# ARE_moduls.net
KiCad netlist of a schematic drawn in EAGLE
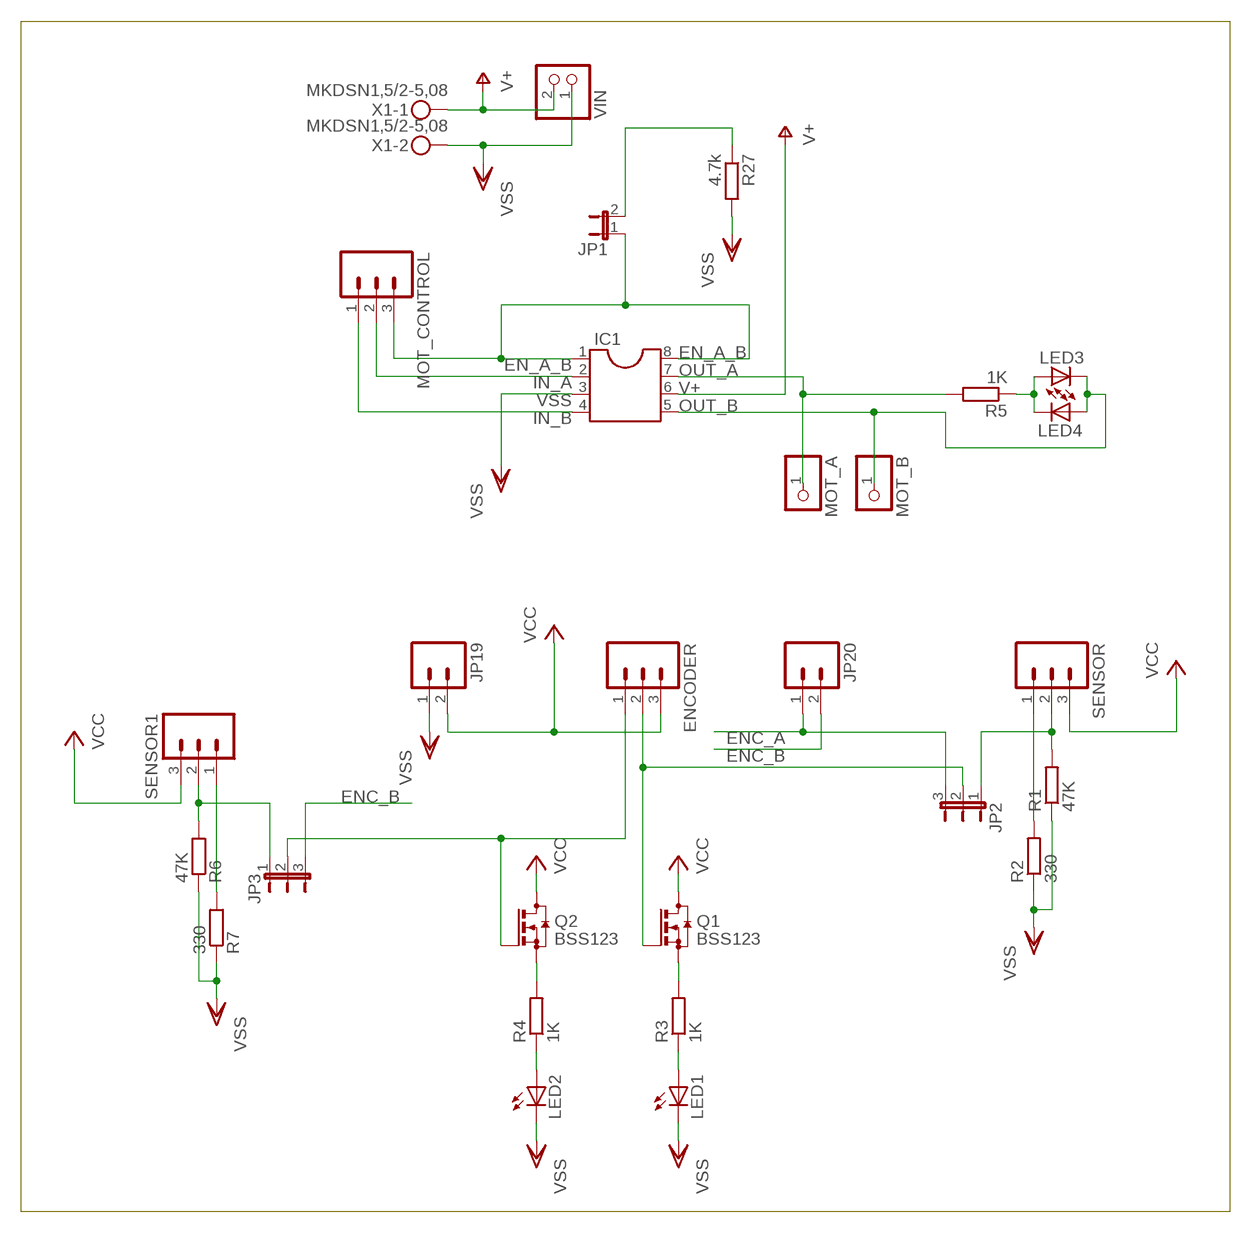
[diagram p0: schematic, sheet 1]
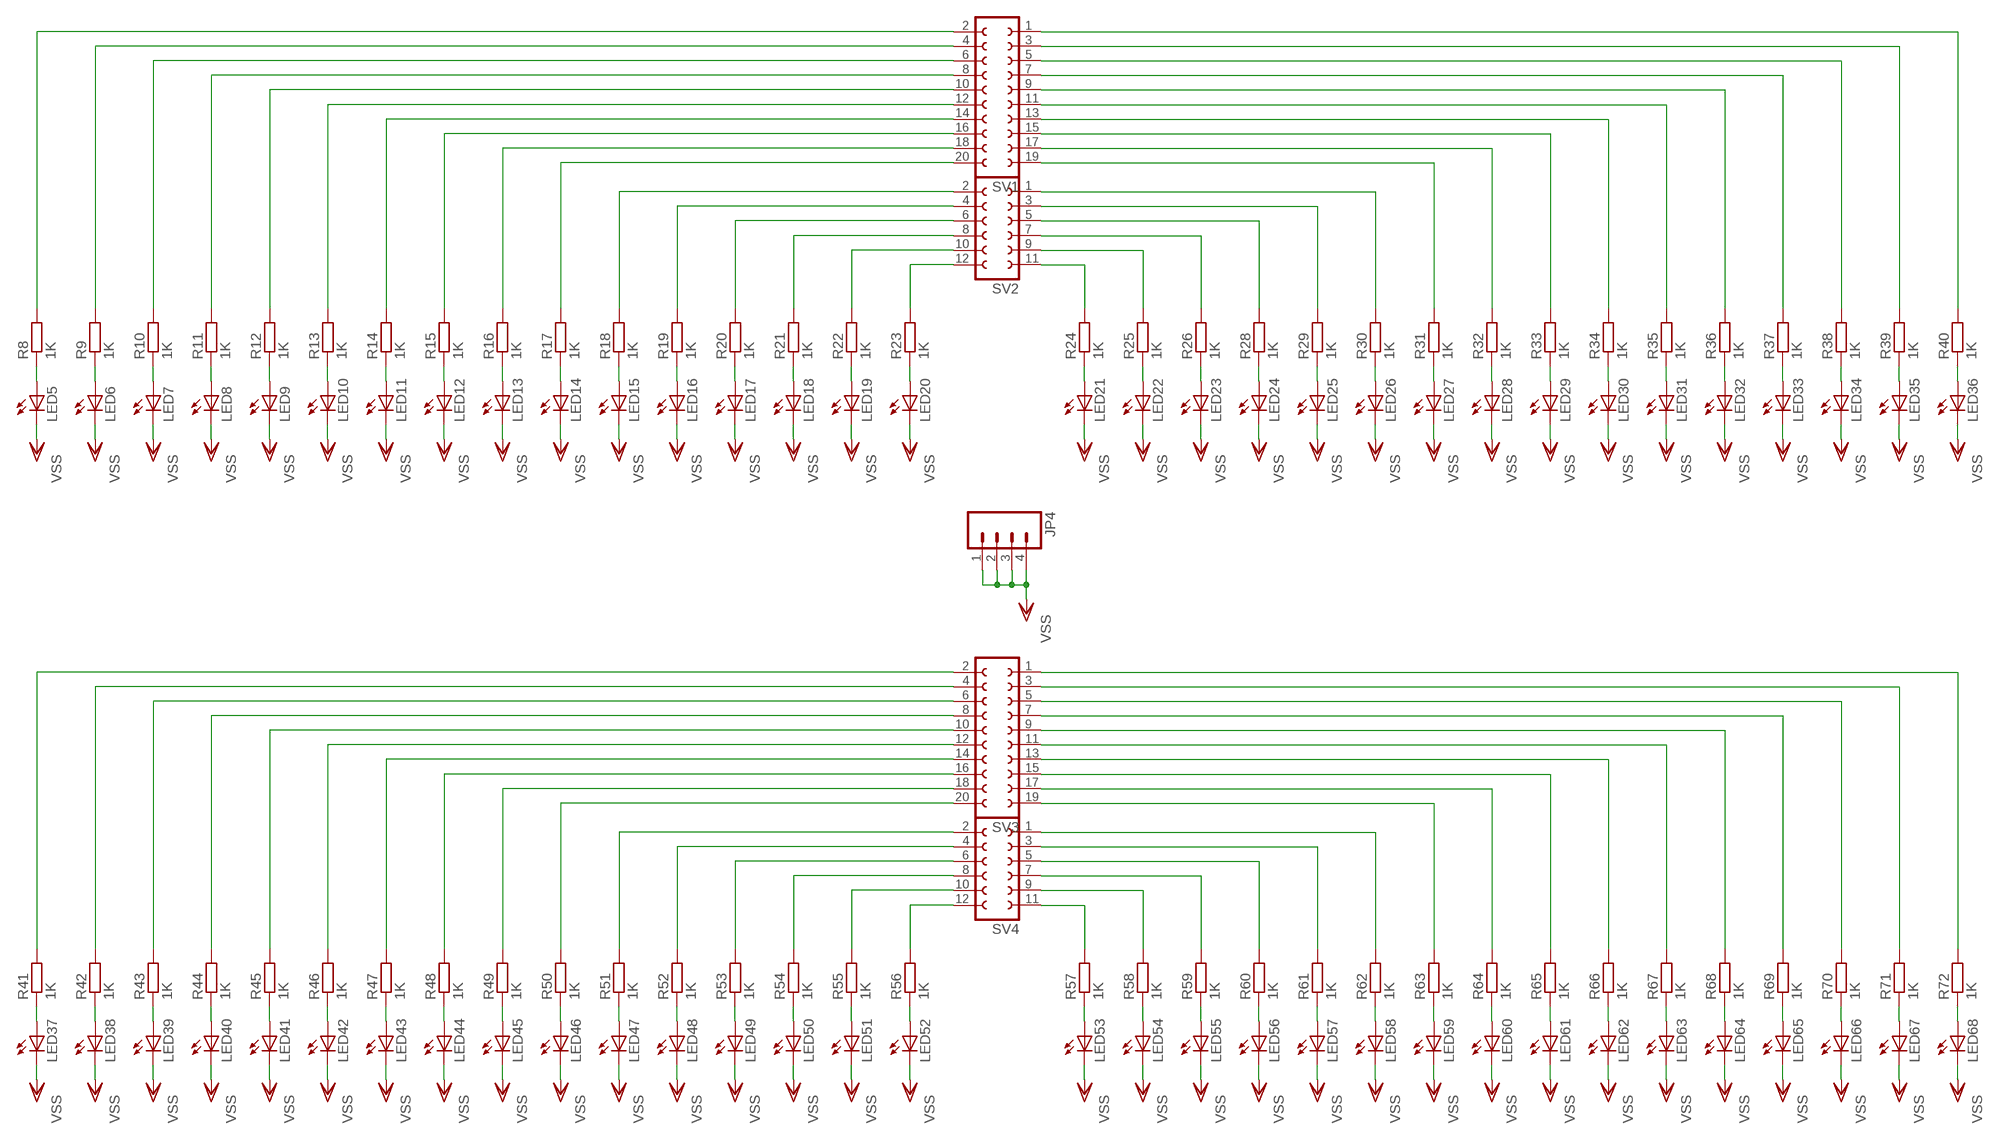
[diagram p1: schematic, sheet 2]
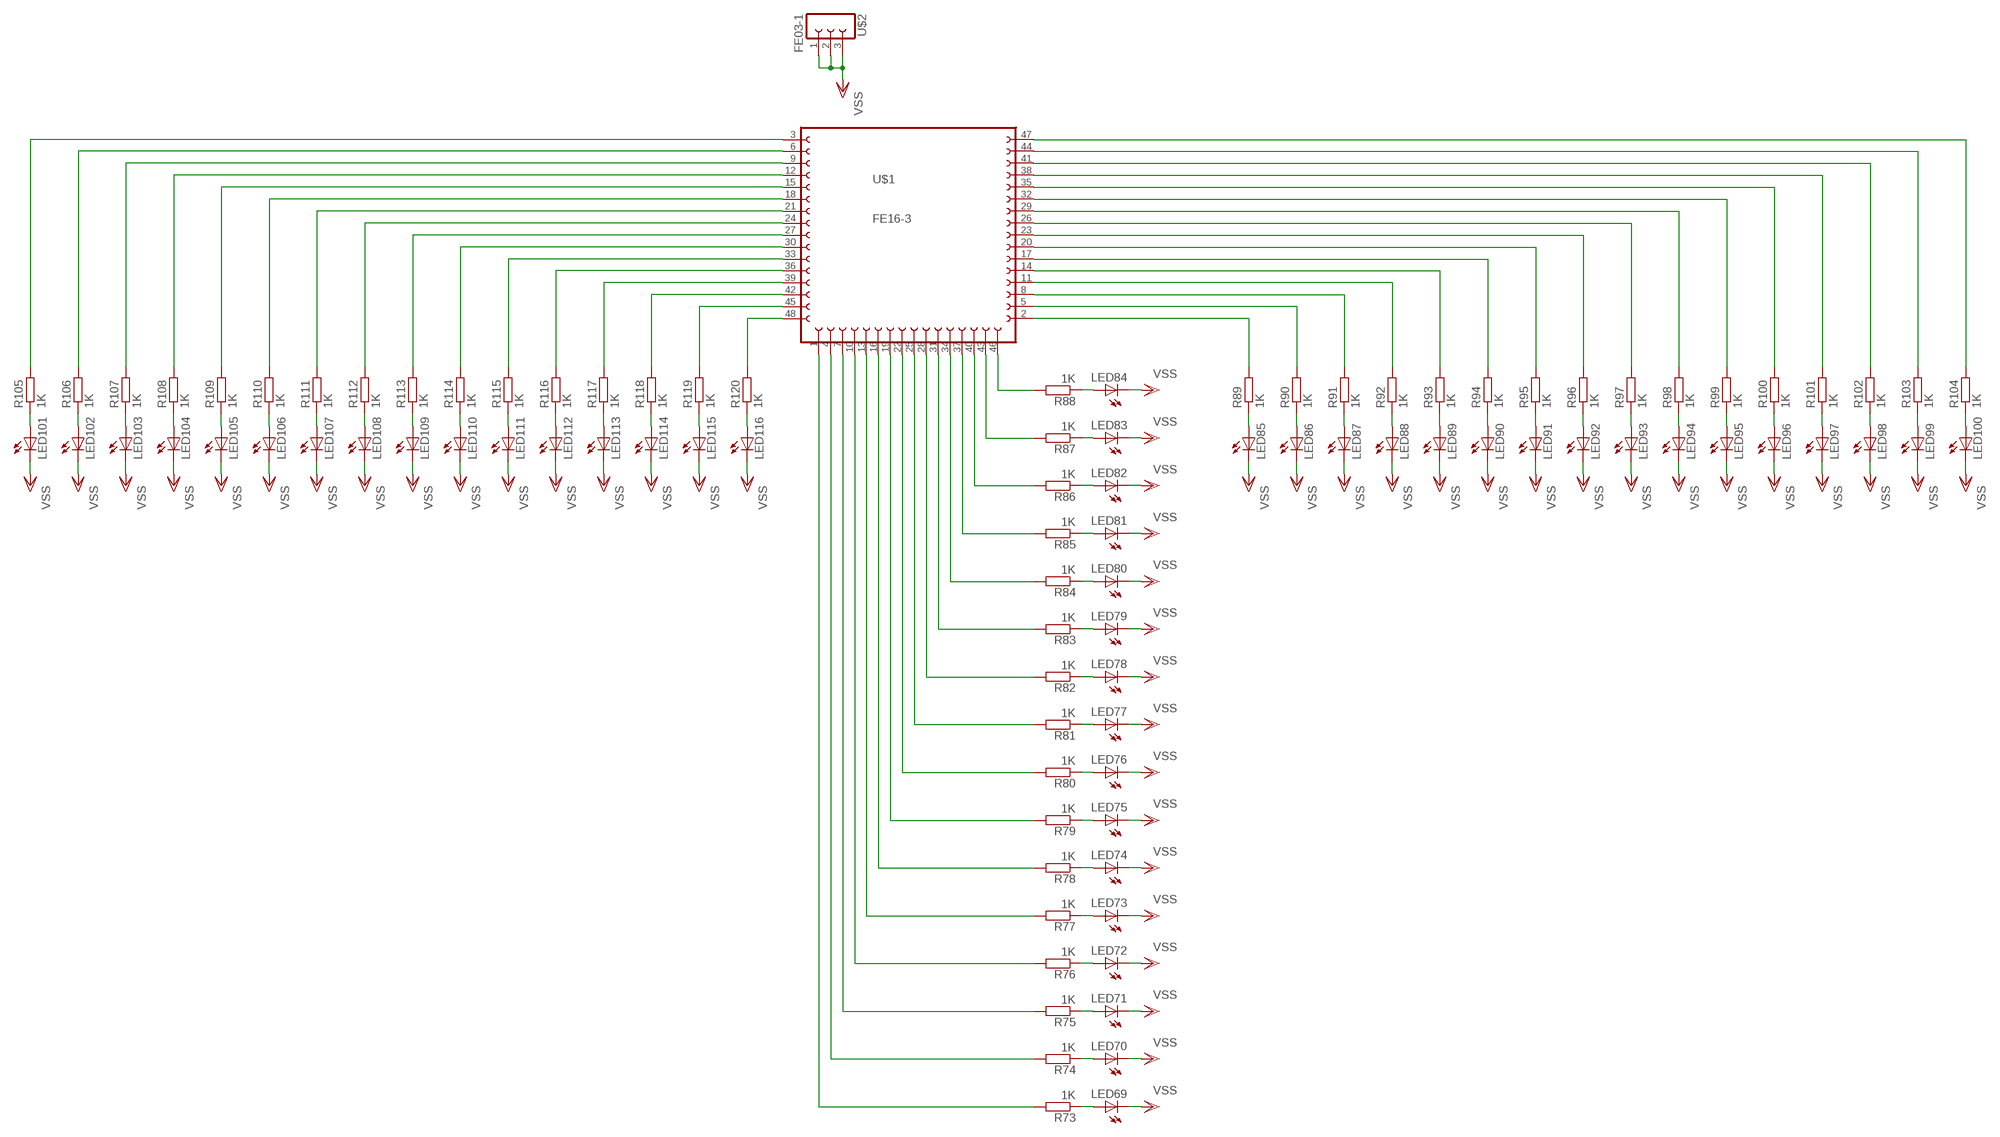
[diagram p2: schematic, sheet 3]
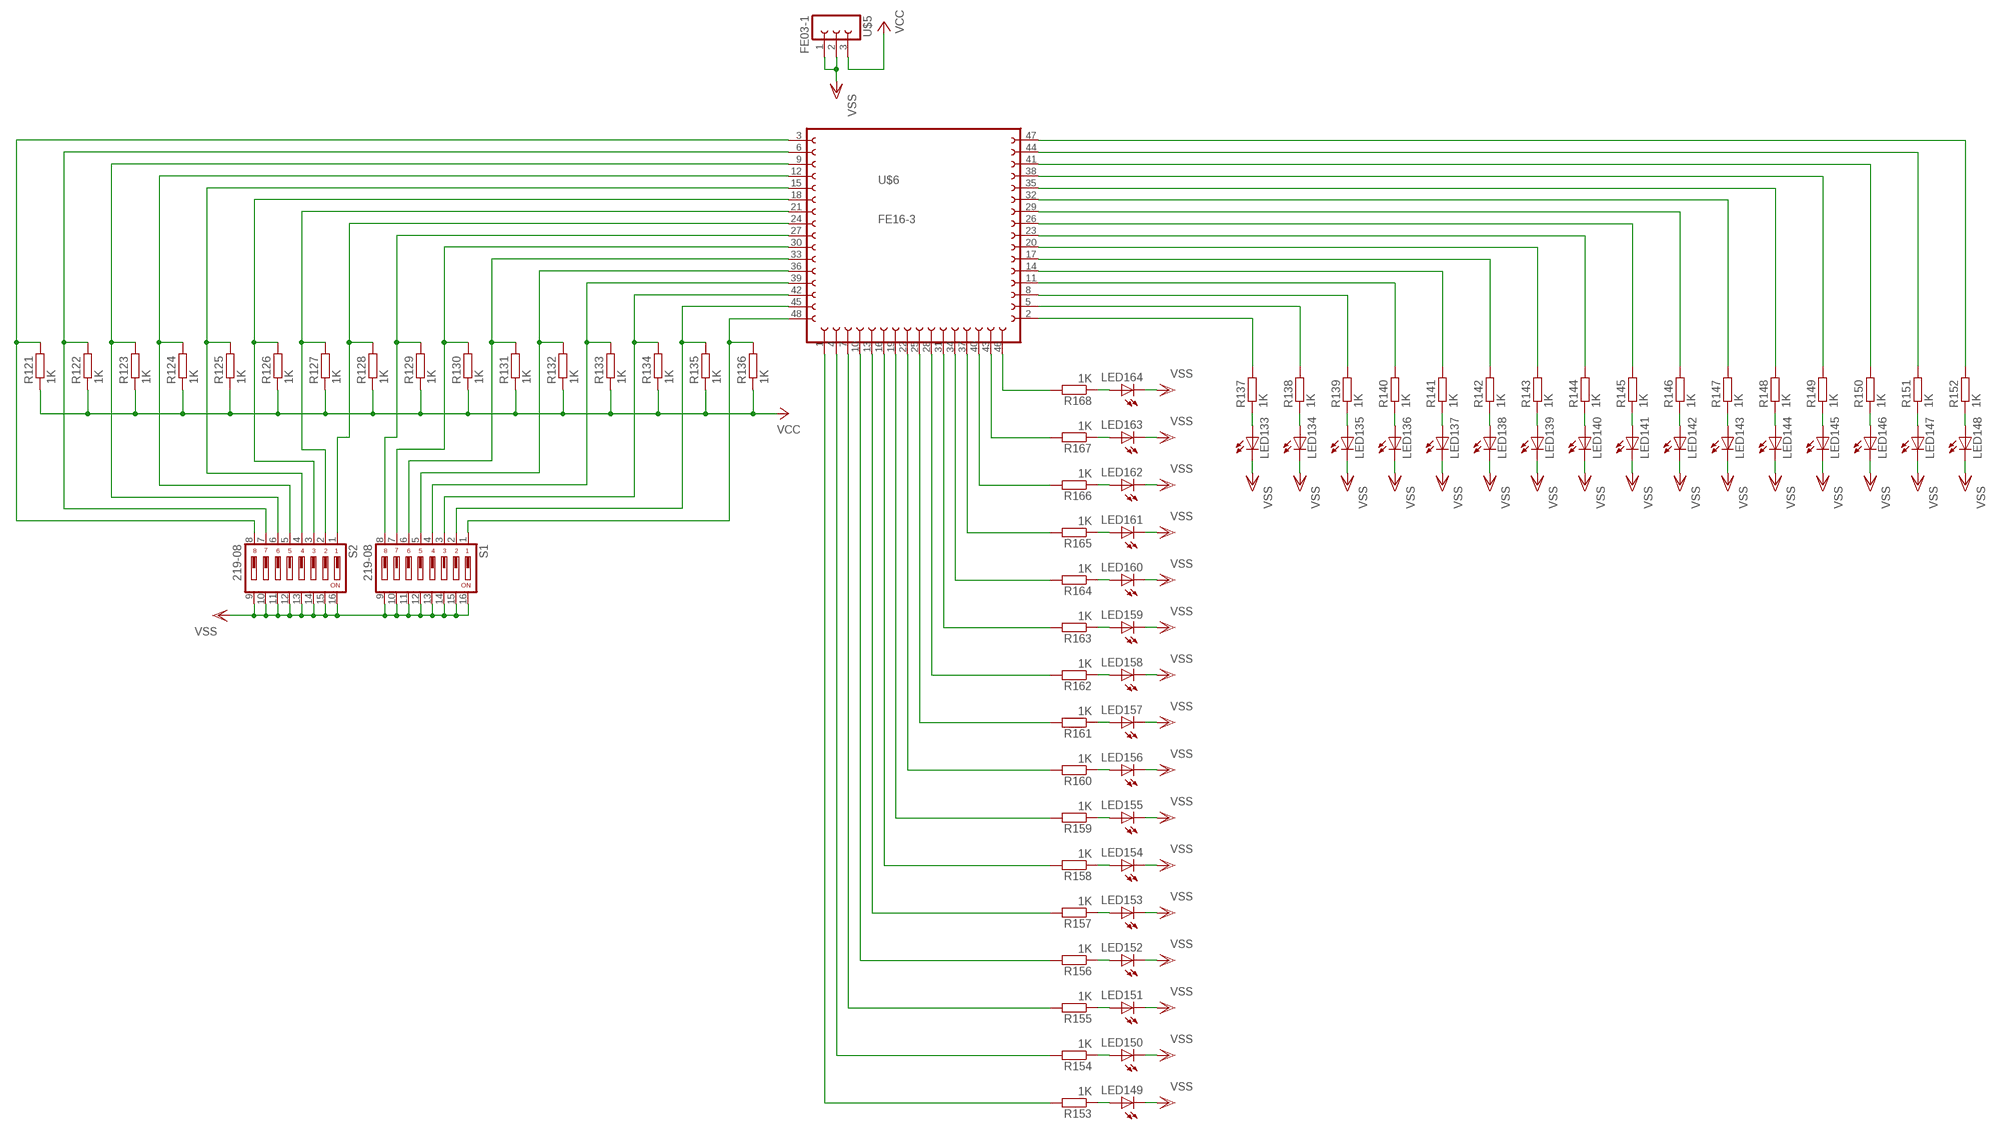
[diagram p3: schematic, sheet 4]
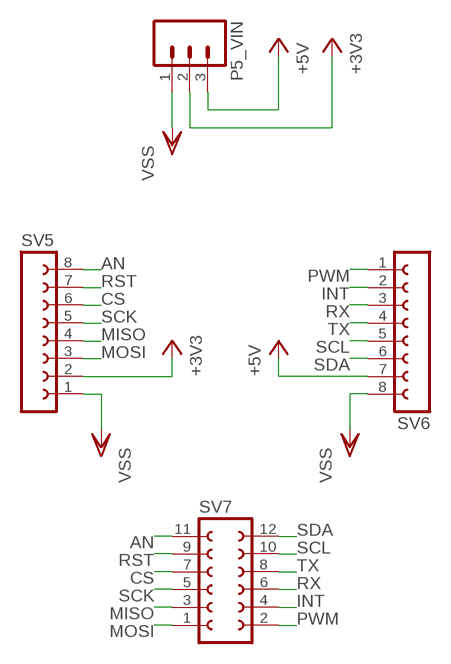
[diagram p4: schematic, sheet 5]
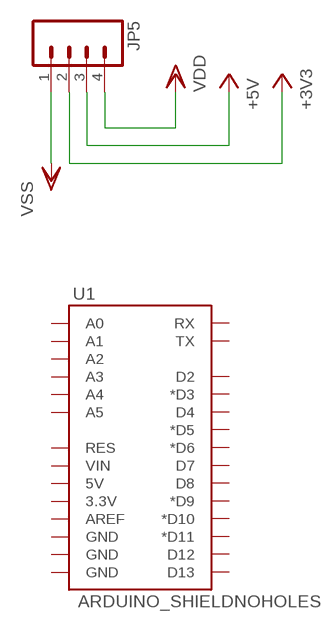
[diagram p5: schematic, sheet 6]

(export (version "E")
  (design (tool "Eeschema 10.0.6"))
  (components
    (comp (ref "LED133")
      (value "LEDCHIPLED_0805")
      (footprint "eagle-import:CHIPLED_0805")
      (libsource (lib "eagle-import") (part "LEDCHIPLED_0805"))
    )
    (comp (ref "LED134")
      (value "LEDCHIPLED_0805")
      (footprint "eagle-import:CHIPLED_0805")
      (libsource (lib "eagle-import") (part "LEDCHIPLED_0805"))
    )
    (comp (ref "LED135")
      (value "LEDCHIPLED_0805")
      (footprint "eagle-import:CHIPLED_0805")
      (libsource (lib "eagle-import") (part "LEDCHIPLED_0805"))
    )
    (comp (ref "LED136")
      (value "LEDCHIPLED_0805")
      (footprint "eagle-import:CHIPLED_0805")
      (libsource (lib "eagle-import") (part "LEDCHIPLED_0805"))
    )
    (comp (ref "LED137")
      (value "LEDCHIPLED_0805")
      (footprint "eagle-import:CHIPLED_0805")
      (libsource (lib "eagle-import") (part "LEDCHIPLED_0805"))
    )
    (comp (ref "LED138")
      (value "LEDCHIPLED_0805")
      (footprint "eagle-import:CHIPLED_0805")
      (libsource (lib "eagle-import") (part "LEDCHIPLED_0805"))
    )
    (comp (ref "LED139")
      (value "LEDCHIPLED_0805")
      (footprint "eagle-import:CHIPLED_0805")
      (libsource (lib "eagle-import") (part "LEDCHIPLED_0805"))
    )
    (comp (ref "LED140")
      (value "LEDCHIPLED_0805")
      (footprint "eagle-import:CHIPLED_0805")
      (libsource (lib "eagle-import") (part "LEDCHIPLED_0805"))
    )
    (comp (ref "LED141")
      (value "LEDCHIPLED_0805")
      (footprint "eagle-import:CHIPLED_0805")
      (libsource (lib "eagle-import") (part "LEDCHIPLED_0805"))
    )
    (comp (ref "LED142")
      (value "LEDCHIPLED_0805")
      (footprint "eagle-import:CHIPLED_0805")
      (libsource (lib "eagle-import") (part "LEDCHIPLED_0805"))
    )
    (comp (ref "LED143")
      (value "LEDCHIPLED_0805")
      (footprint "eagle-import:CHIPLED_0805")
      (libsource (lib "eagle-import") (part "LEDCHIPLED_0805"))
    )
    (comp (ref "LED144")
      (value "LEDCHIPLED_0805")
      (footprint "eagle-import:CHIPLED_0805")
      (libsource (lib "eagle-import") (part "LEDCHIPLED_0805"))
    )
    (comp (ref "LED145")
      (value "LEDCHIPLED_0805")
      (footprint "eagle-import:CHIPLED_0805")
      (libsource (lib "eagle-import") (part "LEDCHIPLED_0805"))
    )
    (comp (ref "LED146")
      (value "LEDCHIPLED_0805")
      (footprint "eagle-import:CHIPLED_0805")
      (libsource (lib "eagle-import") (part "LEDCHIPLED_0805"))
    )
    (comp (ref "LED147")
      (value "LEDCHIPLED_0805")
      (footprint "eagle-import:CHIPLED_0805")
      (libsource (lib "eagle-import") (part "LEDCHIPLED_0805"))
    )
    (comp (ref "LED148")
      (value "LEDCHIPLED_0805")
      (footprint "eagle-import:CHIPLED_0805")
      (libsource (lib "eagle-import") (part "LEDCHIPLED_0805"))
    )
    (comp (ref "LED149")
      (value "LEDCHIPLED_0805")
      (footprint "eagle-import:CHIPLED_0805")
      (libsource (lib "eagle-import") (part "LEDCHIPLED_0805"))
    )
    (comp (ref "LED150")
      (value "LEDCHIPLED_0805")
      (footprint "eagle-import:CHIPLED_0805")
      (libsource (lib "eagle-import") (part "LEDCHIPLED_0805"))
    )
    (comp (ref "LED151")
      (value "LEDCHIPLED_0805")
      (footprint "eagle-import:CHIPLED_0805")
      (libsource (lib "eagle-import") (part "LEDCHIPLED_0805"))
    )
    (comp (ref "LED152")
      (value "LEDCHIPLED_0805")
      (footprint "eagle-import:CHIPLED_0805")
      (libsource (lib "eagle-import") (part "LEDCHIPLED_0805"))
    )
    (comp (ref "LED153")
      (value "LEDCHIPLED_0805")
      (footprint "eagle-import:CHIPLED_0805")
      (libsource (lib "eagle-import") (part "LEDCHIPLED_0805"))
    )
    (comp (ref "LED154")
      (value "LEDCHIPLED_0805")
      (footprint "eagle-import:CHIPLED_0805")
      (libsource (lib "eagle-import") (part "LEDCHIPLED_0805"))
    )
    (comp (ref "LED155")
      (value "LEDCHIPLED_0805")
      (footprint "eagle-import:CHIPLED_0805")
      (libsource (lib "eagle-import") (part "LEDCHIPLED_0805"))
    )
    (comp (ref "LED156")
      (value "LEDCHIPLED_0805")
      (footprint "eagle-import:CHIPLED_0805")
      (libsource (lib "eagle-import") (part "LEDCHIPLED_0805"))
    )
    (comp (ref "LED157")
      (value "LEDCHIPLED_0805")
      (footprint "eagle-import:CHIPLED_0805")
      (libsource (lib "eagle-import") (part "LEDCHIPLED_0805"))
    )
    (comp (ref "LED158")
      (value "LEDCHIPLED_0805")
      (footprint "eagle-import:CHIPLED_0805")
      (libsource (lib "eagle-import") (part "LEDCHIPLED_0805"))
    )
    (comp (ref "LED159")
      (value "LEDCHIPLED_0805")
      (footprint "eagle-import:CHIPLED_0805")
      (libsource (lib "eagle-import") (part "LEDCHIPLED_0805"))
    )
    (comp (ref "LED160")
      (value "LEDCHIPLED_0805")
      (footprint "eagle-import:CHIPLED_0805")
      (libsource (lib "eagle-import") (part "LEDCHIPLED_0805"))
    )
    (comp (ref "LED161")
      (value "LEDCHIPLED_0805")
      (footprint "eagle-import:CHIPLED_0805")
      (libsource (lib "eagle-import") (part "LEDCHIPLED_0805"))
    )
    (comp (ref "LED162")
      (value "LEDCHIPLED_0805")
      (footprint "eagle-import:CHIPLED_0805")
      (libsource (lib "eagle-import") (part "LEDCHIPLED_0805"))
    )
    (comp (ref "LED163")
      (value "LEDCHIPLED_0805")
      (footprint "eagle-import:CHIPLED_0805")
      (libsource (lib "eagle-import") (part "LEDCHIPLED_0805"))
    )
    (comp (ref "LED164")
      (value "LEDCHIPLED_0805")
      (footprint "eagle-import:CHIPLED_0805")
      (libsource (lib "eagle-import") (part "LEDCHIPLED_0805"))
    )
    (comp (ref "R121")
      (value "1K")
      (footprint "eagle-import:M0805")
      (libsource (lib "eagle-import") (part "R-EU_M0805"))
    )
    (comp (ref "R122")
      (value "1K")
      (footprint "eagle-import:M0805")
      (libsource (lib "eagle-import") (part "R-EU_M0805"))
    )
    (comp (ref "R123")
      (value "1K")
      (footprint "eagle-import:M0805")
      (libsource (lib "eagle-import") (part "R-EU_M0805"))
    )
    (comp (ref "R124")
      (value "1K")
      (footprint "eagle-import:M0805")
      (libsource (lib "eagle-import") (part "R-EU_M0805"))
    )
    (comp (ref "R125")
      (value "1K")
      (footprint "eagle-import:M0805")
      (libsource (lib "eagle-import") (part "R-EU_M0805"))
    )
    (comp (ref "R126")
      (value "1K")
      (footprint "eagle-import:M0805")
      (libsource (lib "eagle-import") (part "R-EU_M0805"))
    )
    (comp (ref "R127")
      (value "1K")
      (footprint "eagle-import:M0805")
      (libsource (lib "eagle-import") (part "R-EU_M0805"))
    )
    (comp (ref "R128")
      (value "1K")
      (footprint "eagle-import:M0805")
      (libsource (lib "eagle-import") (part "R-EU_M0805"))
    )
    (comp (ref "R129")
      (value "1K")
      (footprint "eagle-import:M0805")
      (libsource (lib "eagle-import") (part "R-EU_M0805"))
    )
    (comp (ref "R130")
      (value "1K")
      (footprint "eagle-import:M0805")
      (libsource (lib "eagle-import") (part "R-EU_M0805"))
    )
    (comp (ref "R131")
      (value "1K")
      (footprint "eagle-import:M0805")
      (libsource (lib "eagle-import") (part "R-EU_M0805"))
    )
    (comp (ref "R132")
      (value "1K")
      (footprint "eagle-import:M0805")
      (libsource (lib "eagle-import") (part "R-EU_M0805"))
    )
    (comp (ref "R133")
      (value "1K")
      (footprint "eagle-import:M0805")
      (libsource (lib "eagle-import") (part "R-EU_M0805"))
    )
    (comp (ref "R134")
      (value "1K")
      (footprint "eagle-import:M0805")
      (libsource (lib "eagle-import") (part "R-EU_M0805"))
    )
    (comp (ref "R135")
      (value "1K")
      (footprint "eagle-import:M0805")
      (libsource (lib "eagle-import") (part "R-EU_M0805"))
    )
    (comp (ref "R136")
      (value "1K")
      (footprint "eagle-import:M0805")
      (libsource (lib "eagle-import") (part "R-EU_M0805"))
    )
    (comp (ref "R137")
      (value "1K")
      (footprint "eagle-import:M0805")
      (libsource (lib "eagle-import") (part "R-EU_M0805"))
    )
    (comp (ref "R138")
      (value "1K")
      (footprint "eagle-import:M0805")
      (libsource (lib "eagle-import") (part "R-EU_M0805"))
    )
    (comp (ref "R139")
      (value "1K")
      (footprint "eagle-import:M0805")
      (libsource (lib "eagle-import") (part "R-EU_M0805"))
    )
    (comp (ref "R140")
      (value "1K")
      (footprint "eagle-import:M0805")
      (libsource (lib "eagle-import") (part "R-EU_M0805"))
    )
    (comp (ref "R141")
      (value "1K")
      (footprint "eagle-import:M0805")
      (libsource (lib "eagle-import") (part "R-EU_M0805"))
    )
    (comp (ref "R142")
      (value "1K")
      (footprint "eagle-import:M0805")
      (libsource (lib "eagle-import") (part "R-EU_M0805"))
    )
    (comp (ref "R143")
      (value "1K")
      (footprint "eagle-import:M0805")
      (libsource (lib "eagle-import") (part "R-EU_M0805"))
    )
    (comp (ref "R144")
      (value "1K")
      (footprint "eagle-import:M0805")
      (libsource (lib "eagle-import") (part "R-EU_M0805"))
    )
    (comp (ref "R145")
      (value "1K")
      (footprint "eagle-import:M0805")
      (libsource (lib "eagle-import") (part "R-EU_M0805"))
    )
    (comp (ref "R146")
      (value "1K")
      (footprint "eagle-import:M0805")
      (libsource (lib "eagle-import") (part "R-EU_M0805"))
    )
    (comp (ref "R147")
      (value "1K")
      (footprint "eagle-import:M0805")
      (libsource (lib "eagle-import") (part "R-EU_M0805"))
    )
    (comp (ref "R148")
      (value "1K")
      (footprint "eagle-import:M0805")
      (libsource (lib "eagle-import") (part "R-EU_M0805"))
    )
    (comp (ref "R149")
      (value "1K")
      (footprint "eagle-import:M0805")
      (libsource (lib "eagle-import") (part "R-EU_M0805"))
    )
    (comp (ref "R150")
      (value "1K")
      (footprint "eagle-import:M0805")
      (libsource (lib "eagle-import") (part "R-EU_M0805"))
    )
    (comp (ref "R151")
      (value "1K")
      (footprint "eagle-import:M0805")
      (libsource (lib "eagle-import") (part "R-EU_M0805"))
    )
    (comp (ref "R152")
      (value "1K")
      (footprint "eagle-import:M0805")
      (libsource (lib "eagle-import") (part "R-EU_M0805"))
    )
    (comp (ref "R153")
      (value "1K")
      (footprint "eagle-import:M0805")
      (libsource (lib "eagle-import") (part "R-EU_M0805"))
    )
    (comp (ref "R154")
      (value "1K")
      (footprint "eagle-import:M0805")
      (libsource (lib "eagle-import") (part "R-EU_M0805"))
    )
    (comp (ref "R155")
      (value "1K")
      (footprint "eagle-import:M0805")
      (libsource (lib "eagle-import") (part "R-EU_M0805"))
    )
    (comp (ref "R156")
      (value "1K")
      (footprint "eagle-import:M0805")
      (libsource (lib "eagle-import") (part "R-EU_M0805"))
    )
    (comp (ref "R157")
      (value "1K")
      (footprint "eagle-import:M0805")
      (libsource (lib "eagle-import") (part "R-EU_M0805"))
    )
    (comp (ref "R158")
      (value "1K")
      (footprint "eagle-import:M0805")
      (libsource (lib "eagle-import") (part "R-EU_M0805"))
    )
    (comp (ref "R159")
      (value "1K")
      (footprint "eagle-import:M0805")
      (libsource (lib "eagle-import") (part "R-EU_M0805"))
    )
    (comp (ref "R160")
      (value "1K")
      (footprint "eagle-import:M0805")
      (libsource (lib "eagle-import") (part "R-EU_M0805"))
    )
    (comp (ref "R161")
      (value "1K")
      (footprint "eagle-import:M0805")
      (libsource (lib "eagle-import") (part "R-EU_M0805"))
    )
    (comp (ref "R162")
      (value "1K")
      (footprint "eagle-import:M0805")
      (libsource (lib "eagle-import") (part "R-EU_M0805"))
    )
    (comp (ref "R163")
      (value "1K")
      (footprint "eagle-import:M0805")
      (libsource (lib "eagle-import") (part "R-EU_M0805"))
    )
    (comp (ref "R164")
      (value "1K")
      (footprint "eagle-import:M0805")
      (libsource (lib "eagle-import") (part "R-EU_M0805"))
    )
    (comp (ref "R165")
      (value "1K")
      (footprint "eagle-import:M0805")
      (libsource (lib "eagle-import") (part "R-EU_M0805"))
    )
    (comp (ref "R166")
      (value "1K")
      (footprint "eagle-import:M0805")
      (libsource (lib "eagle-import") (part "R-EU_M0805"))
    )
    (comp (ref "R167")
      (value "1K")
      (footprint "eagle-import:M0805")
      (libsource (lib "eagle-import") (part "R-EU_M0805"))
    )
    (comp (ref "R168")
      (value "1K")
      (footprint "eagle-import:M0805")
      (libsource (lib "eagle-import") (part "R-EU_M0805"))
    )
    (comp (ref "S1")
      (value "219-08")
      (footprint "eagle-import:CTS-219-08")
      (fields (field (name "OC_FARNELL") "unknown") (field (name "OC_NEWARK") "unknown"))
      (libsource (lib "eagle-import") (part "219-08"))
    )
    (comp (ref "S2")
      (value "219-08")
      (footprint "eagle-import:CTS-219-08")
      (fields (field (name "OC_FARNELL") "unknown") (field (name "OC_NEWARK") "unknown"))
      (libsource (lib "eagle-import") (part "219-08"))
    )
    (comp (ref "U$5")
      (value "FE03-1")
      (footprint "eagle-import:FE03-1")
      (libsource (lib "eagle-import") (part "FE03-1"))
    )
    (comp (ref "U$6")
      (value "FE16-3")
      (footprint "eagle-import:FE16-3")
      (libsource (lib "eagle-import") (part "FE16-3"))
    )
    (comp (ref "P5_VIN")
      (value "M03PTH")
      (footprint "eagle-import:1X03")
      (libsource (lib "eagle-import") (part "M03PTH"))
    )
    (comp (ref "SV5")
      (value "FE08-1")
      (footprint "eagle-import:FE08")
      (libsource (lib "eagle-import") (part "FE08-1"))
    )
    (comp (ref "SV6")
      (value "FE08-1")
      (footprint "eagle-import:FE08")
      (libsource (lib "eagle-import") (part "FE08-1"))
    )
    (comp (ref "SV7")
      (value "FE06-2")
      (footprint "eagle-import:FE06-2")
      (libsource (lib "eagle-import") (part "FE06-2"))
    )
    (comp (ref "ENCODER")
      (value "M03PTH")
      (footprint "eagle-import:1X03")
      (libsource (lib "eagle-import") (part "M03PTH"))
    )
    (comp (ref "IC1")
      (value "DIL8S")
      (footprint "eagle-import:SOCKET-08")
      (libsource (lib "eagle-import") (part "DIL8S"))
    )
    (comp (ref "JP1")
      (value "JP1E")
      (footprint "eagle-import:JP1")
      (libsource (lib "eagle-import") (part "JP1E"))
    )
    (comp (ref "JP2")
      (value "JP2E")
      (footprint "eagle-import:JP2")
      (libsource (lib "eagle-import") (part "JP2E"))
    )
    (comp (ref "JP3")
      (value "JP2E")
      (footprint "eagle-import:JP2")
      (libsource (lib "eagle-import") (part "JP2E"))
    )
    (comp (ref "JP19")
      (value "M02PTH")
      (footprint "eagle-import:1X02")
      (libsource (lib "eagle-import") (part "M02PTH"))
    )
    (comp (ref "JP20")
      (value "M02PTH")
      (footprint "eagle-import:1X02")
      (libsource (lib "eagle-import") (part "M02PTH"))
    )
    (comp (ref "LED1")
      (value "LEDCHIPLED_0805")
      (footprint "eagle-import:CHIPLED_0805")
      (libsource (lib "eagle-import") (part "LEDCHIPLED_0805"))
    )
    (comp (ref "LED2")
      (value "LEDCHIPLED_0805")
      (footprint "eagle-import:CHIPLED_0805")
      (libsource (lib "eagle-import") (part "LEDCHIPLED_0805"))
    )
    (comp (ref "LED3")
      (value "LEDCHIPLED_0805")
      (footprint "eagle-import:CHIPLED_0805")
      (libsource (lib "eagle-import") (part "LEDCHIPLED_0805"))
    )
    (comp (ref "LED4")
      (value "LEDCHIPLED_0805")
      (footprint "eagle-import:CHIPLED_0805")
      (libsource (lib "eagle-import") (part "LEDCHIPLED_0805"))
    )
    (comp (ref "MOT_A")
      (value "PINHD-1X1")
      (footprint "eagle-import:1X01")
      (libsource (lib "eagle-import") (part "PINHD-1X1"))
    )
    (comp (ref "MOT_B")
      (value "PINHD-1X1")
      (footprint "eagle-import:1X01")
      (libsource (lib "eagle-import") (part "PINHD-1X1"))
    )
    (comp (ref "MOT_CONTROL")
      (value "M03PTH")
      (footprint "eagle-import:1X03")
      (libsource (lib "eagle-import") (part "M03PTH"))
    )
    (comp (ref "Q1")
      (value "BSS123")
      (footprint "eagle-import:SOT23")
      (libsource (lib "eagle-import") (part "BSS123"))
    )
    (comp (ref "Q2")
      (value "BSS123")
      (footprint "eagle-import:SOT23")
      (libsource (lib "eagle-import") (part "BSS123"))
    )
    (comp (ref "R1")
      (value "47K")
      (footprint "eagle-import:M0805")
      (libsource (lib "eagle-import") (part "R-EU_M0805"))
    )
    (comp (ref "R2")
      (value "330")
      (footprint "eagle-import:M0805")
      (libsource (lib "eagle-import") (part "R-EU_M0805"))
    )
    (comp (ref "R3")
      (value "1K")
      (footprint "eagle-import:M0805")
      (libsource (lib "eagle-import") (part "R-EU_M0805"))
    )
    (comp (ref "R4")
      (value "1K")
      (footprint "eagle-import:M0805")
      (libsource (lib "eagle-import") (part "R-EU_M0805"))
    )
    (comp (ref "R5")
      (value "1K")
      (footprint "eagle-import:M0805")
      (libsource (lib "eagle-import") (part "R-EU_M0805"))
    )
    (comp (ref "R6")
      (value "47K")
      (footprint "eagle-import:M0805")
      (libsource (lib "eagle-import") (part "R-EU_M0805"))
    )
    (comp (ref "R7")
      (value "330")
      (footprint "eagle-import:M0805")
      (libsource (lib "eagle-import") (part "R-EU_M0805"))
    )
    (comp (ref "R27")
      (value "4.7k")
      (footprint "eagle-import:R0805")
      (libsource (lib "eagle-import") (part "R-EU_R0805"))
    )
    (comp (ref "SENSOR")
      (value "M03PTH")
      (footprint "eagle-import:1X03")
      (libsource (lib "eagle-import") (part "M03PTH"))
    )
    (comp (ref "SENSOR1")
      (value "M03PTH")
      (footprint "eagle-import:1X03")
      (libsource (lib "eagle-import") (part "M03PTH"))
    )
    (comp (ref "VIN")
      (value "PINHD-1X2")
      (footprint "eagle-import:1X02")
      (libsource (lib "eagle-import") (part "PINHD-1X2"))
    )
    (comp (ref "X1")
      (value "MKDSN1,5/2-5,08")
      (footprint "eagle-import:MKDSN1,5_2-5,08")
      (libsource (lib "eagle-import") (part "MKDSN1,5/2-5,08"))
    )
    (comp (ref "LED69")
      (value "LEDCHIPLED_0805")
      (footprint "eagle-import:CHIPLED_0805")
      (libsource (lib "eagle-import") (part "LEDCHIPLED_0805"))
    )
    (comp (ref "LED70")
      (value "LEDCHIPLED_0805")
      (footprint "eagle-import:CHIPLED_0805")
      (libsource (lib "eagle-import") (part "LEDCHIPLED_0805"))
    )
    (comp (ref "LED71")
      (value "LEDCHIPLED_0805")
      (footprint "eagle-import:CHIPLED_0805")
      (libsource (lib "eagle-import") (part "LEDCHIPLED_0805"))
    )
    (comp (ref "LED72")
      (value "LEDCHIPLED_0805")
      (footprint "eagle-import:CHIPLED_0805")
      (libsource (lib "eagle-import") (part "LEDCHIPLED_0805"))
    )
    (comp (ref "LED73")
      (value "LEDCHIPLED_0805")
      (footprint "eagle-import:CHIPLED_0805")
      (libsource (lib "eagle-import") (part "LEDCHIPLED_0805"))
    )
    (comp (ref "LED74")
      (value "LEDCHIPLED_0805")
      (footprint "eagle-import:CHIPLED_0805")
      (libsource (lib "eagle-import") (part "LEDCHIPLED_0805"))
    )
    (comp (ref "LED75")
      (value "LEDCHIPLED_0805")
      (footprint "eagle-import:CHIPLED_0805")
      (libsource (lib "eagle-import") (part "LEDCHIPLED_0805"))
    )
    (comp (ref "LED76")
      (value "LEDCHIPLED_0805")
      (footprint "eagle-import:CHIPLED_0805")
      (libsource (lib "eagle-import") (part "LEDCHIPLED_0805"))
    )
    (comp (ref "LED77")
      (value "LEDCHIPLED_0805")
      (footprint "eagle-import:CHIPLED_0805")
      (libsource (lib "eagle-import") (part "LEDCHIPLED_0805"))
    )
    (comp (ref "LED78")
      (value "LEDCHIPLED_0805")
      (footprint "eagle-import:CHIPLED_0805")
      (libsource (lib "eagle-import") (part "LEDCHIPLED_0805"))
    )
    (comp (ref "LED79")
      (value "LEDCHIPLED_0805")
      (footprint "eagle-import:CHIPLED_0805")
      (libsource (lib "eagle-import") (part "LEDCHIPLED_0805"))
    )
    (comp (ref "LED80")
      (value "LEDCHIPLED_0805")
      (footprint "eagle-import:CHIPLED_0805")
      (libsource (lib "eagle-import") (part "LEDCHIPLED_0805"))
    )
    (comp (ref "LED81")
      (value "LEDCHIPLED_0805")
      (footprint "eagle-import:CHIPLED_0805")
      (libsource (lib "eagle-import") (part "LEDCHIPLED_0805"))
    )
    (comp (ref "LED82")
      (value "LEDCHIPLED_0805")
      (footprint "eagle-import:CHIPLED_0805")
      (libsource (lib "eagle-import") (part "LEDCHIPLED_0805"))
    )
    (comp (ref "LED83")
      (value "LEDCHIPLED_0805")
      (footprint "eagle-import:CHIPLED_0805")
      (libsource (lib "eagle-import") (part "LEDCHIPLED_0805"))
    )
    (comp (ref "LED84")
      (value "LEDCHIPLED_0805")
      (footprint "eagle-import:CHIPLED_0805")
      (libsource (lib "eagle-import") (part "LEDCHIPLED_0805"))
    )
    (comp (ref "LED85")
      (value "LEDCHIPLED_0805")
      (footprint "eagle-import:CHIPLED_0805")
      (libsource (lib "eagle-import") (part "LEDCHIPLED_0805"))
    )
    (comp (ref "LED86")
      (value "LEDCHIPLED_0805")
      (footprint "eagle-import:CHIPLED_0805")
      (libsource (lib "eagle-import") (part "LEDCHIPLED_0805"))
    )
    (comp (ref "LED87")
      (value "LEDCHIPLED_0805")
      (footprint "eagle-import:CHIPLED_0805")
      (libsource (lib "eagle-import") (part "LEDCHIPLED_0805"))
    )
    (comp (ref "LED88")
      (value "LEDCHIPLED_0805")
      (footprint "eagle-import:CHIPLED_0805")
      (libsource (lib "eagle-import") (part "LEDCHIPLED_0805"))
    )
    (comp (ref "LED89")
      (value "LEDCHIPLED_0805")
      (footprint "eagle-import:CHIPLED_0805")
      (libsource (lib "eagle-import") (part "LEDCHIPLED_0805"))
    )
    (comp (ref "LED90")
      (value "LEDCHIPLED_0805")
      (footprint "eagle-import:CHIPLED_0805")
      (libsource (lib "eagle-import") (part "LEDCHIPLED_0805"))
    )
    (comp (ref "LED91")
      (value "LEDCHIPLED_0805")
      (footprint "eagle-import:CHIPLED_0805")
      (libsource (lib "eagle-import") (part "LEDCHIPLED_0805"))
    )
    (comp (ref "LED92")
      (value "LEDCHIPLED_0805")
      (footprint "eagle-import:CHIPLED_0805")
      (libsource (lib "eagle-import") (part "LEDCHIPLED_0805"))
    )
    (comp (ref "LED93")
      (value "LEDCHIPLED_0805")
      (footprint "eagle-import:CHIPLED_0805")
      (libsource (lib "eagle-import") (part "LEDCHIPLED_0805"))
    )
    (comp (ref "LED94")
      (value "LEDCHIPLED_0805")
      (footprint "eagle-import:CHIPLED_0805")
      (libsource (lib "eagle-import") (part "LEDCHIPLED_0805"))
    )
    (comp (ref "LED95")
      (value "LEDCHIPLED_0805")
      (footprint "eagle-import:CHIPLED_0805")
      (libsource (lib "eagle-import") (part "LEDCHIPLED_0805"))
    )
    (comp (ref "LED96")
      (value "LEDCHIPLED_0805")
      (footprint "eagle-import:CHIPLED_0805")
      (libsource (lib "eagle-import") (part "LEDCHIPLED_0805"))
    )
    (comp (ref "LED97")
      (value "LEDCHIPLED_0805")
      (footprint "eagle-import:CHIPLED_0805")
      (libsource (lib "eagle-import") (part "LEDCHIPLED_0805"))
    )
    (comp (ref "LED98")
      (value "LEDCHIPLED_0805")
      (footprint "eagle-import:CHIPLED_0805")
      (libsource (lib "eagle-import") (part "LEDCHIPLED_0805"))
    )
    (comp (ref "LED99")
      (value "LEDCHIPLED_0805")
      (footprint "eagle-import:CHIPLED_0805")
      (libsource (lib "eagle-import") (part "LEDCHIPLED_0805"))
    )
    (comp (ref "LED100")
      (value "LEDCHIPLED_0805")
      (footprint "eagle-import:CHIPLED_0805")
      (libsource (lib "eagle-import") (part "LEDCHIPLED_0805"))
    )
    (comp (ref "LED101")
      (value "LEDCHIPLED_0805")
      (footprint "eagle-import:CHIPLED_0805")
      (libsource (lib "eagle-import") (part "LEDCHIPLED_0805"))
    )
    (comp (ref "LED102")
      (value "LEDCHIPLED_0805")
      (footprint "eagle-import:CHIPLED_0805")
      (libsource (lib "eagle-import") (part "LEDCHIPLED_0805"))
    )
    (comp (ref "LED103")
      (value "LEDCHIPLED_0805")
      (footprint "eagle-import:CHIPLED_0805")
      (libsource (lib "eagle-import") (part "LEDCHIPLED_0805"))
    )
    (comp (ref "LED104")
      (value "LEDCHIPLED_0805")
      (footprint "eagle-import:CHIPLED_0805")
      (libsource (lib "eagle-import") (part "LEDCHIPLED_0805"))
    )
    (comp (ref "LED105")
      (value "LEDCHIPLED_0805")
      (footprint "eagle-import:CHIPLED_0805")
      (libsource (lib "eagle-import") (part "LEDCHIPLED_0805"))
    )
    (comp (ref "LED106")
      (value "LEDCHIPLED_0805")
      (footprint "eagle-import:CHIPLED_0805")
      (libsource (lib "eagle-import") (part "LEDCHIPLED_0805"))
    )
    (comp (ref "LED107")
      (value "LEDCHIPLED_0805")
      (footprint "eagle-import:CHIPLED_0805")
      (libsource (lib "eagle-import") (part "LEDCHIPLED_0805"))
    )
    (comp (ref "LED108")
      (value "LEDCHIPLED_0805")
      (footprint "eagle-import:CHIPLED_0805")
      (libsource (lib "eagle-import") (part "LEDCHIPLED_0805"))
    )
    (comp (ref "LED109")
      (value "LEDCHIPLED_0805")
      (footprint "eagle-import:CHIPLED_0805")
      (libsource (lib "eagle-import") (part "LEDCHIPLED_0805"))
    )
    (comp (ref "LED110")
      (value "LEDCHIPLED_0805")
      (footprint "eagle-import:CHIPLED_0805")
      (libsource (lib "eagle-import") (part "LEDCHIPLED_0805"))
    )
    (comp (ref "LED111")
      (value "LEDCHIPLED_0805")
      (footprint "eagle-import:CHIPLED_0805")
      (libsource (lib "eagle-import") (part "LEDCHIPLED_0805"))
    )
    (comp (ref "LED112")
      (value "LEDCHIPLED_0805")
      (footprint "eagle-import:CHIPLED_0805")
      (libsource (lib "eagle-import") (part "LEDCHIPLED_0805"))
    )
    (comp (ref "LED113")
      (value "LEDCHIPLED_0805")
      (footprint "eagle-import:CHIPLED_0805")
      (libsource (lib "eagle-import") (part "LEDCHIPLED_0805"))
    )
    (comp (ref "LED114")
      (value "LEDCHIPLED_0805")
      (footprint "eagle-import:CHIPLED_0805")
      (libsource (lib "eagle-import") (part "LEDCHIPLED_0805"))
    )
    (comp (ref "LED115")
      (value "LEDCHIPLED_0805")
      (footprint "eagle-import:CHIPLED_0805")
      (libsource (lib "eagle-import") (part "LEDCHIPLED_0805"))
    )
    (comp (ref "LED116")
      (value "LEDCHIPLED_0805")
      (footprint "eagle-import:CHIPLED_0805")
      (libsource (lib "eagle-import") (part "LEDCHIPLED_0805"))
    )
    (comp (ref "R73")
      (value "1K")
      (footprint "eagle-import:M0805")
      (libsource (lib "eagle-import") (part "R-EU_M0805"))
    )
    (comp (ref "R74")
      (value "1K")
      (footprint "eagle-import:M0805")
      (libsource (lib "eagle-import") (part "R-EU_M0805"))
    )
    (comp (ref "R75")
      (value "1K")
      (footprint "eagle-import:M0805")
      (libsource (lib "eagle-import") (part "R-EU_M0805"))
    )
    (comp (ref "R76")
      (value "1K")
      (footprint "eagle-import:M0805")
      (libsource (lib "eagle-import") (part "R-EU_M0805"))
    )
    (comp (ref "R77")
      (value "1K")
      (footprint "eagle-import:M0805")
      (libsource (lib "eagle-import") (part "R-EU_M0805"))
    )
    (comp (ref "R78")
      (value "1K")
      (footprint "eagle-import:M0805")
      (libsource (lib "eagle-import") (part "R-EU_M0805"))
    )
    (comp (ref "R79")
      (value "1K")
      (footprint "eagle-import:M0805")
      (libsource (lib "eagle-import") (part "R-EU_M0805"))
    )
    (comp (ref "R80")
      (value "1K")
      (footprint "eagle-import:M0805")
      (libsource (lib "eagle-import") (part "R-EU_M0805"))
    )
    (comp (ref "R81")
      (value "1K")
      (footprint "eagle-import:M0805")
      (libsource (lib "eagle-import") (part "R-EU_M0805"))
    )
    (comp (ref "R82")
      (value "1K")
      (footprint "eagle-import:M0805")
      (libsource (lib "eagle-import") (part "R-EU_M0805"))
    )
    (comp (ref "R83")
      (value "1K")
      (footprint "eagle-import:M0805")
      (libsource (lib "eagle-import") (part "R-EU_M0805"))
    )
    (comp (ref "R84")
      (value "1K")
      (footprint "eagle-import:M0805")
      (libsource (lib "eagle-import") (part "R-EU_M0805"))
    )
    (comp (ref "R85")
      (value "1K")
      (footprint "eagle-import:M0805")
      (libsource (lib "eagle-import") (part "R-EU_M0805"))
    )
    (comp (ref "R86")
      (value "1K")
      (footprint "eagle-import:M0805")
      (libsource (lib "eagle-import") (part "R-EU_M0805"))
    )
    (comp (ref "R87")
      (value "1K")
      (footprint "eagle-import:M0805")
      (libsource (lib "eagle-import") (part "R-EU_M0805"))
    )
    (comp (ref "R88")
      (value "1K")
      (footprint "eagle-import:M0805")
      (libsource (lib "eagle-import") (part "R-EU_M0805"))
    )
    (comp (ref "R89")
      (value "1K")
      (footprint "eagle-import:M0805")
      (libsource (lib "eagle-import") (part "R-EU_M0805"))
    )
    (comp (ref "R90")
      (value "1K")
      (footprint "eagle-import:M0805")
      (libsource (lib "eagle-import") (part "R-EU_M0805"))
    )
    (comp (ref "R91")
      (value "1K")
      (footprint "eagle-import:M0805")
      (libsource (lib "eagle-import") (part "R-EU_M0805"))
    )
    (comp (ref "R92")
      (value "1K")
      (footprint "eagle-import:M0805")
      (libsource (lib "eagle-import") (part "R-EU_M0805"))
    )
    (comp (ref "R93")
      (value "1K")
      (footprint "eagle-import:M0805")
      (libsource (lib "eagle-import") (part "R-EU_M0805"))
    )
    (comp (ref "R94")
      (value "1K")
      (footprint "eagle-import:M0805")
      (libsource (lib "eagle-import") (part "R-EU_M0805"))
    )
    (comp (ref "R95")
      (value "1K")
      (footprint "eagle-import:M0805")
      (libsource (lib "eagle-import") (part "R-EU_M0805"))
    )
    (comp (ref "R96")
      (value "1K")
      (footprint "eagle-import:M0805")
      (libsource (lib "eagle-import") (part "R-EU_M0805"))
    )
    (comp (ref "R97")
      (value "1K")
      (footprint "eagle-import:M0805")
      (libsource (lib "eagle-import") (part "R-EU_M0805"))
    )
    (comp (ref "R98")
      (value "1K")
      (footprint "eagle-import:M0805")
      (libsource (lib "eagle-import") (part "R-EU_M0805"))
    )
    (comp (ref "R99")
      (value "1K")
      (footprint "eagle-import:M0805")
      (libsource (lib "eagle-import") (part "R-EU_M0805"))
    )
    (comp (ref "R100")
      (value "1K")
      (footprint "eagle-import:M0805")
      (libsource (lib "eagle-import") (part "R-EU_M0805"))
    )
    (comp (ref "R101")
      (value "1K")
      (footprint "eagle-import:M0805")
      (libsource (lib "eagle-import") (part "R-EU_M0805"))
    )
    (comp (ref "R102")
      (value "1K")
      (footprint "eagle-import:M0805")
      (libsource (lib "eagle-import") (part "R-EU_M0805"))
    )
    (comp (ref "R103")
      (value "1K")
      (footprint "eagle-import:M0805")
      (libsource (lib "eagle-import") (part "R-EU_M0805"))
    )
    (comp (ref "R104")
      (value "1K")
      (footprint "eagle-import:M0805")
      (libsource (lib "eagle-import") (part "R-EU_M0805"))
    )
    (comp (ref "R105")
      (value "1K")
      (footprint "eagle-import:M0805")
      (libsource (lib "eagle-import") (part "R-EU_M0805"))
    )
    (comp (ref "R106")
      (value "1K")
      (footprint "eagle-import:M0805")
      (libsource (lib "eagle-import") (part "R-EU_M0805"))
    )
    (comp (ref "R107")
      (value "1K")
      (footprint "eagle-import:M0805")
      (libsource (lib "eagle-import") (part "R-EU_M0805"))
    )
    (comp (ref "R108")
      (value "1K")
      (footprint "eagle-import:M0805")
      (libsource (lib "eagle-import") (part "R-EU_M0805"))
    )
    (comp (ref "R109")
      (value "1K")
      (footprint "eagle-import:M0805")
      (libsource (lib "eagle-import") (part "R-EU_M0805"))
    )
    (comp (ref "R110")
      (value "1K")
      (footprint "eagle-import:M0805")
      (libsource (lib "eagle-import") (part "R-EU_M0805"))
    )
    (comp (ref "R111")
      (value "1K")
      (footprint "eagle-import:M0805")
      (libsource (lib "eagle-import") (part "R-EU_M0805"))
    )
    (comp (ref "R112")
      (value "1K")
      (footprint "eagle-import:M0805")
      (libsource (lib "eagle-import") (part "R-EU_M0805"))
    )
    (comp (ref "R113")
      (value "1K")
      (footprint "eagle-import:M0805")
      (libsource (lib "eagle-import") (part "R-EU_M0805"))
    )
    (comp (ref "R114")
      (value "1K")
      (footprint "eagle-import:M0805")
      (libsource (lib "eagle-import") (part "R-EU_M0805"))
    )
    (comp (ref "R115")
      (value "1K")
      (footprint "eagle-import:M0805")
      (libsource (lib "eagle-import") (part "R-EU_M0805"))
    )
    (comp (ref "R116")
      (value "1K")
      (footprint "eagle-import:M0805")
      (libsource (lib "eagle-import") (part "R-EU_M0805"))
    )
    (comp (ref "R117")
      (value "1K")
      (footprint "eagle-import:M0805")
      (libsource (lib "eagle-import") (part "R-EU_M0805"))
    )
    (comp (ref "R118")
      (value "1K")
      (footprint "eagle-import:M0805")
      (libsource (lib "eagle-import") (part "R-EU_M0805"))
    )
    (comp (ref "R119")
      (value "1K")
      (footprint "eagle-import:M0805")
      (libsource (lib "eagle-import") (part "R-EU_M0805"))
    )
    (comp (ref "R120")
      (value "1K")
      (footprint "eagle-import:M0805")
      (libsource (lib "eagle-import") (part "R-EU_M0805"))
    )
    (comp (ref "U$1")
      (value "FE16-3")
      (footprint "eagle-import:FE16-3")
      (libsource (lib "eagle-import") (part "FE16-3"))
    )
    (comp (ref "U$2")
      (value "FE03-1")
      (footprint "eagle-import:FE03-1")
      (libsource (lib "eagle-import") (part "FE03-1"))
    )
    (comp (ref "JP4")
      (value "M04PTH")
      (footprint "eagle-import:1X04")
      (libsource (lib "eagle-import") (part "M04PTH"))
    )
    (comp (ref "LED5")
      (value "LEDCHIPLED_0805")
      (footprint "eagle-import:CHIPLED_0805")
      (libsource (lib "eagle-import") (part "LEDCHIPLED_0805"))
    )
    (comp (ref "LED6")
      (value "LEDCHIPLED_0805")
      (footprint "eagle-import:CHIPLED_0805")
      (libsource (lib "eagle-import") (part "LEDCHIPLED_0805"))
    )
    (comp (ref "LED7")
      (value "LEDCHIPLED_0805")
      (footprint "eagle-import:CHIPLED_0805")
      (libsource (lib "eagle-import") (part "LEDCHIPLED_0805"))
    )
    (comp (ref "LED8")
      (value "LEDCHIPLED_0805")
      (footprint "eagle-import:CHIPLED_0805")
      (libsource (lib "eagle-import") (part "LEDCHIPLED_0805"))
    )
    (comp (ref "LED9")
      (value "LEDCHIPLED_0805")
      (footprint "eagle-import:CHIPLED_0805")
      (libsource (lib "eagle-import") (part "LEDCHIPLED_0805"))
    )
    (comp (ref "LED10")
      (value "LEDCHIPLED_0805")
      (footprint "eagle-import:CHIPLED_0805")
      (libsource (lib "eagle-import") (part "LEDCHIPLED_0805"))
    )
    (comp (ref "LED11")
      (value "LEDCHIPLED_0805")
      (footprint "eagle-import:CHIPLED_0805")
      (libsource (lib "eagle-import") (part "LEDCHIPLED_0805"))
    )
    (comp (ref "LED12")
      (value "LEDCHIPLED_0805")
      (footprint "eagle-import:CHIPLED_0805")
      (libsource (lib "eagle-import") (part "LEDCHIPLED_0805"))
    )
    (comp (ref "LED13")
      (value "LEDCHIPLED_0805")
      (footprint "eagle-import:CHIPLED_0805")
      (libsource (lib "eagle-import") (part "LEDCHIPLED_0805"))
    )
    (comp (ref "LED14")
      (value "LEDCHIPLED_0805")
      (footprint "eagle-import:CHIPLED_0805")
      (libsource (lib "eagle-import") (part "LEDCHIPLED_0805"))
    )
    (comp (ref "LED15")
      (value "LEDCHIPLED_0805")
      (footprint "eagle-import:CHIPLED_0805")
      (libsource (lib "eagle-import") (part "LEDCHIPLED_0805"))
    )
    (comp (ref "LED16")
      (value "LEDCHIPLED_0805")
      (footprint "eagle-import:CHIPLED_0805")
      (libsource (lib "eagle-import") (part "LEDCHIPLED_0805"))
    )
    (comp (ref "LED17")
      (value "LEDCHIPLED_0805")
      (footprint "eagle-import:CHIPLED_0805")
      (libsource (lib "eagle-import") (part "LEDCHIPLED_0805"))
    )
    (comp (ref "LED18")
      (value "LEDCHIPLED_0805")
      (footprint "eagle-import:CHIPLED_0805")
      (libsource (lib "eagle-import") (part "LEDCHIPLED_0805"))
    )
    (comp (ref "LED19")
      (value "LEDCHIPLED_0805")
      (footprint "eagle-import:CHIPLED_0805")
      (libsource (lib "eagle-import") (part "LEDCHIPLED_0805"))
    )
    (comp (ref "LED20")
      (value "LEDCHIPLED_0805")
      (footprint "eagle-import:CHIPLED_0805")
      (libsource (lib "eagle-import") (part "LEDCHIPLED_0805"))
    )
    (comp (ref "LED21")
      (value "LEDCHIPLED_0805")
      (footprint "eagle-import:CHIPLED_0805")
      (libsource (lib "eagle-import") (part "LEDCHIPLED_0805"))
    )
    (comp (ref "LED22")
      (value "LEDCHIPLED_0805")
      (footprint "eagle-import:CHIPLED_0805")
      (libsource (lib "eagle-import") (part "LEDCHIPLED_0805"))
    )
    (comp (ref "LED23")
      (value "LEDCHIPLED_0805")
      (footprint "eagle-import:CHIPLED_0805")
      (libsource (lib "eagle-import") (part "LEDCHIPLED_0805"))
    )
    (comp (ref "LED24")
      (value "LEDCHIPLED_0805")
      (footprint "eagle-import:CHIPLED_0805")
      (libsource (lib "eagle-import") (part "LEDCHIPLED_0805"))
    )
    (comp (ref "LED25")
      (value "LEDCHIPLED_0805")
      (footprint "eagle-import:CHIPLED_0805")
      (libsource (lib "eagle-import") (part "LEDCHIPLED_0805"))
    )
    (comp (ref "LED26")
      (value "LEDCHIPLED_0805")
      (footprint "eagle-import:CHIPLED_0805")
      (libsource (lib "eagle-import") (part "LEDCHIPLED_0805"))
    )
    (comp (ref "LED27")
      (value "LEDCHIPLED_0805")
      (footprint "eagle-import:CHIPLED_0805")
      (libsource (lib "eagle-import") (part "LEDCHIPLED_0805"))
    )
    (comp (ref "LED28")
      (value "LEDCHIPLED_0805")
      (footprint "eagle-import:CHIPLED_0805")
      (libsource (lib "eagle-import") (part "LEDCHIPLED_0805"))
    )
    (comp (ref "LED29")
      (value "LEDCHIPLED_0805")
      (footprint "eagle-import:CHIPLED_0805")
      (libsource (lib "eagle-import") (part "LEDCHIPLED_0805"))
    )
    (comp (ref "LED30")
      (value "LEDCHIPLED_0805")
      (footprint "eagle-import:CHIPLED_0805")
      (libsource (lib "eagle-import") (part "LEDCHIPLED_0805"))
    )
    (comp (ref "LED31")
      (value "LEDCHIPLED_0805")
      (footprint "eagle-import:CHIPLED_0805")
      (libsource (lib "eagle-import") (part "LEDCHIPLED_0805"))
    )
    (comp (ref "LED32")
      (value "LEDCHIPLED_0805")
      (footprint "eagle-import:CHIPLED_0805")
      (libsource (lib "eagle-import") (part "LEDCHIPLED_0805"))
    )
    (comp (ref "LED33")
      (value "LEDCHIPLED_0805")
      (footprint "eagle-import:CHIPLED_0805")
      (libsource (lib "eagle-import") (part "LEDCHIPLED_0805"))
    )
    (comp (ref "LED34")
      (value "LEDCHIPLED_0805")
      (footprint "eagle-import:CHIPLED_0805")
      (libsource (lib "eagle-import") (part "LEDCHIPLED_0805"))
    )
    (comp (ref "LED35")
      (value "LEDCHIPLED_0805")
      (footprint "eagle-import:CHIPLED_0805")
      (libsource (lib "eagle-import") (part "LEDCHIPLED_0805"))
    )
    (comp (ref "LED36")
      (value "LEDCHIPLED_0805")
      (footprint "eagle-import:CHIPLED_0805")
      (libsource (lib "eagle-import") (part "LEDCHIPLED_0805"))
    )
    (comp (ref "LED37")
      (value "LEDCHIPLED_0805")
      (footprint "eagle-import:CHIPLED_0805")
      (libsource (lib "eagle-import") (part "LEDCHIPLED_0805"))
    )
    (comp (ref "LED38")
      (value "LEDCHIPLED_0805")
      (footprint "eagle-import:CHIPLED_0805")
      (libsource (lib "eagle-import") (part "LEDCHIPLED_0805"))
    )
    (comp (ref "LED39")
      (value "LEDCHIPLED_0805")
      (footprint "eagle-import:CHIPLED_0805")
      (libsource (lib "eagle-import") (part "LEDCHIPLED_0805"))
    )
    (comp (ref "LED40")
      (value "LEDCHIPLED_0805")
      (footprint "eagle-import:CHIPLED_0805")
      (libsource (lib "eagle-import") (part "LEDCHIPLED_0805"))
    )
    (comp (ref "LED41")
      (value "LEDCHIPLED_0805")
      (footprint "eagle-import:CHIPLED_0805")
      (libsource (lib "eagle-import") (part "LEDCHIPLED_0805"))
    )
    (comp (ref "LED42")
      (value "LEDCHIPLED_0805")
      (footprint "eagle-import:CHIPLED_0805")
      (libsource (lib "eagle-import") (part "LEDCHIPLED_0805"))
    )
    (comp (ref "LED43")
      (value "LEDCHIPLED_0805")
      (footprint "eagle-import:CHIPLED_0805")
      (libsource (lib "eagle-import") (part "LEDCHIPLED_0805"))
    )
    (comp (ref "LED44")
      (value "LEDCHIPLED_0805")
      (footprint "eagle-import:CHIPLED_0805")
      (libsource (lib "eagle-import") (part "LEDCHIPLED_0805"))
    )
    (comp (ref "LED45")
      (value "LEDCHIPLED_0805")
      (footprint "eagle-import:CHIPLED_0805")
      (libsource (lib "eagle-import") (part "LEDCHIPLED_0805"))
    )
    (comp (ref "LED46")
      (value "LEDCHIPLED_0805")
      (footprint "eagle-import:CHIPLED_0805")
      (libsource (lib "eagle-import") (part "LEDCHIPLED_0805"))
    )
    (comp (ref "LED47")
      (value "LEDCHIPLED_0805")
      (footprint "eagle-import:CHIPLED_0805")
      (libsource (lib "eagle-import") (part "LEDCHIPLED_0805"))
    )
    (comp (ref "LED48")
      (value "LEDCHIPLED_0805")
      (footprint "eagle-import:CHIPLED_0805")
      (libsource (lib "eagle-import") (part "LEDCHIPLED_0805"))
    )
    (comp (ref "LED49")
      (value "LEDCHIPLED_0805")
      (footprint "eagle-import:CHIPLED_0805")
      (libsource (lib "eagle-import") (part "LEDCHIPLED_0805"))
    )
    (comp (ref "LED50")
      (value "LEDCHIPLED_0805")
      (footprint "eagle-import:CHIPLED_0805")
      (libsource (lib "eagle-import") (part "LEDCHIPLED_0805"))
    )
    (comp (ref "LED51")
      (value "LEDCHIPLED_0805")
      (footprint "eagle-import:CHIPLED_0805")
      (libsource (lib "eagle-import") (part "LEDCHIPLED_0805"))
    )
    (comp (ref "LED52")
      (value "LEDCHIPLED_0805")
      (footprint "eagle-import:CHIPLED_0805")
      (libsource (lib "eagle-import") (part "LEDCHIPLED_0805"))
    )
    (comp (ref "LED53")
      (value "LEDCHIPLED_0805")
      (footprint "eagle-import:CHIPLED_0805")
      (libsource (lib "eagle-import") (part "LEDCHIPLED_0805"))
    )
    (comp (ref "LED54")
      (value "LEDCHIPLED_0805")
      (footprint "eagle-import:CHIPLED_0805")
      (libsource (lib "eagle-import") (part "LEDCHIPLED_0805"))
    )
    (comp (ref "LED55")
      (value "LEDCHIPLED_0805")
      (footprint "eagle-import:CHIPLED_0805")
      (libsource (lib "eagle-import") (part "LEDCHIPLED_0805"))
    )
    (comp (ref "LED56")
      (value "LEDCHIPLED_0805")
      (footprint "eagle-import:CHIPLED_0805")
      (libsource (lib "eagle-import") (part "LEDCHIPLED_0805"))
    )
    (comp (ref "LED57")
      (value "LEDCHIPLED_0805")
      (footprint "eagle-import:CHIPLED_0805")
      (libsource (lib "eagle-import") (part "LEDCHIPLED_0805"))
    )
    (comp (ref "LED58")
      (value "LEDCHIPLED_0805")
      (footprint "eagle-import:CHIPLED_0805")
      (libsource (lib "eagle-import") (part "LEDCHIPLED_0805"))
    )
    (comp (ref "LED59")
      (value "LEDCHIPLED_0805")
      (footprint "eagle-import:CHIPLED_0805")
      (libsource (lib "eagle-import") (part "LEDCHIPLED_0805"))
    )
    (comp (ref "LED60")
      (value "LEDCHIPLED_0805")
      (footprint "eagle-import:CHIPLED_0805")
      (libsource (lib "eagle-import") (part "LEDCHIPLED_0805"))
    )
    (comp (ref "LED61")
      (value "LEDCHIPLED_0805")
      (footprint "eagle-import:CHIPLED_0805")
      (libsource (lib "eagle-import") (part "LEDCHIPLED_0805"))
    )
    (comp (ref "LED62")
      (value "LEDCHIPLED_0805")
      (footprint "eagle-import:CHIPLED_0805")
      (libsource (lib "eagle-import") (part "LEDCHIPLED_0805"))
    )
    (comp (ref "LED63")
      (value "LEDCHIPLED_0805")
      (footprint "eagle-import:CHIPLED_0805")
      (libsource (lib "eagle-import") (part "LEDCHIPLED_0805"))
    )
    (comp (ref "LED64")
      (value "LEDCHIPLED_0805")
      (footprint "eagle-import:CHIPLED_0805")
      (libsource (lib "eagle-import") (part "LEDCHIPLED_0805"))
    )
    (comp (ref "LED65")
      (value "LEDCHIPLED_0805")
      (footprint "eagle-import:CHIPLED_0805")
      (libsource (lib "eagle-import") (part "LEDCHIPLED_0805"))
    )
    (comp (ref "LED66")
      (value "LEDCHIPLED_0805")
      (footprint "eagle-import:CHIPLED_0805")
      (libsource (lib "eagle-import") (part "LEDCHIPLED_0805"))
    )
    (comp (ref "LED67")
      (value "LEDCHIPLED_0805")
      (footprint "eagle-import:CHIPLED_0805")
      (libsource (lib "eagle-import") (part "LEDCHIPLED_0805"))
    )
    (comp (ref "LED68")
      (value "LEDCHIPLED_0805")
      (footprint "eagle-import:CHIPLED_0805")
      (libsource (lib "eagle-import") (part "LEDCHIPLED_0805"))
    )
    (comp (ref "R8")
      (value "1K")
      (footprint "eagle-import:M0805")
      (libsource (lib "eagle-import") (part "R-EU_M0805"))
    )
    (comp (ref "R9")
      (value "1K")
      (footprint "eagle-import:M0805")
      (libsource (lib "eagle-import") (part "R-EU_M0805"))
    )
    (comp (ref "R10")
      (value "1K")
      (footprint "eagle-import:M0805")
      (libsource (lib "eagle-import") (part "R-EU_M0805"))
    )
    (comp (ref "R11")
      (value "1K")
      (footprint "eagle-import:M0805")
      (libsource (lib "eagle-import") (part "R-EU_M0805"))
    )
    (comp (ref "R12")
      (value "1K")
      (footprint "eagle-import:M0805")
      (libsource (lib "eagle-import") (part "R-EU_M0805"))
    )
    (comp (ref "R13")
      (value "1K")
      (footprint "eagle-import:M0805")
      (libsource (lib "eagle-import") (part "R-EU_M0805"))
    )
    (comp (ref "R14")
      (value "1K")
      (footprint "eagle-import:M0805")
      (libsource (lib "eagle-import") (part "R-EU_M0805"))
    )
    (comp (ref "R15")
      (value "1K")
      (footprint "eagle-import:M0805")
      (libsource (lib "eagle-import") (part "R-EU_M0805"))
    )
    (comp (ref "R16")
      (value "1K")
      (footprint "eagle-import:M0805")
      (libsource (lib "eagle-import") (part "R-EU_M0805"))
    )
    (comp (ref "R17")
      (value "1K")
      (footprint "eagle-import:M0805")
      (libsource (lib "eagle-import") (part "R-EU_M0805"))
    )
    (comp (ref "R18")
      (value "1K")
      (footprint "eagle-import:M0805")
      (libsource (lib "eagle-import") (part "R-EU_M0805"))
    )
    (comp (ref "R19")
      (value "1K")
      (footprint "eagle-import:M0805")
      (libsource (lib "eagle-import") (part "R-EU_M0805"))
    )
    (comp (ref "R20")
      (value "1K")
      (footprint "eagle-import:M0805")
      (libsource (lib "eagle-import") (part "R-EU_M0805"))
    )
    (comp (ref "R21")
      (value "1K")
      (footprint "eagle-import:M0805")
      (libsource (lib "eagle-import") (part "R-EU_M0805"))
    )
    (comp (ref "R22")
      (value "1K")
      (footprint "eagle-import:M0805")
      (libsource (lib "eagle-import") (part "R-EU_M0805"))
    )
    (comp (ref "R23")
      (value "1K")
      (footprint "eagle-import:M0805")
      (libsource (lib "eagle-import") (part "R-EU_M0805"))
    )
    (comp (ref "R24")
      (value "1K")
      (footprint "eagle-import:M0805")
      (libsource (lib "eagle-import") (part "R-EU_M0805"))
    )
    (comp (ref "R25")
      (value "1K")
      (footprint "eagle-import:M0805")
      (libsource (lib "eagle-import") (part "R-EU_M0805"))
    )
    (comp (ref "R26")
      (value "1K")
      (footprint "eagle-import:M0805")
      (libsource (lib "eagle-import") (part "R-EU_M0805"))
    )
    (comp (ref "R28")
      (value "1K")
      (footprint "eagle-import:M0805")
      (libsource (lib "eagle-import") (part "R-EU_M0805"))
    )
    (comp (ref "R29")
      (value "1K")
      (footprint "eagle-import:M0805")
      (libsource (lib "eagle-import") (part "R-EU_M0805"))
    )
    (comp (ref "R30")
      (value "1K")
      (footprint "eagle-import:M0805")
      (libsource (lib "eagle-import") (part "R-EU_M0805"))
    )
    (comp (ref "R31")
      (value "1K")
      (footprint "eagle-import:M0805")
      (libsource (lib "eagle-import") (part "R-EU_M0805"))
    )
    (comp (ref "R32")
      (value "1K")
      (footprint "eagle-import:M0805")
      (libsource (lib "eagle-import") (part "R-EU_M0805"))
    )
    (comp (ref "R33")
      (value "1K")
      (footprint "eagle-import:M0805")
      (libsource (lib "eagle-import") (part "R-EU_M0805"))
    )
    (comp (ref "R34")
      (value "1K")
      (footprint "eagle-import:M0805")
      (libsource (lib "eagle-import") (part "R-EU_M0805"))
    )
    (comp (ref "R35")
      (value "1K")
      (footprint "eagle-import:M0805")
      (libsource (lib "eagle-import") (part "R-EU_M0805"))
    )
    (comp (ref "R36")
      (value "1K")
      (footprint "eagle-import:M0805")
      (libsource (lib "eagle-import") (part "R-EU_M0805"))
    )
    (comp (ref "R37")
      (value "1K")
      (footprint "eagle-import:M0805")
      (libsource (lib "eagle-import") (part "R-EU_M0805"))
    )
    (comp (ref "R38")
      (value "1K")
      (footprint "eagle-import:M0805")
      (libsource (lib "eagle-import") (part "R-EU_M0805"))
    )
    (comp (ref "R39")
      (value "1K")
      (footprint "eagle-import:M0805")
      (libsource (lib "eagle-import") (part "R-EU_M0805"))
    )
    (comp (ref "R40")
      (value "1K")
      (footprint "eagle-import:M0805")
      (libsource (lib "eagle-import") (part "R-EU_M0805"))
    )
    (comp (ref "R41")
      (value "1K")
      (footprint "eagle-import:M0805")
      (libsource (lib "eagle-import") (part "R-EU_M0805"))
    )
    (comp (ref "R42")
      (value "1K")
      (footprint "eagle-import:M0805")
      (libsource (lib "eagle-import") (part "R-EU_M0805"))
    )
    (comp (ref "R43")
      (value "1K")
      (footprint "eagle-import:M0805")
      (libsource (lib "eagle-import") (part "R-EU_M0805"))
    )
    (comp (ref "R44")
      (value "1K")
      (footprint "eagle-import:M0805")
      (libsource (lib "eagle-import") (part "R-EU_M0805"))
    )
    (comp (ref "R45")
      (value "1K")
      (footprint "eagle-import:M0805")
      (libsource (lib "eagle-import") (part "R-EU_M0805"))
    )
    (comp (ref "R46")
      (value "1K")
      (footprint "eagle-import:M0805")
      (libsource (lib "eagle-import") (part "R-EU_M0805"))
    )
    (comp (ref "R47")
      (value "1K")
      (footprint "eagle-import:M0805")
      (libsource (lib "eagle-import") (part "R-EU_M0805"))
    )
    (comp (ref "R48")
      (value "1K")
      (footprint "eagle-import:M0805")
      (libsource (lib "eagle-import") (part "R-EU_M0805"))
    )
    (comp (ref "R49")
      (value "1K")
      (footprint "eagle-import:M0805")
      (libsource (lib "eagle-import") (part "R-EU_M0805"))
    )
    (comp (ref "R50")
      (value "1K")
      (footprint "eagle-import:M0805")
      (libsource (lib "eagle-import") (part "R-EU_M0805"))
    )
    (comp (ref "R51")
      (value "1K")
      (footprint "eagle-import:M0805")
      (libsource (lib "eagle-import") (part "R-EU_M0805"))
    )
    (comp (ref "R52")
      (value "1K")
      (footprint "eagle-import:M0805")
      (libsource (lib "eagle-import") (part "R-EU_M0805"))
    )
    (comp (ref "R53")
      (value "1K")
      (footprint "eagle-import:M0805")
      (libsource (lib "eagle-import") (part "R-EU_M0805"))
    )
    (comp (ref "R54")
      (value "1K")
      (footprint "eagle-import:M0805")
      (libsource (lib "eagle-import") (part "R-EU_M0805"))
    )
    (comp (ref "R55")
      (value "1K")
      (footprint "eagle-import:M0805")
      (libsource (lib "eagle-import") (part "R-EU_M0805"))
    )
    (comp (ref "R56")
      (value "1K")
      (footprint "eagle-import:M0805")
      (libsource (lib "eagle-import") (part "R-EU_M0805"))
    )
    (comp (ref "R57")
      (value "1K")
      (footprint "eagle-import:M0805")
      (libsource (lib "eagle-import") (part "R-EU_M0805"))
    )
    (comp (ref "R58")
      (value "1K")
      (footprint "eagle-import:M0805")
      (libsource (lib "eagle-import") (part "R-EU_M0805"))
    )
    (comp (ref "R59")
      (value "1K")
      (footprint "eagle-import:M0805")
      (libsource (lib "eagle-import") (part "R-EU_M0805"))
    )
    (comp (ref "R60")
      (value "1K")
      (footprint "eagle-import:M0805")
      (libsource (lib "eagle-import") (part "R-EU_M0805"))
    )
    (comp (ref "R61")
      (value "1K")
      (footprint "eagle-import:M0805")
      (libsource (lib "eagle-import") (part "R-EU_M0805"))
    )
    (comp (ref "R62")
      (value "1K")
      (footprint "eagle-import:M0805")
      (libsource (lib "eagle-import") (part "R-EU_M0805"))
    )
    (comp (ref "R63")
      (value "1K")
      (footprint "eagle-import:M0805")
      (libsource (lib "eagle-import") (part "R-EU_M0805"))
    )
    (comp (ref "R64")
      (value "1K")
      (footprint "eagle-import:M0805")
      (libsource (lib "eagle-import") (part "R-EU_M0805"))
    )
    (comp (ref "R65")
      (value "1K")
      (footprint "eagle-import:M0805")
      (libsource (lib "eagle-import") (part "R-EU_M0805"))
    )
    (comp (ref "R66")
      (value "1K")
      (footprint "eagle-import:M0805")
      (libsource (lib "eagle-import") (part "R-EU_M0805"))
    )
    (comp (ref "R67")
      (value "1K")
      (footprint "eagle-import:M0805")
      (libsource (lib "eagle-import") (part "R-EU_M0805"))
    )
    (comp (ref "R68")
      (value "1K")
      (footprint "eagle-import:M0805")
      (libsource (lib "eagle-import") (part "R-EU_M0805"))
    )
    (comp (ref "R69")
      (value "1K")
      (footprint "eagle-import:M0805")
      (libsource (lib "eagle-import") (part "R-EU_M0805"))
    )
    (comp (ref "R70")
      (value "1K")
      (footprint "eagle-import:M0805")
      (libsource (lib "eagle-import") (part "R-EU_M0805"))
    )
    (comp (ref "R71")
      (value "1K")
      (footprint "eagle-import:M0805")
      (libsource (lib "eagle-import") (part "R-EU_M0805"))
    )
    (comp (ref "R72")
      (value "1K")
      (footprint "eagle-import:M0805")
      (libsource (lib "eagle-import") (part "R-EU_M0805"))
    )
    (comp (ref "SV1")
      (value "FE10-2")
      (footprint "eagle-import:FE10-2")
      (libsource (lib "eagle-import") (part "FE10-2"))
    )
    (comp (ref "SV2")
      (value "FE06-2")
      (footprint "eagle-import:FE06-2")
      (libsource (lib "eagle-import") (part "FE06-2"))
    )
    (comp (ref "SV3")
      (value "FE10-2")
      (footprint "eagle-import:FE10-2")
      (libsource (lib "eagle-import") (part "FE10-2"))
    )
    (comp (ref "SV4")
      (value "FE06-2")
      (footprint "eagle-import:FE06-2")
      (libsource (lib "eagle-import") (part "FE06-2"))
    )
    (comp (ref "JP5")
      (value "M04PTH")
      (footprint "eagle-import:1X04")
      (libsource (lib "eagle-import") (part "M04PTH"))
    )
    (comp (ref "U1")
      (value "ARDUINO_SHIELDNOHOLES")
      (footprint "eagle-import:DUEMILANOVE_SHIELD_NOHOLES")
      (libsource (lib "eagle-import") (part "ARDUINO_SHIELDNOHOLES"))
    )
  )
  (nets
    (net (code "1") (name "+3V3") (class "Default")
      (node (ref "JP5") (pin "2") (pinfunction "2_2") (pintype "passive"))
      (node (ref "P5_VIN") (pin "2") (pinfunction "2_2") (pintype "passive"))
      (node (ref "SV5") (pin "2") (pinfunction "2_2") (pintype "passive"))
    )
    (net (code "2") (name "+5V") (class "Default")
      (node (ref "JP5") (pin "3") (pinfunction "3_3") (pintype "passive"))
      (node (ref "P5_VIN") (pin "3") (pinfunction "3_3") (pintype "passive"))
      (node (ref "SV6") (pin "7") (pinfunction "7_7") (pintype "passive"))
    )
    (net (code "3") (name "AN") (class "Default")
      (node (ref "SV5") (pin "8") (pinfunction "8_8") (pintype "passive"))
      (node (ref "SV7") (pin "11") (pinfunction "11_11") (pintype "passive"))
    )
    (net (code "4") (name "CS") (class "Default")
      (node (ref "SV5") (pin "6") (pinfunction "6_6") (pintype "passive"))
      (node (ref "SV7") (pin "7") (pinfunction "7_7") (pintype "passive"))
    )
    (net (code "5") (name "ENC_A") (class "Default")
      (node (ref "JP2") (pin "3") (pinfunction "3_3") (pintype "passive"))
      (node (ref "JP20") (pin "1") (pinfunction "1_1") (pintype "passive"))
    )
    (net (code "6") (name "ENC_B") (class "Default")
      (node (ref "JP20") (pin "2") (pinfunction "2_2") (pintype "passive"))
      (node (ref "JP3") (pin "3") (pinfunction "3_3") (pintype "passive"))
    )
    (net (code "7") (name "EN_A_B") (class "Default")
      (node (ref "IC1") (pin "1") (pinfunction "1_1") (pintype "passive"))
      (node (ref "IC1") (pin "8") (pinfunction "8_8") (pintype "passive"))
      (node (ref "JP1") (pin "1") (pinfunction "1_1") (pintype "passive"))
      (node (ref "MOT_CONTROL") (pin "3") (pinfunction "3_3") (pintype "passive"))
    )
    (net (code "8") (name "INT") (class "Default")
      (node (ref "SV6") (pin "2") (pinfunction "2_2") (pintype "passive"))
      (node (ref "SV7") (pin "4") (pinfunction "4_4") (pintype "passive"))
    )
    (net (code "9") (name "IN_A") (class "Default")
      (node (ref "IC1") (pin "2") (pinfunction "2_2") (pintype "passive"))
      (node (ref "MOT_CONTROL") (pin "2") (pinfunction "2_2") (pintype "passive"))
    )
    (net (code "10") (name "IN_B") (class "Default")
      (node (ref "IC1") (pin "4") (pinfunction "4_4") (pintype "passive"))
      (node (ref "MOT_CONTROL") (pin "1") (pinfunction "1_1") (pintype "passive"))
    )
    (net (code "11") (name "MISO") (class "Default")
      (node (ref "SV5") (pin "4") (pinfunction "4_4") (pintype "passive"))
      (node (ref "SV7") (pin "3") (pinfunction "3_3") (pintype "passive"))
    )
    (net (code "12") (name "MOSI") (class "Default")
      (node (ref "SV5") (pin "3") (pinfunction "3_3") (pintype "passive"))
      (node (ref "SV7") (pin "1") (pinfunction "1_1") (pintype "passive"))
    )
    (net (code "13") (name "Net-(JP1-Pad2)") (class "Default")
      (node (ref "JP1") (pin "2") (pinfunction "2_2") (pintype "passive"))
      (node (ref "R27") (pin "1") (pinfunction "1_1") (pintype "passive"))
    )
    (net (code "14") (name "Net-(JP2-Pad1)") (class "Default")
      (node (ref "JP2") (pin "1") (pinfunction "1_1") (pintype "passive"))
      (node (ref "R1") (pin "2") (pinfunction "2_2") (pintype "passive"))
      (node (ref "SENSOR") (pin "2") (pinfunction "2_2") (pintype "passive"))
    )
    (net (code "15") (name "Net-(JP3-Pad1)") (class "Default")
      (node (ref "JP3") (pin "1") (pinfunction "1_1") (pintype "passive"))
      (node (ref "R6") (pin "2") (pinfunction "2_2") (pintype "passive"))
      (node (ref "SENSOR1") (pin "2") (pinfunction "2_2") (pintype "passive"))
    )
    (net (code "16") (name "Net-(LED1-PadA)") (class "Default")
      (node (ref "LED1") (pin "A") (pinfunction "A_A") (pintype "passive"))
      (node (ref "R3") (pin "1") (pinfunction "1_1") (pintype "passive"))
    )
    (net (code "17") (name "Net-(LED2-PadA)") (class "Default")
      (node (ref "LED2") (pin "A") (pinfunction "A_A") (pintype "passive"))
      (node (ref "R4") (pin "1") (pinfunction "1_1") (pintype "passive"))
    )
    (net (code "18") (name "Net-(LED3-PadA)") (class "Default")
      (node (ref "LED3") (pin "A") (pinfunction "A_A") (pintype "passive"))
      (node (ref "LED4") (pin "C") (pinfunction "C_C") (pintype "passive"))
      (node (ref "R5") (pin "1") (pinfunction "1_1") (pintype "passive"))
    )
    (net (code "19") (name "Net-(LED5-PadA)") (class "Default")
      (node (ref "LED5") (pin "A") (pinfunction "A_A") (pintype "passive"))
      (node (ref "R8") (pin "1") (pinfunction "1_1") (pintype "passive"))
    )
    (net (code "20") (name "Net-(LED6-PadA)") (class "Default")
      (node (ref "LED6") (pin "A") (pinfunction "A_A") (pintype "passive"))
      (node (ref "R9") (pin "1") (pinfunction "1_1") (pintype "passive"))
    )
    (net (code "21") (name "Net-(LED7-PadA)") (class "Default")
      (node (ref "LED7") (pin "A") (pinfunction "A_A") (pintype "passive"))
      (node (ref "R10") (pin "1") (pinfunction "1_1") (pintype "passive"))
    )
    (net (code "22") (name "Net-(LED8-PadA)") (class "Default")
      (node (ref "LED8") (pin "A") (pinfunction "A_A") (pintype "passive"))
      (node (ref "R11") (pin "1") (pinfunction "1_1") (pintype "passive"))
    )
    (net (code "23") (name "Net-(LED9-PadA)") (class "Default")
      (node (ref "LED9") (pin "A") (pinfunction "A_A") (pintype "passive"))
      (node (ref "R12") (pin "1") (pinfunction "1_1") (pintype "passive"))
    )
    (net (code "24") (name "Net-(LED10-PadA)") (class "Default")
      (node (ref "LED10") (pin "A") (pinfunction "A_A") (pintype "passive"))
      (node (ref "R13") (pin "1") (pinfunction "1_1") (pintype "passive"))
    )
    (net (code "25") (name "Net-(LED11-PadA)") (class "Default")
      (node (ref "LED11") (pin "A") (pinfunction "A_A") (pintype "passive"))
      (node (ref "R14") (pin "1") (pinfunction "1_1") (pintype "passive"))
    )
    (net (code "26") (name "Net-(LED12-PadA)") (class "Default")
      (node (ref "LED12") (pin "A") (pinfunction "A_A") (pintype "passive"))
      (node (ref "R15") (pin "1") (pinfunction "1_1") (pintype "passive"))
    )
    (net (code "27") (name "Net-(LED13-PadA)") (class "Default")
      (node (ref "LED13") (pin "A") (pinfunction "A_A") (pintype "passive"))
      (node (ref "R16") (pin "1") (pinfunction "1_1") (pintype "passive"))
    )
    (net (code "28") (name "Net-(LED14-PadA)") (class "Default")
      (node (ref "LED14") (pin "A") (pinfunction "A_A") (pintype "passive"))
      (node (ref "R17") (pin "1") (pinfunction "1_1") (pintype "passive"))
    )
    (net (code "29") (name "Net-(LED15-PadA)") (class "Default")
      (node (ref "LED15") (pin "A") (pinfunction "A_A") (pintype "passive"))
      (node (ref "R18") (pin "1") (pinfunction "1_1") (pintype "passive"))
    )
    (net (code "30") (name "Net-(LED16-PadA)") (class "Default")
      (node (ref "LED16") (pin "A") (pinfunction "A_A") (pintype "passive"))
      (node (ref "R19") (pin "1") (pinfunction "1_1") (pintype "passive"))
    )
    (net (code "31") (name "Net-(LED17-PadA)") (class "Default")
      (node (ref "LED17") (pin "A") (pinfunction "A_A") (pintype "passive"))
      (node (ref "R20") (pin "1") (pinfunction "1_1") (pintype "passive"))
    )
    (net (code "32") (name "Net-(LED18-PadA)") (class "Default")
      (node (ref "LED18") (pin "A") (pinfunction "A_A") (pintype "passive"))
      (node (ref "R21") (pin "1") (pinfunction "1_1") (pintype "passive"))
    )
    (net (code "33") (name "Net-(LED19-PadA)") (class "Default")
      (node (ref "LED19") (pin "A") (pinfunction "A_A") (pintype "passive"))
      (node (ref "R22") (pin "1") (pinfunction "1_1") (pintype "passive"))
    )
    (net (code "34") (name "Net-(LED20-PadA)") (class "Default")
      (node (ref "LED20") (pin "A") (pinfunction "A_A") (pintype "passive"))
      (node (ref "R23") (pin "1") (pinfunction "1_1") (pintype "passive"))
    )
    (net (code "35") (name "Net-(LED21-PadA)") (class "Default")
      (node (ref "LED21") (pin "A") (pinfunction "A_A") (pintype "passive"))
      (node (ref "R24") (pin "1") (pinfunction "1_1") (pintype "passive"))
    )
    (net (code "36") (name "Net-(LED22-PadA)") (class "Default")
      (node (ref "LED22") (pin "A") (pinfunction "A_A") (pintype "passive"))
      (node (ref "R25") (pin "1") (pinfunction "1_1") (pintype "passive"))
    )
    (net (code "37") (name "Net-(LED23-PadA)") (class "Default")
      (node (ref "LED23") (pin "A") (pinfunction "A_A") (pintype "passive"))
      (node (ref "R26") (pin "1") (pinfunction "1_1") (pintype "passive"))
    )
    (net (code "38") (name "Net-(LED24-PadA)") (class "Default")
      (node (ref "LED24") (pin "A") (pinfunction "A_A") (pintype "passive"))
      (node (ref "R28") (pin "1") (pinfunction "1_1") (pintype "passive"))
    )
    (net (code "39") (name "Net-(LED25-PadA)") (class "Default")
      (node (ref "LED25") (pin "A") (pinfunction "A_A") (pintype "passive"))
      (node (ref "R29") (pin "1") (pinfunction "1_1") (pintype "passive"))
    )
    (net (code "40") (name "Net-(LED26-PadA)") (class "Default")
      (node (ref "LED26") (pin "A") (pinfunction "A_A") (pintype "passive"))
      (node (ref "R30") (pin "1") (pinfunction "1_1") (pintype "passive"))
    )
    (net (code "41") (name "Net-(LED27-PadA)") (class "Default")
      (node (ref "LED27") (pin "A") (pinfunction "A_A") (pintype "passive"))
      (node (ref "R31") (pin "1") (pinfunction "1_1") (pintype "passive"))
    )
    (net (code "42") (name "Net-(LED28-PadA)") (class "Default")
      (node (ref "LED28") (pin "A") (pinfunction "A_A") (pintype "passive"))
      (node (ref "R32") (pin "1") (pinfunction "1_1") (pintype "passive"))
    )
    (net (code "43") (name "Net-(LED29-PadA)") (class "Default")
      (node (ref "LED29") (pin "A") (pinfunction "A_A") (pintype "passive"))
      (node (ref "R33") (pin "1") (pinfunction "1_1") (pintype "passive"))
    )
    (net (code "44") (name "Net-(LED30-PadA)") (class "Default")
      (node (ref "LED30") (pin "A") (pinfunction "A_A") (pintype "passive"))
      (node (ref "R34") (pin "1") (pinfunction "1_1") (pintype "passive"))
    )
    (net (code "45") (name "Net-(LED31-PadA)") (class "Default")
      (node (ref "LED31") (pin "A") (pinfunction "A_A") (pintype "passive"))
      (node (ref "R35") (pin "1") (pinfunction "1_1") (pintype "passive"))
    )
    (net (code "46") (name "Net-(LED32-PadA)") (class "Default")
      (node (ref "LED32") (pin "A") (pinfunction "A_A") (pintype "passive"))
      (node (ref "R36") (pin "1") (pinfunction "1_1") (pintype "passive"))
    )
    (net (code "47") (name "Net-(LED33-PadA)") (class "Default")
      (node (ref "LED33") (pin "A") (pinfunction "A_A") (pintype "passive"))
      (node (ref "R37") (pin "1") (pinfunction "1_1") (pintype "passive"))
    )
    (net (code "48") (name "Net-(LED34-PadA)") (class "Default")
      (node (ref "LED34") (pin "A") (pinfunction "A_A") (pintype "passive"))
      (node (ref "R38") (pin "1") (pinfunction "1_1") (pintype "passive"))
    )
    (net (code "49") (name "Net-(LED35-PadA)") (class "Default")
      (node (ref "LED35") (pin "A") (pinfunction "A_A") (pintype "passive"))
      (node (ref "R39") (pin "1") (pinfunction "1_1") (pintype "passive"))
    )
    (net (code "50") (name "Net-(LED36-PadA)") (class "Default")
      (node (ref "LED36") (pin "A") (pinfunction "A_A") (pintype "passive"))
      (node (ref "R40") (pin "1") (pinfunction "1_1") (pintype "passive"))
    )
    (net (code "51") (name "Net-(LED37-PadA)") (class "Default")
      (node (ref "LED37") (pin "A") (pinfunction "A_A") (pintype "passive"))
      (node (ref "R41") (pin "1") (pinfunction "1_1") (pintype "passive"))
    )
    (net (code "52") (name "Net-(LED38-PadA)") (class "Default")
      (node (ref "LED38") (pin "A") (pinfunction "A_A") (pintype "passive"))
      (node (ref "R42") (pin "1") (pinfunction "1_1") (pintype "passive"))
    )
    (net (code "53") (name "Net-(LED39-PadA)") (class "Default")
      (node (ref "LED39") (pin "A") (pinfunction "A_A") (pintype "passive"))
      (node (ref "R43") (pin "1") (pinfunction "1_1") (pintype "passive"))
    )
    (net (code "54") (name "Net-(LED40-PadA)") (class "Default")
      (node (ref "LED40") (pin "A") (pinfunction "A_A") (pintype "passive"))
      (node (ref "R44") (pin "1") (pinfunction "1_1") (pintype "passive"))
    )
    (net (code "55") (name "Net-(LED41-PadA)") (class "Default")
      (node (ref "LED41") (pin "A") (pinfunction "A_A") (pintype "passive"))
      (node (ref "R45") (pin "1") (pinfunction "1_1") (pintype "passive"))
    )
    (net (code "56") (name "Net-(LED42-PadA)") (class "Default")
      (node (ref "LED42") (pin "A") (pinfunction "A_A") (pintype "passive"))
      (node (ref "R46") (pin "1") (pinfunction "1_1") (pintype "passive"))
    )
    (net (code "57") (name "Net-(LED43-PadA)") (class "Default")
      (node (ref "LED43") (pin "A") (pinfunction "A_A") (pintype "passive"))
      (node (ref "R47") (pin "1") (pinfunction "1_1") (pintype "passive"))
    )
    (net (code "58") (name "Net-(LED44-PadA)") (class "Default")
      (node (ref "LED44") (pin "A") (pinfunction "A_A") (pintype "passive"))
      (node (ref "R48") (pin "1") (pinfunction "1_1") (pintype "passive"))
    )
    (net (code "59") (name "Net-(LED45-PadA)") (class "Default")
      (node (ref "LED45") (pin "A") (pinfunction "A_A") (pintype "passive"))
      (node (ref "R49") (pin "1") (pinfunction "1_1") (pintype "passive"))
    )
    (net (code "60") (name "Net-(LED46-PadA)") (class "Default")
      (node (ref "LED46") (pin "A") (pinfunction "A_A") (pintype "passive"))
      (node (ref "R50") (pin "1") (pinfunction "1_1") (pintype "passive"))
    )
    (net (code "61") (name "Net-(LED47-PadA)") (class "Default")
      (node (ref "LED47") (pin "A") (pinfunction "A_A") (pintype "passive"))
      (node (ref "R51") (pin "1") (pinfunction "1_1") (pintype "passive"))
    )
    (net (code "62") (name "Net-(LED48-PadA)") (class "Default")
      (node (ref "LED48") (pin "A") (pinfunction "A_A") (pintype "passive"))
      (node (ref "R52") (pin "1") (pinfunction "1_1") (pintype "passive"))
    )
    (net (code "63") (name "Net-(LED49-PadA)") (class "Default")
      (node (ref "LED49") (pin "A") (pinfunction "A_A") (pintype "passive"))
      (node (ref "R53") (pin "1") (pinfunction "1_1") (pintype "passive"))
    )
    (net (code "64") (name "Net-(LED50-PadA)") (class "Default")
      (node (ref "LED50") (pin "A") (pinfunction "A_A") (pintype "passive"))
      (node (ref "R54") (pin "1") (pinfunction "1_1") (pintype "passive"))
    )
    (net (code "65") (name "Net-(LED51-PadA)") (class "Default")
      (node (ref "LED51") (pin "A") (pinfunction "A_A") (pintype "passive"))
      (node (ref "R55") (pin "1") (pinfunction "1_1") (pintype "passive"))
    )
    (net (code "66") (name "Net-(LED52-PadA)") (class "Default")
      (node (ref "LED52") (pin "A") (pinfunction "A_A") (pintype "passive"))
      (node (ref "R56") (pin "1") (pinfunction "1_1") (pintype "passive"))
    )
    (net (code "67") (name "Net-(LED53-PadA)") (class "Default")
      (node (ref "LED53") (pin "A") (pinfunction "A_A") (pintype "passive"))
      (node (ref "R57") (pin "1") (pinfunction "1_1") (pintype "passive"))
    )
    (net (code "68") (name "Net-(LED54-PadA)") (class "Default")
      (node (ref "LED54") (pin "A") (pinfunction "A_A") (pintype "passive"))
      (node (ref "R58") (pin "1") (pinfunction "1_1") (pintype "passive"))
    )
    (net (code "69") (name "Net-(LED55-PadA)") (class "Default")
      (node (ref "LED55") (pin "A") (pinfunction "A_A") (pintype "passive"))
      (node (ref "R59") (pin "1") (pinfunction "1_1") (pintype "passive"))
    )
    (net (code "70") (name "Net-(LED56-PadA)") (class "Default")
      (node (ref "LED56") (pin "A") (pinfunction "A_A") (pintype "passive"))
      (node (ref "R60") (pin "1") (pinfunction "1_1") (pintype "passive"))
    )
    (net (code "71") (name "Net-(LED57-PadA)") (class "Default")
      (node (ref "LED57") (pin "A") (pinfunction "A_A") (pintype "passive"))
      (node (ref "R61") (pin "1") (pinfunction "1_1") (pintype "passive"))
    )
    (net (code "72") (name "Net-(LED58-PadA)") (class "Default")
      (node (ref "LED58") (pin "A") (pinfunction "A_A") (pintype "passive"))
      (node (ref "R62") (pin "1") (pinfunction "1_1") (pintype "passive"))
    )
    (net (code "73") (name "Net-(LED59-PadA)") (class "Default")
      (node (ref "LED59") (pin "A") (pinfunction "A_A") (pintype "passive"))
      (node (ref "R63") (pin "1") (pinfunction "1_1") (pintype "passive"))
    )
    (net (code "74") (name "Net-(LED60-PadA)") (class "Default")
      (node (ref "LED60") (pin "A") (pinfunction "A_A") (pintype "passive"))
      (node (ref "R64") (pin "1") (pinfunction "1_1") (pintype "passive"))
    )
    (net (code "75") (name "Net-(LED61-PadA)") (class "Default")
      (node (ref "LED61") (pin "A") (pinfunction "A_A") (pintype "passive"))
      (node (ref "R65") (pin "1") (pinfunction "1_1") (pintype "passive"))
    )
    (net (code "76") (name "Net-(LED62-PadA)") (class "Default")
      (node (ref "LED62") (pin "A") (pinfunction "A_A") (pintype "passive"))
      (node (ref "R66") (pin "1") (pinfunction "1_1") (pintype "passive"))
    )
    (net (code "77") (name "Net-(LED63-PadA)") (class "Default")
      (node (ref "LED63") (pin "A") (pinfunction "A_A") (pintype "passive"))
      (node (ref "R67") (pin "1") (pinfunction "1_1") (pintype "passive"))
    )
    (net (code "78") (name "Net-(LED64-PadA)") (class "Default")
      (node (ref "LED64") (pin "A") (pinfunction "A_A") (pintype "passive"))
      (node (ref "R68") (pin "1") (pinfunction "1_1") (pintype "passive"))
    )
    (net (code "79") (name "Net-(LED65-PadA)") (class "Default")
      (node (ref "LED65") (pin "A") (pinfunction "A_A") (pintype "passive"))
      (node (ref "R69") (pin "1") (pinfunction "1_1") (pintype "passive"))
    )
    (net (code "80") (name "Net-(LED66-PadA)") (class "Default")
      (node (ref "LED66") (pin "A") (pinfunction "A_A") (pintype "passive"))
      (node (ref "R70") (pin "1") (pinfunction "1_1") (pintype "passive"))
    )
    (net (code "81") (name "Net-(LED67-PadA)") (class "Default")
      (node (ref "LED67") (pin "A") (pinfunction "A_A") (pintype "passive"))
      (node (ref "R71") (pin "1") (pinfunction "1_1") (pintype "passive"))
    )
    (net (code "82") (name "Net-(LED68-PadA)") (class "Default")
      (node (ref "LED68") (pin "A") (pinfunction "A_A") (pintype "passive"))
      (node (ref "R72") (pin "1") (pinfunction "1_1") (pintype "passive"))
    )
    (net (code "83") (name "Net-(LED69-PadA)") (class "Default")
      (node (ref "LED69") (pin "A") (pinfunction "A_A") (pintype "passive"))
      (node (ref "R73") (pin "1") (pinfunction "1_1") (pintype "passive"))
    )
    (net (code "84") (name "Net-(LED70-PadA)") (class "Default")
      (node (ref "LED70") (pin "A") (pinfunction "A_A") (pintype "passive"))
      (node (ref "R74") (pin "1") (pinfunction "1_1") (pintype "passive"))
    )
    (net (code "85") (name "Net-(LED71-PadA)") (class "Default")
      (node (ref "LED71") (pin "A") (pinfunction "A_A") (pintype "passive"))
      (node (ref "R75") (pin "1") (pinfunction "1_1") (pintype "passive"))
    )
    (net (code "86") (name "Net-(LED72-PadA)") (class "Default")
      (node (ref "LED72") (pin "A") (pinfunction "A_A") (pintype "passive"))
      (node (ref "R76") (pin "1") (pinfunction "1_1") (pintype "passive"))
    )
    (net (code "87") (name "Net-(LED73-PadA)") (class "Default")
      (node (ref "LED73") (pin "A") (pinfunction "A_A") (pintype "passive"))
      (node (ref "R77") (pin "1") (pinfunction "1_1") (pintype "passive"))
    )
    (net (code "88") (name "Net-(LED74-PadA)") (class "Default")
      (node (ref "LED74") (pin "A") (pinfunction "A_A") (pintype "passive"))
      (node (ref "R78") (pin "1") (pinfunction "1_1") (pintype "passive"))
    )
    (net (code "89") (name "Net-(LED75-PadA)") (class "Default")
      (node (ref "LED75") (pin "A") (pinfunction "A_A") (pintype "passive"))
      (node (ref "R79") (pin "1") (pinfunction "1_1") (pintype "passive"))
    )
    (net (code "90") (name "Net-(LED76-PadA)") (class "Default")
      (node (ref "LED76") (pin "A") (pinfunction "A_A") (pintype "passive"))
      (node (ref "R80") (pin "1") (pinfunction "1_1") (pintype "passive"))
    )
    (net (code "91") (name "Net-(LED77-PadA)") (class "Default")
      (node (ref "LED77") (pin "A") (pinfunction "A_A") (pintype "passive"))
      (node (ref "R81") (pin "1") (pinfunction "1_1") (pintype "passive"))
    )
    (net (code "92") (name "Net-(LED78-PadA)") (class "Default")
      (node (ref "LED78") (pin "A") (pinfunction "A_A") (pintype "passive"))
      (node (ref "R82") (pin "1") (pinfunction "1_1") (pintype "passive"))
    )
    (net (code "93") (name "Net-(LED79-PadA)") (class "Default")
      (node (ref "LED79") (pin "A") (pinfunction "A_A") (pintype "passive"))
      (node (ref "R83") (pin "1") (pinfunction "1_1") (pintype "passive"))
    )
    (net (code "94") (name "Net-(LED80-PadA)") (class "Default")
      (node (ref "LED80") (pin "A") (pinfunction "A_A") (pintype "passive"))
      (node (ref "R84") (pin "1") (pinfunction "1_1") (pintype "passive"))
    )
    (net (code "95") (name "Net-(LED81-PadA)") (class "Default")
      (node (ref "LED81") (pin "A") (pinfunction "A_A") (pintype "passive"))
      (node (ref "R85") (pin "1") (pinfunction "1_1") (pintype "passive"))
    )
    (net (code "96") (name "Net-(LED82-PadA)") (class "Default")
      (node (ref "LED82") (pin "A") (pinfunction "A_A") (pintype "passive"))
      (node (ref "R86") (pin "1") (pinfunction "1_1") (pintype "passive"))
    )
    (net (code "97") (name "Net-(LED83-PadA)") (class "Default")
      (node (ref "LED83") (pin "A") (pinfunction "A_A") (pintype "passive"))
      (node (ref "R87") (pin "1") (pinfunction "1_1") (pintype "passive"))
    )
    (net (code "98") (name "Net-(LED84-PadA)") (class "Default")
      (node (ref "LED84") (pin "A") (pinfunction "A_A") (pintype "passive"))
      (node (ref "R88") (pin "1") (pinfunction "1_1") (pintype "passive"))
    )
    (net (code "99") (name "Net-(LED85-PadA)") (class "Default")
      (node (ref "LED85") (pin "A") (pinfunction "A_A") (pintype "passive"))
      (node (ref "R89") (pin "1") (pinfunction "1_1") (pintype "passive"))
    )
    (net (code "100") (name "Net-(LED86-PadA)") (class "Default")
      (node (ref "LED86") (pin "A") (pinfunction "A_A") (pintype "passive"))
      (node (ref "R90") (pin "1") (pinfunction "1_1") (pintype "passive"))
    )
    (net (code "101") (name "Net-(LED87-PadA)") (class "Default")
      (node (ref "LED87") (pin "A") (pinfunction "A_A") (pintype "passive"))
      (node (ref "R91") (pin "1") (pinfunction "1_1") (pintype "passive"))
    )
    (net (code "102") (name "Net-(LED88-PadA)") (class "Default")
      (node (ref "LED88") (pin "A") (pinfunction "A_A") (pintype "passive"))
      (node (ref "R92") (pin "1") (pinfunction "1_1") (pintype "passive"))
    )
    (net (code "103") (name "Net-(LED89-PadA)") (class "Default")
      (node (ref "LED89") (pin "A") (pinfunction "A_A") (pintype "passive"))
      (node (ref "R93") (pin "1") (pinfunction "1_1") (pintype "passive"))
    )
    (net (code "104") (name "Net-(LED90-PadA)") (class "Default")
      (node (ref "LED90") (pin "A") (pinfunction "A_A") (pintype "passive"))
      (node (ref "R94") (pin "1") (pinfunction "1_1") (pintype "passive"))
    )
    (net (code "105") (name "Net-(LED91-PadA)") (class "Default")
      (node (ref "LED91") (pin "A") (pinfunction "A_A") (pintype "passive"))
      (node (ref "R95") (pin "1") (pinfunction "1_1") (pintype "passive"))
    )
    (net (code "106") (name "Net-(LED92-PadA)") (class "Default")
      (node (ref "LED92") (pin "A") (pinfunction "A_A") (pintype "passive"))
      (node (ref "R96") (pin "1") (pinfunction "1_1") (pintype "passive"))
    )
    (net (code "107") (name "Net-(LED93-PadA)") (class "Default")
      (node (ref "LED93") (pin "A") (pinfunction "A_A") (pintype "passive"))
      (node (ref "R97") (pin "1") (pinfunction "1_1") (pintype "passive"))
    )
    (net (code "108") (name "Net-(LED94-PadA)") (class "Default")
      (node (ref "LED94") (pin "A") (pinfunction "A_A") (pintype "passive"))
      (node (ref "R98") (pin "1") (pinfunction "1_1") (pintype "passive"))
    )
    (net (code "109") (name "Net-(LED95-PadA)") (class "Default")
      (node (ref "LED95") (pin "A") (pinfunction "A_A") (pintype "passive"))
      (node (ref "R99") (pin "1") (pinfunction "1_1") (pintype "passive"))
    )
    (net (code "110") (name "Net-(LED96-PadA)") (class "Default")
      (node (ref "LED96") (pin "A") (pinfunction "A_A") (pintype "passive"))
      (node (ref "R100") (pin "1") (pinfunction "1_1") (pintype "passive"))
    )
    (net (code "111") (name "Net-(LED97-PadA)") (class "Default")
      (node (ref "LED97") (pin "A") (pinfunction "A_A") (pintype "passive"))
      (node (ref "R101") (pin "1") (pinfunction "1_1") (pintype "passive"))
    )
    (net (code "112") (name "Net-(LED98-PadA)") (class "Default")
      (node (ref "LED98") (pin "A") (pinfunction "A_A") (pintype "passive"))
      (node (ref "R102") (pin "1") (pinfunction "1_1") (pintype "passive"))
    )
    (net (code "113") (name "Net-(LED99-PadA)") (class "Default")
      (node (ref "LED99") (pin "A") (pinfunction "A_A") (pintype "passive"))
      (node (ref "R103") (pin "1") (pinfunction "1_1") (pintype "passive"))
    )
    (net (code "114") (name "Net-(LED100-PadA)") (class "Default")
      (node (ref "LED100") (pin "A") (pinfunction "A_A") (pintype "passive"))
      (node (ref "R104") (pin "1") (pinfunction "1_1") (pintype "passive"))
    )
    (net (code "115") (name "Net-(LED101-PadA)") (class "Default")
      (node (ref "LED101") (pin "A") (pinfunction "A_A") (pintype "passive"))
      (node (ref "R105") (pin "1") (pinfunction "1_1") (pintype "passive"))
    )
    (net (code "116") (name "Net-(LED102-PadA)") (class "Default")
      (node (ref "LED102") (pin "A") (pinfunction "A_A") (pintype "passive"))
      (node (ref "R106") (pin "1") (pinfunction "1_1") (pintype "passive"))
    )
    (net (code "117") (name "Net-(LED103-PadA)") (class "Default")
      (node (ref "LED103") (pin "A") (pinfunction "A_A") (pintype "passive"))
      (node (ref "R107") (pin "1") (pinfunction "1_1") (pintype "passive"))
    )
    (net (code "118") (name "Net-(LED104-PadA)") (class "Default")
      (node (ref "LED104") (pin "A") (pinfunction "A_A") (pintype "passive"))
      (node (ref "R108") (pin "1") (pinfunction "1_1") (pintype "passive"))
    )
    (net (code "119") (name "Net-(LED105-PadA)") (class "Default")
      (node (ref "LED105") (pin "A") (pinfunction "A_A") (pintype "passive"))
      (node (ref "R109") (pin "1") (pinfunction "1_1") (pintype "passive"))
    )
    (net (code "120") (name "Net-(LED106-PadA)") (class "Default")
      (node (ref "LED106") (pin "A") (pinfunction "A_A") (pintype "passive"))
      (node (ref "R110") (pin "1") (pinfunction "1_1") (pintype "passive"))
    )
    (net (code "121") (name "Net-(LED107-PadA)") (class "Default")
      (node (ref "LED107") (pin "A") (pinfunction "A_A") (pintype "passive"))
      (node (ref "R111") (pin "1") (pinfunction "1_1") (pintype "passive"))
    )
    (net (code "122") (name "Net-(LED108-PadA)") (class "Default")
      (node (ref "LED108") (pin "A") (pinfunction "A_A") (pintype "passive"))
      (node (ref "R112") (pin "1") (pinfunction "1_1") (pintype "passive"))
    )
    (net (code "123") (name "Net-(LED109-PadA)") (class "Default")
      (node (ref "LED109") (pin "A") (pinfunction "A_A") (pintype "passive"))
      (node (ref "R113") (pin "1") (pinfunction "1_1") (pintype "passive"))
    )
    (net (code "124") (name "Net-(LED110-PadA)") (class "Default")
      (node (ref "LED110") (pin "A") (pinfunction "A_A") (pintype "passive"))
      (node (ref "R114") (pin "1") (pinfunction "1_1") (pintype "passive"))
    )
    (net (code "125") (name "Net-(LED111-PadA)") (class "Default")
      (node (ref "LED111") (pin "A") (pinfunction "A_A") (pintype "passive"))
      (node (ref "R115") (pin "1") (pinfunction "1_1") (pintype "passive"))
    )
    (net (code "126") (name "Net-(LED112-PadA)") (class "Default")
      (node (ref "LED112") (pin "A") (pinfunction "A_A") (pintype "passive"))
      (node (ref "R116") (pin "1") (pinfunction "1_1") (pintype "passive"))
    )
    (net (code "127") (name "Net-(LED113-PadA)") (class "Default")
      (node (ref "LED113") (pin "A") (pinfunction "A_A") (pintype "passive"))
      (node (ref "R117") (pin "1") (pinfunction "1_1") (pintype "passive"))
    )
    (net (code "128") (name "Net-(LED114-PadA)") (class "Default")
      (node (ref "LED114") (pin "A") (pinfunction "A_A") (pintype "passive"))
      (node (ref "R118") (pin "1") (pinfunction "1_1") (pintype "passive"))
    )
    (net (code "129") (name "Net-(LED115-PadA)") (class "Default")
      (node (ref "LED115") (pin "A") (pinfunction "A_A") (pintype "passive"))
      (node (ref "R119") (pin "1") (pinfunction "1_1") (pintype "passive"))
    )
    (net (code "130") (name "Net-(LED116-PadA)") (class "Default")
      (node (ref "LED116") (pin "A") (pinfunction "A_A") (pintype "passive"))
      (node (ref "R120") (pin "1") (pinfunction "1_1") (pintype "passive"))
    )
    (net (code "131") (name "Net-(LED133-PadA)") (class "Default")
      (node (ref "LED133") (pin "A") (pinfunction "A_A") (pintype "passive"))
      (node (ref "R137") (pin "1") (pinfunction "1_1") (pintype "passive"))
    )
    (net (code "132") (name "Net-(LED134-PadA)") (class "Default")
      (node (ref "LED134") (pin "A") (pinfunction "A_A") (pintype "passive"))
      (node (ref "R138") (pin "1") (pinfunction "1_1") (pintype "passive"))
    )
    (net (code "133") (name "Net-(LED135-PadA)") (class "Default")
      (node (ref "LED135") (pin "A") (pinfunction "A_A") (pintype "passive"))
      (node (ref "R139") (pin "1") (pinfunction "1_1") (pintype "passive"))
    )
    (net (code "134") (name "Net-(LED136-PadA)") (class "Default")
      (node (ref "LED136") (pin "A") (pinfunction "A_A") (pintype "passive"))
      (node (ref "R140") (pin "1") (pinfunction "1_1") (pintype "passive"))
    )
    (net (code "135") (name "Net-(LED137-PadA)") (class "Default")
      (node (ref "LED137") (pin "A") (pinfunction "A_A") (pintype "passive"))
      (node (ref "R141") (pin "1") (pinfunction "1_1") (pintype "passive"))
    )
    (net (code "136") (name "Net-(LED138-PadA)") (class "Default")
      (node (ref "LED138") (pin "A") (pinfunction "A_A") (pintype "passive"))
      (node (ref "R142") (pin "1") (pinfunction "1_1") (pintype "passive"))
    )
    (net (code "137") (name "Net-(LED139-PadA)") (class "Default")
      (node (ref "LED139") (pin "A") (pinfunction "A_A") (pintype "passive"))
      (node (ref "R143") (pin "1") (pinfunction "1_1") (pintype "passive"))
    )
    (net (code "138") (name "Net-(LED140-PadA)") (class "Default")
      (node (ref "LED140") (pin "A") (pinfunction "A_A") (pintype "passive"))
      (node (ref "R144") (pin "1") (pinfunction "1_1") (pintype "passive"))
    )
    (net (code "139") (name "Net-(LED141-PadA)") (class "Default")
      (node (ref "LED141") (pin "A") (pinfunction "A_A") (pintype "passive"))
      (node (ref "R145") (pin "1") (pinfunction "1_1") (pintype "passive"))
    )
    (net (code "140") (name "Net-(LED142-PadA)") (class "Default")
      (node (ref "LED142") (pin "A") (pinfunction "A_A") (pintype "passive"))
      (node (ref "R146") (pin "1") (pinfunction "1_1") (pintype "passive"))
    )
    (net (code "141") (name "Net-(LED143-PadA)") (class "Default")
      (node (ref "LED143") (pin "A") (pinfunction "A_A") (pintype "passive"))
      (node (ref "R147") (pin "1") (pinfunction "1_1") (pintype "passive"))
    )
    (net (code "142") (name "Net-(LED144-PadA)") (class "Default")
      (node (ref "LED144") (pin "A") (pinfunction "A_A") (pintype "passive"))
      (node (ref "R148") (pin "1") (pinfunction "1_1") (pintype "passive"))
    )
    (net (code "143") (name "Net-(LED145-PadA)") (class "Default")
      (node (ref "LED145") (pin "A") (pinfunction "A_A") (pintype "passive"))
      (node (ref "R149") (pin "1") (pinfunction "1_1") (pintype "passive"))
    )
    (net (code "144") (name "Net-(LED146-PadA)") (class "Default")
      (node (ref "LED146") (pin "A") (pinfunction "A_A") (pintype "passive"))
      (node (ref "R150") (pin "1") (pinfunction "1_1") (pintype "passive"))
    )
    (net (code "145") (name "Net-(LED147-PadA)") (class "Default")
      (node (ref "LED147") (pin "A") (pinfunction "A_A") (pintype "passive"))
      (node (ref "R151") (pin "1") (pinfunction "1_1") (pintype "passive"))
    )
    (net (code "146") (name "Net-(LED148-PadA)") (class "Default")
      (node (ref "LED148") (pin "A") (pinfunction "A_A") (pintype "passive"))
      (node (ref "R152") (pin "1") (pinfunction "1_1") (pintype "passive"))
    )
    (net (code "147") (name "Net-(LED149-PadA)") (class "Default")
      (node (ref "LED149") (pin "A") (pinfunction "A_A") (pintype "passive"))
      (node (ref "R153") (pin "1") (pinfunction "1_1") (pintype "passive"))
    )
    (net (code "148") (name "Net-(LED150-PadA)") (class "Default")
      (node (ref "LED150") (pin "A") (pinfunction "A_A") (pintype "passive"))
      (node (ref "R154") (pin "1") (pinfunction "1_1") (pintype "passive"))
    )
    (net (code "149") (name "Net-(LED151-PadA)") (class "Default")
      (node (ref "LED151") (pin "A") (pinfunction "A_A") (pintype "passive"))
      (node (ref "R155") (pin "1") (pinfunction "1_1") (pintype "passive"))
    )
    (net (code "150") (name "Net-(LED152-PadA)") (class "Default")
      (node (ref "LED152") (pin "A") (pinfunction "A_A") (pintype "passive"))
      (node (ref "R156") (pin "1") (pinfunction "1_1") (pintype "passive"))
    )
    (net (code "151") (name "Net-(LED153-PadA)") (class "Default")
      (node (ref "LED153") (pin "A") (pinfunction "A_A") (pintype "passive"))
      (node (ref "R157") (pin "1") (pinfunction "1_1") (pintype "passive"))
    )
    (net (code "152") (name "Net-(LED154-PadA)") (class "Default")
      (node (ref "LED154") (pin "A") (pinfunction "A_A") (pintype "passive"))
      (node (ref "R158") (pin "1") (pinfunction "1_1") (pintype "passive"))
    )
    (net (code "153") (name "Net-(LED155-PadA)") (class "Default")
      (node (ref "LED155") (pin "A") (pinfunction "A_A") (pintype "passive"))
      (node (ref "R159") (pin "1") (pinfunction "1_1") (pintype "passive"))
    )
    (net (code "154") (name "Net-(LED156-PadA)") (class "Default")
      (node (ref "LED156") (pin "A") (pinfunction "A_A") (pintype "passive"))
      (node (ref "R160") (pin "1") (pinfunction "1_1") (pintype "passive"))
    )
    (net (code "155") (name "Net-(LED157-PadA)") (class "Default")
      (node (ref "LED157") (pin "A") (pinfunction "A_A") (pintype "passive"))
      (node (ref "R161") (pin "1") (pinfunction "1_1") (pintype "passive"))
    )
    (net (code "156") (name "Net-(LED158-PadA)") (class "Default")
      (node (ref "LED158") (pin "A") (pinfunction "A_A") (pintype "passive"))
      (node (ref "R162") (pin "1") (pinfunction "1_1") (pintype "passive"))
    )
    (net (code "157") (name "Net-(LED159-PadA)") (class "Default")
      (node (ref "LED159") (pin "A") (pinfunction "A_A") (pintype "passive"))
      (node (ref "R163") (pin "1") (pinfunction "1_1") (pintype "passive"))
    )
    (net (code "158") (name "Net-(LED160-PadA)") (class "Default")
      (node (ref "LED160") (pin "A") (pinfunction "A_A") (pintype "passive"))
      (node (ref "R164") (pin "1") (pinfunction "1_1") (pintype "passive"))
    )
    (net (code "159") (name "Net-(LED161-PadA)") (class "Default")
      (node (ref "LED161") (pin "A") (pinfunction "A_A") (pintype "passive"))
      (node (ref "R165") (pin "1") (pinfunction "1_1") (pintype "passive"))
    )
    (net (code "160") (name "Net-(LED162-PadA)") (class "Default")
      (node (ref "LED162") (pin "A") (pinfunction "A_A") (pintype "passive"))
      (node (ref "R166") (pin "1") (pinfunction "1_1") (pintype "passive"))
    )
    (net (code "161") (name "Net-(LED163-PadA)") (class "Default")
      (node (ref "LED163") (pin "A") (pinfunction "A_A") (pintype "passive"))
      (node (ref "R167") (pin "1") (pinfunction "1_1") (pintype "passive"))
    )
    (net (code "162") (name "Net-(LED164-PadA)") (class "Default")
      (node (ref "LED164") (pin "A") (pinfunction "A_A") (pintype "passive"))
      (node (ref "R168") (pin "1") (pinfunction "1_1") (pintype "passive"))
    )
    (net (code "163") (name "Net-(Q1-G)") (class "Default")
      (node (ref "ENCODER") (pin "2") (pinfunction "2_2") (pintype "passive"))
      (node (ref "JP2") (pin "2") (pinfunction "2_2") (pintype "passive"))
      (node (ref "Q1") (pin "1") (pinfunction "G_1") (pintype "passive"))
    )
    (net (code "164") (name "Net-(Q1-S)") (class "Default")
      (node (ref "Q1") (pin "2") (pinfunction "S_2") (pintype "passive"))
      (node (ref "R3") (pin "2") (pinfunction "2_2") (pintype "passive"))
    )
    (net (code "165") (name "Net-(Q2-G)") (class "Default")
      (node (ref "ENCODER") (pin "1") (pinfunction "1_1") (pintype "passive"))
      (node (ref "JP3") (pin "2") (pinfunction "2_2") (pintype "passive"))
      (node (ref "Q2") (pin "1") (pinfunction "G_1") (pintype "passive"))
    )
    (net (code "166") (name "Net-(Q2-S)") (class "Default")
      (node (ref "Q2") (pin "2") (pinfunction "S_2") (pintype "passive"))
      (node (ref "R4") (pin "2") (pinfunction "2_2") (pintype "passive"))
    )
    (net (code "167") (name "Net-(R2-Pad2)") (class "Default")
      (node (ref "R2") (pin "2") (pinfunction "2_2") (pintype "passive"))
      (node (ref "SENSOR") (pin "1") (pinfunction "1_1") (pintype "passive"))
    )
    (net (code "168") (name "Net-(R7-Pad2)") (class "Default")
      (node (ref "R7") (pin "2") (pinfunction "2_2") (pintype "passive"))
      (node (ref "SENSOR1") (pin "1") (pinfunction "1_1") (pintype "passive"))
    )
    (net (code "169") (name "Net-(R8-Pad2)") (class "Default")
      (node (ref "R8") (pin "2") (pinfunction "2_2") (pintype "passive"))
      (node (ref "SV1") (pin "2") (pinfunction "2_2") (pintype "passive"))
    )
    (net (code "170") (name "Net-(R9-Pad2)") (class "Default")
      (node (ref "R9") (pin "2") (pinfunction "2_2") (pintype "passive"))
      (node (ref "SV1") (pin "4") (pinfunction "4_4") (pintype "passive"))
    )
    (net (code "171") (name "Net-(R10-Pad2)") (class "Default")
      (node (ref "R10") (pin "2") (pinfunction "2_2") (pintype "passive"))
      (node (ref "SV1") (pin "6") (pinfunction "6_6") (pintype "passive"))
    )
    (net (code "172") (name "Net-(R11-Pad2)") (class "Default")
      (node (ref "R11") (pin "2") (pinfunction "2_2") (pintype "passive"))
      (node (ref "SV1") (pin "8") (pinfunction "8_8") (pintype "passive"))
    )
    (net (code "173") (name "Net-(R12-Pad2)") (class "Default")
      (node (ref "R12") (pin "2") (pinfunction "2_2") (pintype "passive"))
      (node (ref "SV1") (pin "10") (pinfunction "10_10") (pintype "passive"))
    )
    (net (code "174") (name "Net-(R13-Pad2)") (class "Default")
      (node (ref "R13") (pin "2") (pinfunction "2_2") (pintype "passive"))
      (node (ref "SV1") (pin "12") (pinfunction "12_12") (pintype "passive"))
    )
    (net (code "175") (name "Net-(R14-Pad2)") (class "Default")
      (node (ref "R14") (pin "2") (pinfunction "2_2") (pintype "passive"))
      (node (ref "SV1") (pin "14") (pinfunction "14_14") (pintype "passive"))
    )
    (net (code "176") (name "Net-(R15-Pad2)") (class "Default")
      (node (ref "R15") (pin "2") (pinfunction "2_2") (pintype "passive"))
      (node (ref "SV1") (pin "16") (pinfunction "16_16") (pintype "passive"))
    )
    (net (code "177") (name "Net-(R16-Pad2)") (class "Default")
      (node (ref "R16") (pin "2") (pinfunction "2_2") (pintype "passive"))
      (node (ref "SV1") (pin "18") (pinfunction "18_18") (pintype "passive"))
    )
    (net (code "178") (name "Net-(R17-Pad2)") (class "Default")
      (node (ref "R17") (pin "2") (pinfunction "2_2") (pintype "passive"))
      (node (ref "SV1") (pin "20") (pinfunction "20_20") (pintype "passive"))
    )
    (net (code "179") (name "Net-(R18-Pad2)") (class "Default")
      (node (ref "R18") (pin "2") (pinfunction "2_2") (pintype "passive"))
      (node (ref "SV2") (pin "2") (pinfunction "2_2") (pintype "passive"))
    )
    (net (code "180") (name "Net-(R19-Pad2)") (class "Default")
      (node (ref "R19") (pin "2") (pinfunction "2_2") (pintype "passive"))
      (node (ref "SV2") (pin "4") (pinfunction "4_4") (pintype "passive"))
    )
    (net (code "181") (name "Net-(R20-Pad2)") (class "Default")
      (node (ref "R20") (pin "2") (pinfunction "2_2") (pintype "passive"))
      (node (ref "SV2") (pin "6") (pinfunction "6_6") (pintype "passive"))
    )
    (net (code "182") (name "Net-(R21-Pad2)") (class "Default")
      (node (ref "R21") (pin "2") (pinfunction "2_2") (pintype "passive"))
      (node (ref "SV2") (pin "8") (pinfunction "8_8") (pintype "passive"))
    )
    (net (code "183") (name "Net-(R22-Pad2)") (class "Default")
      (node (ref "R22") (pin "2") (pinfunction "2_2") (pintype "passive"))
      (node (ref "SV2") (pin "10") (pinfunction "10_10") (pintype "passive"))
    )
    (net (code "184") (name "Net-(R23-Pad2)") (class "Default")
      (node (ref "R23") (pin "2") (pinfunction "2_2") (pintype "passive"))
      (node (ref "SV2") (pin "12") (pinfunction "12_12") (pintype "passive"))
    )
    (net (code "185") (name "Net-(R24-Pad2)") (class "Default")
      (node (ref "R24") (pin "2") (pinfunction "2_2") (pintype "passive"))
      (node (ref "SV2") (pin "11") (pinfunction "11_11") (pintype "passive"))
    )
    (net (code "186") (name "Net-(R25-Pad2)") (class "Default")
      (node (ref "R25") (pin "2") (pinfunction "2_2") (pintype "passive"))
      (node (ref "SV2") (pin "9") (pinfunction "9_9") (pintype "passive"))
    )
    (net (code "187") (name "Net-(R26-Pad2)") (class "Default")
      (node (ref "R26") (pin "2") (pinfunction "2_2") (pintype "passive"))
      (node (ref "SV2") (pin "7") (pinfunction "7_7") (pintype "passive"))
    )
    (net (code "188") (name "Net-(R28-Pad2)") (class "Default")
      (node (ref "R28") (pin "2") (pinfunction "2_2") (pintype "passive"))
      (node (ref "SV2") (pin "5") (pinfunction "5_5") (pintype "passive"))
    )
    (net (code "189") (name "Net-(R29-Pad2)") (class "Default")
      (node (ref "R29") (pin "2") (pinfunction "2_2") (pintype "passive"))
      (node (ref "SV2") (pin "3") (pinfunction "3_3") (pintype "passive"))
    )
    (net (code "190") (name "Net-(R30-Pad2)") (class "Default")
      (node (ref "R30") (pin "2") (pinfunction "2_2") (pintype "passive"))
      (node (ref "SV2") (pin "1") (pinfunction "1_1") (pintype "passive"))
    )
    (net (code "191") (name "Net-(R31-Pad2)") (class "Default")
      (node (ref "R31") (pin "2") (pinfunction "2_2") (pintype "passive"))
      (node (ref "SV1") (pin "19") (pinfunction "19_19") (pintype "passive"))
    )
    (net (code "192") (name "Net-(R32-Pad2)") (class "Default")
      (node (ref "R32") (pin "2") (pinfunction "2_2") (pintype "passive"))
      (node (ref "SV1") (pin "17") (pinfunction "17_17") (pintype "passive"))
    )
    (net (code "193") (name "Net-(R33-Pad2)") (class "Default")
      (node (ref "R33") (pin "2") (pinfunction "2_2") (pintype "passive"))
      (node (ref "SV1") (pin "15") (pinfunction "15_15") (pintype "passive"))
    )
    (net (code "194") (name "Net-(R34-Pad2)") (class "Default")
      (node (ref "R34") (pin "2") (pinfunction "2_2") (pintype "passive"))
      (node (ref "SV1") (pin "13") (pinfunction "13_13") (pintype "passive"))
    )
    (net (code "195") (name "Net-(R35-Pad2)") (class "Default")
      (node (ref "R35") (pin "2") (pinfunction "2_2") (pintype "passive"))
      (node (ref "SV1") (pin "11") (pinfunction "11_11") (pintype "passive"))
    )
    (net (code "196") (name "Net-(R36-Pad2)") (class "Default")
      (node (ref "R36") (pin "2") (pinfunction "2_2") (pintype "passive"))
      (node (ref "SV1") (pin "9") (pinfunction "9_9") (pintype "passive"))
    )
    (net (code "197") (name "Net-(R37-Pad2)") (class "Default")
      (node (ref "R37") (pin "2") (pinfunction "2_2") (pintype "passive"))
      (node (ref "SV1") (pin "7") (pinfunction "7_7") (pintype "passive"))
    )
    (net (code "198") (name "Net-(R38-Pad2)") (class "Default")
      (node (ref "R38") (pin "2") (pinfunction "2_2") (pintype "passive"))
      (node (ref "SV1") (pin "5") (pinfunction "5_5") (pintype "passive"))
    )
    (net (code "199") (name "Net-(R39-Pad2)") (class "Default")
      (node (ref "R39") (pin "2") (pinfunction "2_2") (pintype "passive"))
      (node (ref "SV1") (pin "3") (pinfunction "3_3") (pintype "passive"))
    )
    (net (code "200") (name "Net-(R40-Pad2)") (class "Default")
      (node (ref "R40") (pin "2") (pinfunction "2_2") (pintype "passive"))
      (node (ref "SV1") (pin "1") (pinfunction "1_1") (pintype "passive"))
    )
    (net (code "201") (name "Net-(R41-Pad2)") (class "Default")
      (node (ref "R41") (pin "2") (pinfunction "2_2") (pintype "passive"))
      (node (ref "SV3") (pin "2") (pinfunction "2_2") (pintype "passive"))
    )
    (net (code "202") (name "Net-(R42-Pad2)") (class "Default")
      (node (ref "R42") (pin "2") (pinfunction "2_2") (pintype "passive"))
      (node (ref "SV3") (pin "4") (pinfunction "4_4") (pintype "passive"))
    )
    (net (code "203") (name "Net-(R43-Pad2)") (class "Default")
      (node (ref "R43") (pin "2") (pinfunction "2_2") (pintype "passive"))
      (node (ref "SV3") (pin "6") (pinfunction "6_6") (pintype "passive"))
    )
    (net (code "204") (name "Net-(R44-Pad2)") (class "Default")
      (node (ref "R44") (pin "2") (pinfunction "2_2") (pintype "passive"))
      (node (ref "SV3") (pin "8") (pinfunction "8_8") (pintype "passive"))
    )
    (net (code "205") (name "Net-(R45-Pad2)") (class "Default")
      (node (ref "R45") (pin "2") (pinfunction "2_2") (pintype "passive"))
      (node (ref "SV3") (pin "10") (pinfunction "10_10") (pintype "passive"))
    )
    (net (code "206") (name "Net-(R46-Pad2)") (class "Default")
      (node (ref "R46") (pin "2") (pinfunction "2_2") (pintype "passive"))
      (node (ref "SV3") (pin "12") (pinfunction "12_12") (pintype "passive"))
    )
    (net (code "207") (name "Net-(R47-Pad2)") (class "Default")
      (node (ref "R47") (pin "2") (pinfunction "2_2") (pintype "passive"))
      (node (ref "SV3") (pin "14") (pinfunction "14_14") (pintype "passive"))
    )
    (net (code "208") (name "Net-(R48-Pad2)") (class "Default")
      (node (ref "R48") (pin "2") (pinfunction "2_2") (pintype "passive"))
      (node (ref "SV3") (pin "16") (pinfunction "16_16") (pintype "passive"))
    )
    (net (code "209") (name "Net-(R49-Pad2)") (class "Default")
      (node (ref "R49") (pin "2") (pinfunction "2_2") (pintype "passive"))
      (node (ref "SV3") (pin "18") (pinfunction "18_18") (pintype "passive"))
    )
    (net (code "210") (name "Net-(R50-Pad2)") (class "Default")
      (node (ref "R50") (pin "2") (pinfunction "2_2") (pintype "passive"))
      (node (ref "SV3") (pin "20") (pinfunction "20_20") (pintype "passive"))
    )
    (net (code "211") (name "Net-(R51-Pad2)") (class "Default")
      (node (ref "R51") (pin "2") (pinfunction "2_2") (pintype "passive"))
      (node (ref "SV4") (pin "2") (pinfunction "2_2") (pintype "passive"))
    )
    (net (code "212") (name "Net-(R52-Pad2)") (class "Default")
      (node (ref "R52") (pin "2") (pinfunction "2_2") (pintype "passive"))
      (node (ref "SV4") (pin "4") (pinfunction "4_4") (pintype "passive"))
    )
    (net (code "213") (name "Net-(R53-Pad2)") (class "Default")
      (node (ref "R53") (pin "2") (pinfunction "2_2") (pintype "passive"))
      (node (ref "SV4") (pin "6") (pinfunction "6_6") (pintype "passive"))
    )
    (net (code "214") (name "Net-(R54-Pad2)") (class "Default")
      (node (ref "R54") (pin "2") (pinfunction "2_2") (pintype "passive"))
      (node (ref "SV4") (pin "8") (pinfunction "8_8") (pintype "passive"))
    )
    (net (code "215") (name "Net-(R55-Pad2)") (class "Default")
      (node (ref "R55") (pin "2") (pinfunction "2_2") (pintype "passive"))
      (node (ref "SV4") (pin "10") (pinfunction "10_10") (pintype "passive"))
    )
    (net (code "216") (name "Net-(R56-Pad2)") (class "Default")
      (node (ref "R56") (pin "2") (pinfunction "2_2") (pintype "passive"))
      (node (ref "SV4") (pin "12") (pinfunction "12_12") (pintype "passive"))
    )
    (net (code "217") (name "Net-(R57-Pad2)") (class "Default")
      (node (ref "R57") (pin "2") (pinfunction "2_2") (pintype "passive"))
      (node (ref "SV4") (pin "11") (pinfunction "11_11") (pintype "passive"))
    )
    (net (code "218") (name "Net-(R58-Pad2)") (class "Default")
      (node (ref "R58") (pin "2") (pinfunction "2_2") (pintype "passive"))
      (node (ref "SV4") (pin "9") (pinfunction "9_9") (pintype "passive"))
    )
    (net (code "219") (name "Net-(R59-Pad2)") (class "Default")
      (node (ref "R59") (pin "2") (pinfunction "2_2") (pintype "passive"))
      (node (ref "SV4") (pin "7") (pinfunction "7_7") (pintype "passive"))
    )
    (net (code "220") (name "Net-(R60-Pad2)") (class "Default")
      (node (ref "R60") (pin "2") (pinfunction "2_2") (pintype "passive"))
      (node (ref "SV4") (pin "5") (pinfunction "5_5") (pintype "passive"))
    )
    (net (code "221") (name "Net-(R61-Pad2)") (class "Default")
      (node (ref "R61") (pin "2") (pinfunction "2_2") (pintype "passive"))
      (node (ref "SV4") (pin "3") (pinfunction "3_3") (pintype "passive"))
    )
    (net (code "222") (name "Net-(R62-Pad2)") (class "Default")
      (node (ref "R62") (pin "2") (pinfunction "2_2") (pintype "passive"))
      (node (ref "SV4") (pin "1") (pinfunction "1_1") (pintype "passive"))
    )
    (net (code "223") (name "Net-(R63-Pad2)") (class "Default")
      (node (ref "R63") (pin "2") (pinfunction "2_2") (pintype "passive"))
      (node (ref "SV3") (pin "19") (pinfunction "19_19") (pintype "passive"))
    )
    (net (code "224") (name "Net-(R64-Pad2)") (class "Default")
      (node (ref "R64") (pin "2") (pinfunction "2_2") (pintype "passive"))
      (node (ref "SV3") (pin "17") (pinfunction "17_17") (pintype "passive"))
    )
    (net (code "225") (name "Net-(R65-Pad2)") (class "Default")
      (node (ref "R65") (pin "2") (pinfunction "2_2") (pintype "passive"))
      (node (ref "SV3") (pin "15") (pinfunction "15_15") (pintype "passive"))
    )
    (net (code "226") (name "Net-(R66-Pad2)") (class "Default")
      (node (ref "R66") (pin "2") (pinfunction "2_2") (pintype "passive"))
      (node (ref "SV3") (pin "13") (pinfunction "13_13") (pintype "passive"))
    )
    (net (code "227") (name "Net-(R67-Pad2)") (class "Default")
      (node (ref "R67") (pin "2") (pinfunction "2_2") (pintype "passive"))
      (node (ref "SV3") (pin "11") (pinfunction "11_11") (pintype "passive"))
    )
    (net (code "228") (name "Net-(R68-Pad2)") (class "Default")
      (node (ref "R68") (pin "2") (pinfunction "2_2") (pintype "passive"))
      (node (ref "SV3") (pin "9") (pinfunction "9_9") (pintype "passive"))
    )
    (net (code "229") (name "Net-(R69-Pad2)") (class "Default")
      (node (ref "R69") (pin "2") (pinfunction "2_2") (pintype "passive"))
      (node (ref "SV3") (pin "7") (pinfunction "7_7") (pintype "passive"))
    )
    (net (code "230") (name "Net-(R70-Pad2)") (class "Default")
      (node (ref "R70") (pin "2") (pinfunction "2_2") (pintype "passive"))
      (node (ref "SV3") (pin "5") (pinfunction "5_5") (pintype "passive"))
    )
    (net (code "231") (name "Net-(R71-Pad2)") (class "Default")
      (node (ref "R71") (pin "2") (pinfunction "2_2") (pintype "passive"))
      (node (ref "SV3") (pin "3") (pinfunction "3_3") (pintype "passive"))
    )
    (net (code "232") (name "Net-(R72-Pad2)") (class "Default")
      (node (ref "R72") (pin "2") (pinfunction "2_2") (pintype "passive"))
      (node (ref "SV3") (pin "1") (pinfunction "1_1") (pintype "passive"))
    )
    (net (code "233") (name "Net-(R73-Pad2)") (class "Default")
      (node (ref "R73") (pin "2") (pinfunction "2_2") (pintype "passive"))
      (node (ref "U$1") (pin "1") (pinfunction "1_1") (pintype "passive"))
    )
    (net (code "234") (name "Net-(R74-Pad2)") (class "Default")
      (node (ref "R74") (pin "2") (pinfunction "2_2") (pintype "passive"))
      (node (ref "U$1") (pin "4") (pinfunction "4_4") (pintype "passive"))
    )
    (net (code "235") (name "Net-(R75-Pad2)") (class "Default")
      (node (ref "R75") (pin "2") (pinfunction "2_2") (pintype "passive"))
      (node (ref "U$1") (pin "7") (pinfunction "7_7") (pintype "passive"))
    )
    (net (code "236") (name "Net-(R76-Pad2)") (class "Default")
      (node (ref "R76") (pin "2") (pinfunction "2_2") (pintype "passive"))
      (node (ref "U$1") (pin "10") (pinfunction "10_10") (pintype "passive"))
    )
    (net (code "237") (name "Net-(R77-Pad2)") (class "Default")
      (node (ref "R77") (pin "2") (pinfunction "2_2") (pintype "passive"))
      (node (ref "U$1") (pin "13") (pinfunction "13_13") (pintype "passive"))
    )
    (net (code "238") (name "Net-(R78-Pad2)") (class "Default")
      (node (ref "R78") (pin "2") (pinfunction "2_2") (pintype "passive"))
      (node (ref "U$1") (pin "16") (pinfunction "16_16") (pintype "passive"))
    )
    (net (code "239") (name "Net-(R79-Pad2)") (class "Default")
      (node (ref "R79") (pin "2") (pinfunction "2_2") (pintype "passive"))
      (node (ref "U$1") (pin "19") (pinfunction "19_19") (pintype "passive"))
    )
    (net (code "240") (name "Net-(R80-Pad2)") (class "Default")
      (node (ref "R80") (pin "2") (pinfunction "2_2") (pintype "passive"))
      (node (ref "U$1") (pin "22") (pinfunction "22_22") (pintype "passive"))
    )
    (net (code "241") (name "Net-(R81-Pad2)") (class "Default")
      (node (ref "R81") (pin "2") (pinfunction "2_2") (pintype "passive"))
      (node (ref "U$1") (pin "25") (pinfunction "25_25") (pintype "passive"))
    )
    (net (code "242") (name "Net-(R82-Pad2)") (class "Default")
      (node (ref "R82") (pin "2") (pinfunction "2_2") (pintype "passive"))
      (node (ref "U$1") (pin "28") (pinfunction "28_28") (pintype "passive"))
    )
    (net (code "243") (name "Net-(R83-Pad2)") (class "Default")
      (node (ref "R83") (pin "2") (pinfunction "2_2") (pintype "passive"))
      (node (ref "U$1") (pin "31") (pinfunction "31_31") (pintype "passive"))
    )
    (net (code "244") (name "Net-(R84-Pad2)") (class "Default")
      (node (ref "R84") (pin "2") (pinfunction "2_2") (pintype "passive"))
      (node (ref "U$1") (pin "34") (pinfunction "34_34") (pintype "passive"))
    )
    (net (code "245") (name "Net-(R85-Pad2)") (class "Default")
      (node (ref "R85") (pin "2") (pinfunction "2_2") (pintype "passive"))
      (node (ref "U$1") (pin "37") (pinfunction "37_37") (pintype "passive"))
    )
    (net (code "246") (name "Net-(R86-Pad2)") (class "Default")
      (node (ref "R86") (pin "2") (pinfunction "2_2") (pintype "passive"))
      (node (ref "U$1") (pin "40") (pinfunction "40_40") (pintype "passive"))
    )
    (net (code "247") (name "Net-(R87-Pad2)") (class "Default")
      (node (ref "R87") (pin "2") (pinfunction "2_2") (pintype "passive"))
      (node (ref "U$1") (pin "43") (pinfunction "43_43") (pintype "passive"))
    )
    (net (code "248") (name "Net-(R88-Pad2)") (class "Default")
      (node (ref "R88") (pin "2") (pinfunction "2_2") (pintype "passive"))
      (node (ref "U$1") (pin "46") (pinfunction "46_46") (pintype "passive"))
    )
    (net (code "249") (name "Net-(R89-Pad2)") (class "Default")
      (node (ref "R89") (pin "2") (pinfunction "2_2") (pintype "passive"))
      (node (ref "U$1") (pin "2") (pinfunction "2_2") (pintype "passive"))
    )
    (net (code "250") (name "Net-(R90-Pad2)") (class "Default")
      (node (ref "R90") (pin "2") (pinfunction "2_2") (pintype "passive"))
      (node (ref "U$1") (pin "5") (pinfunction "5_5") (pintype "passive"))
    )
    (net (code "251") (name "Net-(R91-Pad2)") (class "Default")
      (node (ref "R91") (pin "2") (pinfunction "2_2") (pintype "passive"))
      (node (ref "U$1") (pin "8") (pinfunction "8_8") (pintype "passive"))
    )
    (net (code "252") (name "Net-(R92-Pad2)") (class "Default")
      (node (ref "R92") (pin "2") (pinfunction "2_2") (pintype "passive"))
      (node (ref "U$1") (pin "11") (pinfunction "11_11") (pintype "passive"))
    )
    (net (code "253") (name "Net-(R93-Pad2)") (class "Default")
      (node (ref "R93") (pin "2") (pinfunction "2_2") (pintype "passive"))
      (node (ref "U$1") (pin "14") (pinfunction "14_14") (pintype "passive"))
    )
    (net (code "254") (name "Net-(R94-Pad2)") (class "Default")
      (node (ref "R94") (pin "2") (pinfunction "2_2") (pintype "passive"))
      (node (ref "U$1") (pin "17") (pinfunction "17_17") (pintype "passive"))
    )
    (net (code "255") (name "Net-(R95-Pad2)") (class "Default")
      (node (ref "R95") (pin "2") (pinfunction "2_2") (pintype "passive"))
      (node (ref "U$1") (pin "20") (pinfunction "20_20") (pintype "passive"))
    )
    (net (code "256") (name "Net-(R96-Pad2)") (class "Default")
      (node (ref "R96") (pin "2") (pinfunction "2_2") (pintype "passive"))
      (node (ref "U$1") (pin "23") (pinfunction "23_23") (pintype "passive"))
    )
    (net (code "257") (name "Net-(R97-Pad2)") (class "Default")
      (node (ref "R97") (pin "2") (pinfunction "2_2") (pintype "passive"))
      (node (ref "U$1") (pin "26") (pinfunction "26_26") (pintype "passive"))
    )
    (net (code "258") (name "Net-(R98-Pad2)") (class "Default")
      (node (ref "R98") (pin "2") (pinfunction "2_2") (pintype "passive"))
      (node (ref "U$1") (pin "29") (pinfunction "29_29") (pintype "passive"))
    )
    (net (code "259") (name "Net-(R99-Pad2)") (class "Default")
      (node (ref "R99") (pin "2") (pinfunction "2_2") (pintype "passive"))
      (node (ref "U$1") (pin "32") (pinfunction "32_32") (pintype "passive"))
    )
    (net (code "260") (name "Net-(R100-Pad2)") (class "Default")
      (node (ref "R100") (pin "2") (pinfunction "2_2") (pintype "passive"))
      (node (ref "U$1") (pin "35") (pinfunction "35_35") (pintype "passive"))
    )
    (net (code "261") (name "Net-(R101-Pad2)") (class "Default")
      (node (ref "R101") (pin "2") (pinfunction "2_2") (pintype "passive"))
      (node (ref "U$1") (pin "38") (pinfunction "38_38") (pintype "passive"))
    )
    (net (code "262") (name "Net-(R102-Pad2)") (class "Default")
      (node (ref "R102") (pin "2") (pinfunction "2_2") (pintype "passive"))
      (node (ref "U$1") (pin "41") (pinfunction "41_41") (pintype "passive"))
    )
    (net (code "263") (name "Net-(R103-Pad2)") (class "Default")
      (node (ref "R103") (pin "2") (pinfunction "2_2") (pintype "passive"))
      (node (ref "U$1") (pin "44") (pinfunction "44_44") (pintype "passive"))
    )
    (net (code "264") (name "Net-(R104-Pad2)") (class "Default")
      (node (ref "R104") (pin "2") (pinfunction "2_2") (pintype "passive"))
      (node (ref "U$1") (pin "47") (pinfunction "47_47") (pintype "passive"))
    )
    (net (code "265") (name "Net-(R105-Pad2)") (class "Default")
      (node (ref "R105") (pin "2") (pinfunction "2_2") (pintype "passive"))
      (node (ref "U$1") (pin "3") (pinfunction "3_3") (pintype "passive"))
    )
    (net (code "266") (name "Net-(R106-Pad2)") (class "Default")
      (node (ref "R106") (pin "2") (pinfunction "2_2") (pintype "passive"))
      (node (ref "U$1") (pin "6") (pinfunction "6_6") (pintype "passive"))
    )
    (net (code "267") (name "Net-(R107-Pad2)") (class "Default")
      (node (ref "R107") (pin "2") (pinfunction "2_2") (pintype "passive"))
      (node (ref "U$1") (pin "9") (pinfunction "9_9") (pintype "passive"))
    )
    (net (code "268") (name "Net-(R108-Pad2)") (class "Default")
      (node (ref "R108") (pin "2") (pinfunction "2_2") (pintype "passive"))
      (node (ref "U$1") (pin "12") (pinfunction "12_12") (pintype "passive"))
    )
    (net (code "269") (name "Net-(R109-Pad2)") (class "Default")
      (node (ref "R109") (pin "2") (pinfunction "2_2") (pintype "passive"))
      (node (ref "U$1") (pin "15") (pinfunction "15_15") (pintype "passive"))
    )
    (net (code "270") (name "Net-(R110-Pad2)") (class "Default")
      (node (ref "R110") (pin "2") (pinfunction "2_2") (pintype "passive"))
      (node (ref "U$1") (pin "18") (pinfunction "18_18") (pintype "passive"))
    )
    (net (code "271") (name "Net-(R111-Pad2)") (class "Default")
      (node (ref "R111") (pin "2") (pinfunction "2_2") (pintype "passive"))
      (node (ref "U$1") (pin "21") (pinfunction "21_21") (pintype "passive"))
    )
    (net (code "272") (name "Net-(R112-Pad2)") (class "Default")
      (node (ref "R112") (pin "2") (pinfunction "2_2") (pintype "passive"))
      (node (ref "U$1") (pin "24") (pinfunction "24_24") (pintype "passive"))
    )
    (net (code "273") (name "Net-(R113-Pad2)") (class "Default")
      (node (ref "R113") (pin "2") (pinfunction "2_2") (pintype "passive"))
      (node (ref "U$1") (pin "27") (pinfunction "27_27") (pintype "passive"))
    )
    (net (code "274") (name "Net-(R114-Pad2)") (class "Default")
      (node (ref "R114") (pin "2") (pinfunction "2_2") (pintype "passive"))
      (node (ref "U$1") (pin "30") (pinfunction "30_30") (pintype "passive"))
    )
    (net (code "275") (name "Net-(R115-Pad2)") (class "Default")
      (node (ref "R115") (pin "2") (pinfunction "2_2") (pintype "passive"))
      (node (ref "U$1") (pin "33") (pinfunction "33_33") (pintype "passive"))
    )
    (net (code "276") (name "Net-(R116-Pad2)") (class "Default")
      (node (ref "R116") (pin "2") (pinfunction "2_2") (pintype "passive"))
      (node (ref "U$1") (pin "36") (pinfunction "36_36") (pintype "passive"))
    )
    (net (code "277") (name "Net-(R117-Pad2)") (class "Default")
      (node (ref "R117") (pin "2") (pinfunction "2_2") (pintype "passive"))
      (node (ref "U$1") (pin "39") (pinfunction "39_39") (pintype "passive"))
    )
    (net (code "278") (name "Net-(R118-Pad2)") (class "Default")
      (node (ref "R118") (pin "2") (pinfunction "2_2") (pintype "passive"))
      (node (ref "U$1") (pin "42") (pinfunction "42_42") (pintype "passive"))
    )
    (net (code "279") (name "Net-(R119-Pad2)") (class "Default")
      (node (ref "R119") (pin "2") (pinfunction "2_2") (pintype "passive"))
      (node (ref "U$1") (pin "45") (pinfunction "45_45") (pintype "passive"))
    )
    (net (code "280") (name "Net-(R120-Pad2)") (class "Default")
      (node (ref "R120") (pin "2") (pinfunction "2_2") (pintype "passive"))
      (node (ref "U$1") (pin "48") (pinfunction "48_48") (pintype "passive"))
    )
    (net (code "281") (name "Net-(R121-Pad2)") (class "Default")
      (node (ref "R121") (pin "2") (pinfunction "2_2") (pintype "passive"))
      (node (ref "S2") (pin "8") (pinfunction "8_8") (pintype "passive"))
      (node (ref "U$6") (pin "3") (pinfunction "3_3") (pintype "passive"))
    )
    (net (code "282") (name "Net-(R122-Pad2)") (class "Default")
      (node (ref "R122") (pin "2") (pinfunction "2_2") (pintype "passive"))
      (node (ref "S2") (pin "7") (pinfunction "7_7") (pintype "passive"))
      (node (ref "U$6") (pin "6") (pinfunction "6_6") (pintype "passive"))
    )
    (net (code "283") (name "Net-(R123-Pad2)") (class "Default")
      (node (ref "R123") (pin "2") (pinfunction "2_2") (pintype "passive"))
      (node (ref "S2") (pin "6") (pinfunction "6_6") (pintype "passive"))
      (node (ref "U$6") (pin "9") (pinfunction "9_9") (pintype "passive"))
    )
    (net (code "284") (name "Net-(R124-Pad2)") (class "Default")
      (node (ref "R124") (pin "2") (pinfunction "2_2") (pintype "passive"))
      (node (ref "S2") (pin "5") (pinfunction "5_5") (pintype "passive"))
      (node (ref "U$6") (pin "12") (pinfunction "12_12") (pintype "passive"))
    )
    (net (code "285") (name "Net-(R125-Pad2)") (class "Default")
      (node (ref "R125") (pin "2") (pinfunction "2_2") (pintype "passive"))
      (node (ref "S2") (pin "4") (pinfunction "4_4") (pintype "passive"))
      (node (ref "U$6") (pin "15") (pinfunction "15_15") (pintype "passive"))
    )
    (net (code "286") (name "Net-(R126-Pad2)") (class "Default")
      (node (ref "R126") (pin "2") (pinfunction "2_2") (pintype "passive"))
      (node (ref "S2") (pin "3") (pinfunction "3_3") (pintype "passive"))
      (node (ref "U$6") (pin "18") (pinfunction "18_18") (pintype "passive"))
    )
    (net (code "287") (name "Net-(R127-Pad2)") (class "Default")
      (node (ref "R127") (pin "2") (pinfunction "2_2") (pintype "passive"))
      (node (ref "S2") (pin "2") (pinfunction "2_2") (pintype "passive"))
      (node (ref "U$6") (pin "21") (pinfunction "21_21") (pintype "passive"))
    )
    (net (code "288") (name "Net-(R128-Pad2)") (class "Default")
      (node (ref "R128") (pin "2") (pinfunction "2_2") (pintype "passive"))
      (node (ref "S2") (pin "1") (pinfunction "1_1") (pintype "passive"))
      (node (ref "U$6") (pin "24") (pinfunction "24_24") (pintype "passive"))
    )
    (net (code "289") (name "Net-(R129-Pad2)") (class "Default")
      (node (ref "R129") (pin "2") (pinfunction "2_2") (pintype "passive"))
      (node (ref "S1") (pin "8") (pinfunction "8_8") (pintype "passive"))
      (node (ref "U$6") (pin "27") (pinfunction "27_27") (pintype "passive"))
    )
    (net (code "290") (name "Net-(R130-Pad2)") (class "Default")
      (node (ref "R130") (pin "2") (pinfunction "2_2") (pintype "passive"))
      (node (ref "S1") (pin "7") (pinfunction "7_7") (pintype "passive"))
      (node (ref "U$6") (pin "30") (pinfunction "30_30") (pintype "passive"))
    )
    (net (code "291") (name "Net-(R131-Pad2)") (class "Default")
      (node (ref "R131") (pin "2") (pinfunction "2_2") (pintype "passive"))
      (node (ref "S1") (pin "6") (pinfunction "6_6") (pintype "passive"))
      (node (ref "U$6") (pin "33") (pinfunction "33_33") (pintype "passive"))
    )
    (net (code "292") (name "Net-(R132-Pad2)") (class "Default")
      (node (ref "R132") (pin "2") (pinfunction "2_2") (pintype "passive"))
      (node (ref "S1") (pin "5") (pinfunction "5_5") (pintype "passive"))
      (node (ref "U$6") (pin "36") (pinfunction "36_36") (pintype "passive"))
    )
    (net (code "293") (name "Net-(R133-Pad2)") (class "Default")
      (node (ref "R133") (pin "2") (pinfunction "2_2") (pintype "passive"))
      (node (ref "S1") (pin "4") (pinfunction "4_4") (pintype "passive"))
      (node (ref "U$6") (pin "39") (pinfunction "39_39") (pintype "passive"))
    )
    (net (code "294") (name "Net-(R134-Pad2)") (class "Default")
      (node (ref "R134") (pin "2") (pinfunction "2_2") (pintype "passive"))
      (node (ref "S1") (pin "3") (pinfunction "3_3") (pintype "passive"))
      (node (ref "U$6") (pin "42") (pinfunction "42_42") (pintype "passive"))
    )
    (net (code "295") (name "Net-(R135-Pad2)") (class "Default")
      (node (ref "R135") (pin "2") (pinfunction "2_2") (pintype "passive"))
      (node (ref "S1") (pin "2") (pinfunction "2_2") (pintype "passive"))
      (node (ref "U$6") (pin "45") (pinfunction "45_45") (pintype "passive"))
    )
    (net (code "296") (name "Net-(R136-Pad2)") (class "Default")
      (node (ref "R136") (pin "2") (pinfunction "2_2") (pintype "passive"))
      (node (ref "S1") (pin "1") (pinfunction "1_1") (pintype "passive"))
      (node (ref "U$6") (pin "48") (pinfunction "48_48") (pintype "passive"))
    )
    (net (code "297") (name "Net-(R137-Pad2)") (class "Default")
      (node (ref "R137") (pin "2") (pinfunction "2_2") (pintype "passive"))
      (node (ref "U$6") (pin "2") (pinfunction "2_2") (pintype "passive"))
    )
    (net (code "298") (name "Net-(R138-Pad2)") (class "Default")
      (node (ref "R138") (pin "2") (pinfunction "2_2") (pintype "passive"))
      (node (ref "U$6") (pin "5") (pinfunction "5_5") (pintype "passive"))
    )
    (net (code "299") (name "Net-(R139-Pad2)") (class "Default")
      (node (ref "R139") (pin "2") (pinfunction "2_2") (pintype "passive"))
      (node (ref "U$6") (pin "8") (pinfunction "8_8") (pintype "passive"))
    )
    (net (code "300") (name "Net-(R140-Pad2)") (class "Default")
      (node (ref "R140") (pin "2") (pinfunction "2_2") (pintype "passive"))
      (node (ref "U$6") (pin "11") (pinfunction "11_11") (pintype "passive"))
    )
    (net (code "301") (name "Net-(R141-Pad2)") (class "Default")
      (node (ref "R141") (pin "2") (pinfunction "2_2") (pintype "passive"))
      (node (ref "U$6") (pin "14") (pinfunction "14_14") (pintype "passive"))
    )
    (net (code "302") (name "Net-(R142-Pad2)") (class "Default")
      (node (ref "R142") (pin "2") (pinfunction "2_2") (pintype "passive"))
      (node (ref "U$6") (pin "17") (pinfunction "17_17") (pintype "passive"))
    )
    (net (code "303") (name "Net-(R143-Pad2)") (class "Default")
      (node (ref "R143") (pin "2") (pinfunction "2_2") (pintype "passive"))
      (node (ref "U$6") (pin "20") (pinfunction "20_20") (pintype "passive"))
    )
    (net (code "304") (name "Net-(R144-Pad2)") (class "Default")
      (node (ref "R144") (pin "2") (pinfunction "2_2") (pintype "passive"))
      (node (ref "U$6") (pin "23") (pinfunction "23_23") (pintype "passive"))
    )
    (net (code "305") (name "Net-(R145-Pad2)") (class "Default")
      (node (ref "R145") (pin "2") (pinfunction "2_2") (pintype "passive"))
      (node (ref "U$6") (pin "26") (pinfunction "26_26") (pintype "passive"))
    )
    (net (code "306") (name "Net-(R146-Pad2)") (class "Default")
      (node (ref "R146") (pin "2") (pinfunction "2_2") (pintype "passive"))
      (node (ref "U$6") (pin "29") (pinfunction "29_29") (pintype "passive"))
    )
    (net (code "307") (name "Net-(R147-Pad2)") (class "Default")
      (node (ref "R147") (pin "2") (pinfunction "2_2") (pintype "passive"))
      (node (ref "U$6") (pin "32") (pinfunction "32_32") (pintype "passive"))
    )
    (net (code "308") (name "Net-(R148-Pad2)") (class "Default")
      (node (ref "R148") (pin "2") (pinfunction "2_2") (pintype "passive"))
      (node (ref "U$6") (pin "35") (pinfunction "35_35") (pintype "passive"))
    )
    (net (code "309") (name "Net-(R149-Pad2)") (class "Default")
      (node (ref "R149") (pin "2") (pinfunction "2_2") (pintype "passive"))
      (node (ref "U$6") (pin "38") (pinfunction "38_38") (pintype "passive"))
    )
    (net (code "310") (name "Net-(R150-Pad2)") (class "Default")
      (node (ref "R150") (pin "2") (pinfunction "2_2") (pintype "passive"))
      (node (ref "U$6") (pin "41") (pinfunction "41_41") (pintype "passive"))
    )
    (net (code "311") (name "Net-(R151-Pad2)") (class "Default")
      (node (ref "R151") (pin "2") (pinfunction "2_2") (pintype "passive"))
      (node (ref "U$6") (pin "44") (pinfunction "44_44") (pintype "passive"))
    )
    (net (code "312") (name "Net-(R152-Pad2)") (class "Default")
      (node (ref "R152") (pin "2") (pinfunction "2_2") (pintype "passive"))
      (node (ref "U$6") (pin "47") (pinfunction "47_47") (pintype "passive"))
    )
    (net (code "313") (name "Net-(R153-Pad2)") (class "Default")
      (node (ref "R153") (pin "2") (pinfunction "2_2") (pintype "passive"))
      (node (ref "U$6") (pin "1") (pinfunction "1_1") (pintype "passive"))
    )
    (net (code "314") (name "Net-(R154-Pad2)") (class "Default")
      (node (ref "R154") (pin "2") (pinfunction "2_2") (pintype "passive"))
      (node (ref "U$6") (pin "4") (pinfunction "4_4") (pintype "passive"))
    )
    (net (code "315") (name "Net-(R155-Pad2)") (class "Default")
      (node (ref "R155") (pin "2") (pinfunction "2_2") (pintype "passive"))
      (node (ref "U$6") (pin "7") (pinfunction "7_7") (pintype "passive"))
    )
    (net (code "316") (name "Net-(R156-Pad2)") (class "Default")
      (node (ref "R156") (pin "2") (pinfunction "2_2") (pintype "passive"))
      (node (ref "U$6") (pin "10") (pinfunction "10_10") (pintype "passive"))
    )
    (net (code "317") (name "Net-(R157-Pad2)") (class "Default")
      (node (ref "R157") (pin "2") (pinfunction "2_2") (pintype "passive"))
      (node (ref "U$6") (pin "13") (pinfunction "13_13") (pintype "passive"))
    )
    (net (code "318") (name "Net-(R158-Pad2)") (class "Default")
      (node (ref "R158") (pin "2") (pinfunction "2_2") (pintype "passive"))
      (node (ref "U$6") (pin "16") (pinfunction "16_16") (pintype "passive"))
    )
    (net (code "319") (name "Net-(R159-Pad2)") (class "Default")
      (node (ref "R159") (pin "2") (pinfunction "2_2") (pintype "passive"))
      (node (ref "U$6") (pin "19") (pinfunction "19_19") (pintype "passive"))
    )
    (net (code "320") (name "Net-(R160-Pad2)") (class "Default")
      (node (ref "R160") (pin "2") (pinfunction "2_2") (pintype "passive"))
      (node (ref "U$6") (pin "22") (pinfunction "22_22") (pintype "passive"))
    )
    (net (code "321") (name "Net-(R161-Pad2)") (class "Default")
      (node (ref "R161") (pin "2") (pinfunction "2_2") (pintype "passive"))
      (node (ref "U$6") (pin "25") (pinfunction "25_25") (pintype "passive"))
    )
    (net (code "322") (name "Net-(R162-Pad2)") (class "Default")
      (node (ref "R162") (pin "2") (pinfunction "2_2") (pintype "passive"))
      (node (ref "U$6") (pin "28") (pinfunction "28_28") (pintype "passive"))
    )
    (net (code "323") (name "Net-(R163-Pad2)") (class "Default")
      (node (ref "R163") (pin "2") (pinfunction "2_2") (pintype "passive"))
      (node (ref "U$6") (pin "31") (pinfunction "31_31") (pintype "passive"))
    )
    (net (code "324") (name "Net-(R164-Pad2)") (class "Default")
      (node (ref "R164") (pin "2") (pinfunction "2_2") (pintype "passive"))
      (node (ref "U$6") (pin "34") (pinfunction "34_34") (pintype "passive"))
    )
    (net (code "325") (name "Net-(R165-Pad2)") (class "Default")
      (node (ref "R165") (pin "2") (pinfunction "2_2") (pintype "passive"))
      (node (ref "U$6") (pin "37") (pinfunction "37_37") (pintype "passive"))
    )
    (net (code "326") (name "Net-(R166-Pad2)") (class "Default")
      (node (ref "R166") (pin "2") (pinfunction "2_2") (pintype "passive"))
      (node (ref "U$6") (pin "40") (pinfunction "40_40") (pintype "passive"))
    )
    (net (code "327") (name "Net-(R167-Pad2)") (class "Default")
      (node (ref "R167") (pin "2") (pinfunction "2_2") (pintype "passive"))
      (node (ref "U$6") (pin "43") (pinfunction "43_43") (pintype "passive"))
    )
    (net (code "328") (name "Net-(R168-Pad2)") (class "Default")
      (node (ref "R168") (pin "2") (pinfunction "2_2") (pintype "passive"))
      (node (ref "U$6") (pin "46") (pinfunction "46_46") (pintype "passive"))
    )
    (net (code "329") (name "OUT_A") (class "Default")
      (node (ref "IC1") (pin "7") (pinfunction "7_7") (pintype "passive"))
      (node (ref "MOT_A") (pin "1") (pinfunction "1_1") (pintype "passive"))
      (node (ref "R5") (pin "2") (pinfunction "2_2") (pintype "passive"))
    )
    (net (code "330") (name "OUT_B") (class "Default")
      (node (ref "IC1") (pin "5") (pinfunction "5_5") (pintype "passive"))
      (node (ref "LED3") (pin "C") (pinfunction "C_C") (pintype "passive"))
      (node (ref "LED4") (pin "A") (pinfunction "A_A") (pintype "passive"))
      (node (ref "MOT_B") (pin "1") (pinfunction "1_1") (pintype "passive"))
    )
    (net (code "331") (name "PWM") (class "Default")
      (node (ref "SV6") (pin "1") (pinfunction "1_1") (pintype "passive"))
      (node (ref "SV7") (pin "2") (pinfunction "2_2") (pintype "passive"))
    )
    (net (code "332") (name "RST") (class "Default")
      (node (ref "SV5") (pin "7") (pinfunction "7_7") (pintype "passive"))
      (node (ref "SV7") (pin "9") (pinfunction "9_9") (pintype "passive"))
    )
    (net (code "333") (name "RX") (class "Default")
      (node (ref "SV6") (pin "3") (pinfunction "3_3") (pintype "passive"))
      (node (ref "SV7") (pin "6") (pinfunction "6_6") (pintype "passive"))
    )
    (net (code "334") (name "SCK") (class "Default")
      (node (ref "SV5") (pin "5") (pinfunction "5_5") (pintype "passive"))
      (node (ref "SV7") (pin "5") (pinfunction "5_5") (pintype "passive"))
    )
    (net (code "335") (name "SCL") (class "Default")
      (node (ref "SV6") (pin "5") (pinfunction "5_5") (pintype "passive"))
      (node (ref "SV7") (pin "10") (pinfunction "10_10") (pintype "passive"))
    )
    (net (code "336") (name "SDA") (class "Default")
      (node (ref "SV6") (pin "6") (pinfunction "6_6") (pintype "passive"))
      (node (ref "SV7") (pin "12") (pinfunction "12_12") (pintype "passive"))
    )
    (net (code "337") (name "TX") (class "Default")
      (node (ref "SV6") (pin "4") (pinfunction "4_4") (pintype "passive"))
      (node (ref "SV7") (pin "8") (pinfunction "8_8") (pintype "passive"))
    )
    (net (code "338") (name "V+") (class "Default")
      (node (ref "IC1") (pin "6") (pinfunction "6_6") (pintype "passive"))
      (node (ref "VIN") (pin "2") (pinfunction "2_2") (pintype "passive"))
      (node (ref "X1") (pin "1") (pinfunction "KL_1") (pintype "passive"))
    )
    (net (code "339") (name "VCC") (class "Default")
      (node (ref "ENCODER") (pin "3") (pinfunction "3_3") (pintype "passive"))
      (node (ref "JP19") (pin "2") (pinfunction "2_2") (pintype "passive"))
      (node (ref "Q1") (pin "3") (pinfunction "D_3") (pintype "passive"))
      (node (ref "Q2") (pin "3") (pinfunction "D_3") (pintype "passive"))
      (node (ref "R121") (pin "1") (pinfunction "1_1") (pintype "passive"))
      (node (ref "R122") (pin "1") (pinfunction "1_1") (pintype "passive"))
      (node (ref "R123") (pin "1") (pinfunction "1_1") (pintype "passive"))
      (node (ref "R124") (pin "1") (pinfunction "1_1") (pintype "passive"))
      (node (ref "R125") (pin "1") (pinfunction "1_1") (pintype "passive"))
      (node (ref "R126") (pin "1") (pinfunction "1_1") (pintype "passive"))
      (node (ref "R127") (pin "1") (pinfunction "1_1") (pintype "passive"))
      (node (ref "R128") (pin "1") (pinfunction "1_1") (pintype "passive"))
      (node (ref "R129") (pin "1") (pinfunction "1_1") (pintype "passive"))
      (node (ref "R130") (pin "1") (pinfunction "1_1") (pintype "passive"))
      (node (ref "R131") (pin "1") (pinfunction "1_1") (pintype "passive"))
      (node (ref "R132") (pin "1") (pinfunction "1_1") (pintype "passive"))
      (node (ref "R133") (pin "1") (pinfunction "1_1") (pintype "passive"))
      (node (ref "R134") (pin "1") (pinfunction "1_1") (pintype "passive"))
      (node (ref "R135") (pin "1") (pinfunction "1_1") (pintype "passive"))
      (node (ref "R136") (pin "1") (pinfunction "1_1") (pintype "passive"))
      (node (ref "SENSOR") (pin "3") (pinfunction "3_3") (pintype "passive"))
      (node (ref "SENSOR1") (pin "3") (pinfunction "3_3") (pintype "passive"))
      (node (ref "U$5") (pin "3") (pinfunction "3_3") (pintype "passive"))
    )
    (net (code "340") (name "VDD") (class "Default")
      (node (ref "JP5") (pin "4") (pinfunction "4_4") (pintype "passive"))
    )
    (net (code "341") (name "VSS") (class "Default")
      (node (ref "IC1") (pin "3") (pinfunction "3_3") (pintype "passive"))
      (node (ref "JP19") (pin "1") (pinfunction "1_1") (pintype "passive"))
      (node (ref "JP4") (pin "1") (pinfunction "1_1") (pintype "passive"))
      (node (ref "JP4") (pin "2") (pinfunction "2_2") (pintype "passive"))
      (node (ref "JP4") (pin "3") (pinfunction "3_3") (pintype "passive"))
      (node (ref "JP4") (pin "4") (pinfunction "4_4") (pintype "passive"))
      (node (ref "JP5") (pin "1") (pinfunction "1_1") (pintype "passive"))
      (node (ref "LED1") (pin "C") (pinfunction "C_C") (pintype "passive"))
      (node (ref "LED10") (pin "C") (pinfunction "C_C") (pintype "passive"))
      (node (ref "LED100") (pin "C") (pinfunction "C_C") (pintype "passive"))
      (node (ref "LED101") (pin "C") (pinfunction "C_C") (pintype "passive"))
      (node (ref "LED102") (pin "C") (pinfunction "C_C") (pintype "passive"))
      (node (ref "LED103") (pin "C") (pinfunction "C_C") (pintype "passive"))
      (node (ref "LED104") (pin "C") (pinfunction "C_C") (pintype "passive"))
      (node (ref "LED105") (pin "C") (pinfunction "C_C") (pintype "passive"))
      (node (ref "LED106") (pin "C") (pinfunction "C_C") (pintype "passive"))
      (node (ref "LED107") (pin "C") (pinfunction "C_C") (pintype "passive"))
      (node (ref "LED108") (pin "C") (pinfunction "C_C") (pintype "passive"))
      (node (ref "LED109") (pin "C") (pinfunction "C_C") (pintype "passive"))
      (node (ref "LED11") (pin "C") (pinfunction "C_C") (pintype "passive"))
      (node (ref "LED110") (pin "C") (pinfunction "C_C") (pintype "passive"))
      (node (ref "LED111") (pin "C") (pinfunction "C_C") (pintype "passive"))
      (node (ref "LED112") (pin "C") (pinfunction "C_C") (pintype "passive"))
      (node (ref "LED113") (pin "C") (pinfunction "C_C") (pintype "passive"))
      (node (ref "LED114") (pin "C") (pinfunction "C_C") (pintype "passive"))
      (node (ref "LED115") (pin "C") (pinfunction "C_C") (pintype "passive"))
      (node (ref "LED116") (pin "C") (pinfunction "C_C") (pintype "passive"))
      (node (ref "LED12") (pin "C") (pinfunction "C_C") (pintype "passive"))
      (node (ref "LED13") (pin "C") (pinfunction "C_C") (pintype "passive"))
      (node (ref "LED133") (pin "C") (pinfunction "C_C") (pintype "passive"))
      (node (ref "LED134") (pin "C") (pinfunction "C_C") (pintype "passive"))
      (node (ref "LED135") (pin "C") (pinfunction "C_C") (pintype "passive"))
      (node (ref "LED136") (pin "C") (pinfunction "C_C") (pintype "passive"))
      (node (ref "LED137") (pin "C") (pinfunction "C_C") (pintype "passive"))
      (node (ref "LED138") (pin "C") (pinfunction "C_C") (pintype "passive"))
      (node (ref "LED139") (pin "C") (pinfunction "C_C") (pintype "passive"))
      (node (ref "LED14") (pin "C") (pinfunction "C_C") (pintype "passive"))
      (node (ref "LED140") (pin "C") (pinfunction "C_C") (pintype "passive"))
      (node (ref "LED141") (pin "C") (pinfunction "C_C") (pintype "passive"))
      (node (ref "LED142") (pin "C") (pinfunction "C_C") (pintype "passive"))
      (node (ref "LED143") (pin "C") (pinfunction "C_C") (pintype "passive"))
      (node (ref "LED144") (pin "C") (pinfunction "C_C") (pintype "passive"))
      (node (ref "LED145") (pin "C") (pinfunction "C_C") (pintype "passive"))
      (node (ref "LED146") (pin "C") (pinfunction "C_C") (pintype "passive"))
      (node (ref "LED147") (pin "C") (pinfunction "C_C") (pintype "passive"))
      (node (ref "LED148") (pin "C") (pinfunction "C_C") (pintype "passive"))
      (node (ref "LED149") (pin "C") (pinfunction "C_C") (pintype "passive"))
      (node (ref "LED15") (pin "C") (pinfunction "C_C") (pintype "passive"))
      (node (ref "LED150") (pin "C") (pinfunction "C_C") (pintype "passive"))
      (node (ref "LED151") (pin "C") (pinfunction "C_C") (pintype "passive"))
      (node (ref "LED152") (pin "C") (pinfunction "C_C") (pintype "passive"))
      (node (ref "LED153") (pin "C") (pinfunction "C_C") (pintype "passive"))
      (node (ref "LED154") (pin "C") (pinfunction "C_C") (pintype "passive"))
      (node (ref "LED155") (pin "C") (pinfunction "C_C") (pintype "passive"))
      (node (ref "LED156") (pin "C") (pinfunction "C_C") (pintype "passive"))
      (node (ref "LED157") (pin "C") (pinfunction "C_C") (pintype "passive"))
      (node (ref "LED158") (pin "C") (pinfunction "C_C") (pintype "passive"))
      (node (ref "LED159") (pin "C") (pinfunction "C_C") (pintype "passive"))
      (node (ref "LED16") (pin "C") (pinfunction "C_C") (pintype "passive"))
      (node (ref "LED160") (pin "C") (pinfunction "C_C") (pintype "passive"))
      (node (ref "LED161") (pin "C") (pinfunction "C_C") (pintype "passive"))
      (node (ref "LED162") (pin "C") (pinfunction "C_C") (pintype "passive"))
      (node (ref "LED163") (pin "C") (pinfunction "C_C") (pintype "passive"))
      (node (ref "LED164") (pin "C") (pinfunction "C_C") (pintype "passive"))
      (node (ref "LED17") (pin "C") (pinfunction "C_C") (pintype "passive"))
      (node (ref "LED18") (pin "C") (pinfunction "C_C") (pintype "passive"))
      (node (ref "LED19") (pin "C") (pinfunction "C_C") (pintype "passive"))
      (node (ref "LED2") (pin "C") (pinfunction "C_C") (pintype "passive"))
      (node (ref "LED20") (pin "C") (pinfunction "C_C") (pintype "passive"))
      (node (ref "LED21") (pin "C") (pinfunction "C_C") (pintype "passive"))
      (node (ref "LED22") (pin "C") (pinfunction "C_C") (pintype "passive"))
      (node (ref "LED23") (pin "C") (pinfunction "C_C") (pintype "passive"))
      (node (ref "LED24") (pin "C") (pinfunction "C_C") (pintype "passive"))
      (node (ref "LED25") (pin "C") (pinfunction "C_C") (pintype "passive"))
      (node (ref "LED26") (pin "C") (pinfunction "C_C") (pintype "passive"))
      (node (ref "LED27") (pin "C") (pinfunction "C_C") (pintype "passive"))
      (node (ref "LED28") (pin "C") (pinfunction "C_C") (pintype "passive"))
      (node (ref "LED29") (pin "C") (pinfunction "C_C") (pintype "passive"))
      (node (ref "LED30") (pin "C") (pinfunction "C_C") (pintype "passive"))
      (node (ref "LED31") (pin "C") (pinfunction "C_C") (pintype "passive"))
      (node (ref "LED32") (pin "C") (pinfunction "C_C") (pintype "passive"))
      (node (ref "LED33") (pin "C") (pinfunction "C_C") (pintype "passive"))
      (node (ref "LED34") (pin "C") (pinfunction "C_C") (pintype "passive"))
      (node (ref "LED35") (pin "C") (pinfunction "C_C") (pintype "passive"))
      (node (ref "LED36") (pin "C") (pinfunction "C_C") (pintype "passive"))
      (node (ref "LED37") (pin "C") (pinfunction "C_C") (pintype "passive"))
      (node (ref "LED38") (pin "C") (pinfunction "C_C") (pintype "passive"))
      (node (ref "LED39") (pin "C") (pinfunction "C_C") (pintype "passive"))
      (node (ref "LED40") (pin "C") (pinfunction "C_C") (pintype "passive"))
      (node (ref "LED41") (pin "C") (pinfunction "C_C") (pintype "passive"))
      (node (ref "LED42") (pin "C") (pinfunction "C_C") (pintype "passive"))
      (node (ref "LED43") (pin "C") (pinfunction "C_C") (pintype "passive"))
      (node (ref "LED44") (pin "C") (pinfunction "C_C") (pintype "passive"))
      (node (ref "LED45") (pin "C") (pinfunction "C_C") (pintype "passive"))
      (node (ref "LED46") (pin "C") (pinfunction "C_C") (pintype "passive"))
      (node (ref "LED47") (pin "C") (pinfunction "C_C") (pintype "passive"))
      (node (ref "LED48") (pin "C") (pinfunction "C_C") (pintype "passive"))
      (node (ref "LED49") (pin "C") (pinfunction "C_C") (pintype "passive"))
      (node (ref "LED5") (pin "C") (pinfunction "C_C") (pintype "passive"))
      (node (ref "LED50") (pin "C") (pinfunction "C_C") (pintype "passive"))
      (node (ref "LED51") (pin "C") (pinfunction "C_C") (pintype "passive"))
      (node (ref "LED52") (pin "C") (pinfunction "C_C") (pintype "passive"))
      (node (ref "LED53") (pin "C") (pinfunction "C_C") (pintype "passive"))
      (node (ref "LED54") (pin "C") (pinfunction "C_C") (pintype "passive"))
      (node (ref "LED55") (pin "C") (pinfunction "C_C") (pintype "passive"))
      (node (ref "LED56") (pin "C") (pinfunction "C_C") (pintype "passive"))
      (node (ref "LED57") (pin "C") (pinfunction "C_C") (pintype "passive"))
      (node (ref "LED58") (pin "C") (pinfunction "C_C") (pintype "passive"))
      (node (ref "LED59") (pin "C") (pinfunction "C_C") (pintype "passive"))
      (node (ref "LED6") (pin "C") (pinfunction "C_C") (pintype "passive"))
      (node (ref "LED60") (pin "C") (pinfunction "C_C") (pintype "passive"))
      (node (ref "LED61") (pin "C") (pinfunction "C_C") (pintype "passive"))
      (node (ref "LED62") (pin "C") (pinfunction "C_C") (pintype "passive"))
      (node (ref "LED63") (pin "C") (pinfunction "C_C") (pintype "passive"))
      (node (ref "LED64") (pin "C") (pinfunction "C_C") (pintype "passive"))
      (node (ref "LED65") (pin "C") (pinfunction "C_C") (pintype "passive"))
      (node (ref "LED66") (pin "C") (pinfunction "C_C") (pintype "passive"))
      (node (ref "LED67") (pin "C") (pinfunction "C_C") (pintype "passive"))
      (node (ref "LED68") (pin "C") (pinfunction "C_C") (pintype "passive"))
      (node (ref "LED69") (pin "C") (pinfunction "C_C") (pintype "passive"))
      (node (ref "LED7") (pin "C") (pinfunction "C_C") (pintype "passive"))
      (node (ref "LED70") (pin "C") (pinfunction "C_C") (pintype "passive"))
      (node (ref "LED71") (pin "C") (pinfunction "C_C") (pintype "passive"))
      (node (ref "LED72") (pin "C") (pinfunction "C_C") (pintype "passive"))
      (node (ref "LED73") (pin "C") (pinfunction "C_C") (pintype "passive"))
      (node (ref "LED74") (pin "C") (pinfunction "C_C") (pintype "passive"))
      (node (ref "LED75") (pin "C") (pinfunction "C_C") (pintype "passive"))
      (node (ref "LED76") (pin "C") (pinfunction "C_C") (pintype "passive"))
      (node (ref "LED77") (pin "C") (pinfunction "C_C") (pintype "passive"))
      (node (ref "LED78") (pin "C") (pinfunction "C_C") (pintype "passive"))
      (node (ref "LED79") (pin "C") (pinfunction "C_C") (pintype "passive"))
      (node (ref "LED8") (pin "C") (pinfunction "C_C") (pintype "passive"))
      (node (ref "LED80") (pin "C") (pinfunction "C_C") (pintype "passive"))
      (node (ref "LED81") (pin "C") (pinfunction "C_C") (pintype "passive"))
      (node (ref "LED82") (pin "C") (pinfunction "C_C") (pintype "passive"))
      (node (ref "LED83") (pin "C") (pinfunction "C_C") (pintype "passive"))
      (node (ref "LED84") (pin "C") (pinfunction "C_C") (pintype "passive"))
      (node (ref "LED85") (pin "C") (pinfunction "C_C") (pintype "passive"))
      (node (ref "LED86") (pin "C") (pinfunction "C_C") (pintype "passive"))
      (node (ref "LED87") (pin "C") (pinfunction "C_C") (pintype "passive"))
      (node (ref "LED88") (pin "C") (pinfunction "C_C") (pintype "passive"))
      (node (ref "LED89") (pin "C") (pinfunction "C_C") (pintype "passive"))
      (node (ref "LED9") (pin "C") (pinfunction "C_C") (pintype "passive"))
      (node (ref "LED90") (pin "C") (pinfunction "C_C") (pintype "passive"))
      (node (ref "LED91") (pin "C") (pinfunction "C_C") (pintype "passive"))
      (node (ref "LED92") (pin "C") (pinfunction "C_C") (pintype "passive"))
      (node (ref "LED93") (pin "C") (pinfunction "C_C") (pintype "passive"))
      (node (ref "LED94") (pin "C") (pinfunction "C_C") (pintype "passive"))
      (node (ref "LED95") (pin "C") (pinfunction "C_C") (pintype "passive"))
      (node (ref "LED96") (pin "C") (pinfunction "C_C") (pintype "passive"))
      (node (ref "LED97") (pin "C") (pinfunction "C_C") (pintype "passive"))
      (node (ref "LED98") (pin "C") (pinfunction "C_C") (pintype "passive"))
      (node (ref "LED99") (pin "C") (pinfunction "C_C") (pintype "passive"))
      (node (ref "P5_VIN") (pin "1") (pinfunction "1_1") (pintype "passive"))
      (node (ref "R1") (pin "1") (pinfunction "1_1") (pintype "passive"))
      (node (ref "R2") (pin "1") (pinfunction "1_1") (pintype "passive"))
      (node (ref "R27") (pin "2") (pinfunction "2_2") (pintype "passive"))
      (node (ref "R6") (pin "1") (pinfunction "1_1") (pintype "passive"))
      (node (ref "R7") (pin "1") (pinfunction "1_1") (pintype "passive"))
      (node (ref "S1") (pin "10") (pinfunction "10_10") (pintype "passive"))
      (node (ref "S1") (pin "11") (pinfunction "11_11") (pintype "passive"))
      (node (ref "S1") (pin "12") (pinfunction "12_12") (pintype "passive"))
      (node (ref "S1") (pin "13") (pinfunction "13_13") (pintype "passive"))
      (node (ref "S1") (pin "14") (pinfunction "14_14") (pintype "passive"))
      (node (ref "S1") (pin "15") (pinfunction "15_15") (pintype "passive"))
      (node (ref "S1") (pin "16") (pinfunction "16_16") (pintype "passive"))
      (node (ref "S1") (pin "9") (pinfunction "9_9") (pintype "passive"))
      (node (ref "S2") (pin "10") (pinfunction "10_10") (pintype "passive"))
      (node (ref "S2") (pin "11") (pinfunction "11_11") (pintype "passive"))
      (node (ref "S2") (pin "12") (pinfunction "12_12") (pintype "passive"))
      (node (ref "S2") (pin "13") (pinfunction "13_13") (pintype "passive"))
      (node (ref "S2") (pin "14") (pinfunction "14_14") (pintype "passive"))
      (node (ref "S2") (pin "15") (pinfunction "15_15") (pintype "passive"))
      (node (ref "S2") (pin "16") (pinfunction "16_16") (pintype "passive"))
      (node (ref "S2") (pin "9") (pinfunction "9_9") (pintype "passive"))
      (node (ref "SV5") (pin "1") (pinfunction "1_1") (pintype "passive"))
      (node (ref "SV6") (pin "8") (pinfunction "8_8") (pintype "passive"))
      (node (ref "U$2") (pin "1") (pinfunction "1_1") (pintype "passive"))
      (node (ref "U$2") (pin "2") (pinfunction "2_2") (pintype "passive"))
      (node (ref "U$2") (pin "3") (pinfunction "3_3") (pintype "passive"))
      (node (ref "U$5") (pin "1") (pinfunction "1_1") (pintype "passive"))
      (node (ref "U$5") (pin "2") (pinfunction "2_2") (pintype "passive"))
      (node (ref "VIN") (pin "1") (pinfunction "1_1") (pintype "passive"))
      (node (ref "X1") (pin "2") (pinfunction "KL_2") (pintype "passive"))
    )
    (net (code "342") (name "unconnected-(U1-*D3-PadD3)") (class "Default")
      (node (ref "U1") (pin "D3") (pinfunction "*D3_D3") (pintype "bidirectional"))
    )
    (net (code "343") (name "unconnected-(U1-*D5-PadD5)") (class "Default")
      (node (ref "U1") (pin "D5") (pinfunction "*D5_D5") (pintype "bidirectional"))
    )
    (net (code "344") (name "unconnected-(U1-*D6-PadD6)") (class "Default")
      (node (ref "U1") (pin "D6") (pinfunction "*D6_D6") (pintype "bidirectional"))
    )
    (net (code "345") (name "unconnected-(U1-*D9-PadD9)") (class "Default")
      (node (ref "U1") (pin "D9") (pinfunction "*D9_D9") (pintype "bidirectional"))
    )
    (net (code "346") (name "unconnected-(U1-*D10-PadD10)") (class "Default")
      (node (ref "U1") (pin "D10") (pinfunction "*D10_D10") (pintype "bidirectional"))
    )
    (net (code "347") (name "unconnected-(U1-*D11-PadD11)") (class "Default")
      (node (ref "U1") (pin "D11") (pinfunction "*D11_D11") (pintype "bidirectional"))
    )
    (net (code "348") (name "unconnected-(U1-GND-PadGND@0)") (class "Default")
      (node (ref "U1") (pin "GND@0") (pinfunction "GND_GND@0") (pintype "bidirectional"))
    )
    (net (code "349") (name "unconnected-(U1-GND-PadGND@1)") (class "Default")
      (node (ref "U1") (pin "GND@1") (pinfunction "GND_GND@1") (pintype "bidirectional"))
    )
    (net (code "350") (name "unconnected-(U1-GND-PadGND@2)") (class "Default")
      (node (ref "U1") (pin "GND@2") (pinfunction "GND_GND@2") (pintype "bidirectional"))
    )
    (net (code "351") (name "unconnected-(U1-Pad3.3V)") (class "Default")
      (node (ref "U1") (pin "3.3V") (pinfunction "3.3V_3.3V") (pintype "bidirectional"))
    )
    (net (code "352") (name "unconnected-(U1-Pad5V)") (class "Default")
      (node (ref "U1") (pin "5V") (pinfunction "5V_5V") (pintype "bidirectional"))
    )
    (net (code "353") (name "unconnected-(U1-PadA0)") (class "Default")
      (node (ref "U1") (pin "A0") (pinfunction "A0_A0") (pintype "bidirectional"))
    )
    (net (code "354") (name "unconnected-(U1-PadA1)") (class "Default")
      (node (ref "U1") (pin "A1") (pinfunction "A1_A1") (pintype "bidirectional"))
    )
    (net (code "355") (name "unconnected-(U1-PadA2)") (class "Default")
      (node (ref "U1") (pin "A2") (pinfunction "A2_A2") (pintype "bidirectional"))
    )
    (net (code "356") (name "unconnected-(U1-PadA3)") (class "Default")
      (node (ref "U1") (pin "A3") (pinfunction "A3_A3") (pintype "bidirectional"))
    )
    (net (code "357") (name "unconnected-(U1-PadA4)") (class "Default")
      (node (ref "U1") (pin "A4") (pinfunction "A4_A4") (pintype "bidirectional"))
    )
    (net (code "358") (name "unconnected-(U1-PadA5)") (class "Default")
      (node (ref "U1") (pin "A5") (pinfunction "A5_A5") (pintype "bidirectional"))
    )
    (net (code "359") (name "unconnected-(U1-PadAREF)") (class "Default")
      (node (ref "U1") (pin "AREF") (pinfunction "AREF_AREF") (pintype "bidirectional"))
    )
    (net (code "360") (name "unconnected-(U1-PadD2)") (class "Default")
      (node (ref "U1") (pin "D2") (pinfunction "D2_D2") (pintype "bidirectional"))
    )
    (net (code "361") (name "unconnected-(U1-PadD4)") (class "Default")
      (node (ref "U1") (pin "D4") (pinfunction "D4_D4") (pintype "bidirectional"))
    )
    (net (code "362") (name "unconnected-(U1-PadD7)") (class "Default")
      (node (ref "U1") (pin "D7") (pinfunction "D7_D7") (pintype "bidirectional"))
    )
    (net (code "363") (name "unconnected-(U1-PadD8)") (class "Default")
      (node (ref "U1") (pin "D8") (pinfunction "D8_D8") (pintype "bidirectional"))
    )
    (net (code "364") (name "unconnected-(U1-PadD12)") (class "Default")
      (node (ref "U1") (pin "D12") (pinfunction "D12_D12") (pintype "bidirectional"))
    )
    (net (code "365") (name "unconnected-(U1-PadD13)") (class "Default")
      (node (ref "U1") (pin "D13") (pinfunction "D13_D13") (pintype "bidirectional"))
    )
    (net (code "366") (name "unconnected-(U1-PadRES)") (class "Default")
      (node (ref "U1") (pin "RES") (pinfunction "RES_RES") (pintype "bidirectional"))
    )
    (net (code "367") (name "unconnected-(U1-PadRX)") (class "Default")
      (node (ref "U1") (pin "RX") (pinfunction "RX_RX") (pintype "bidirectional"))
    )
    (net (code "368") (name "unconnected-(U1-PadTX)") (class "Default")
      (node (ref "U1") (pin "TX") (pinfunction "TX_TX") (pintype "bidirectional"))
    )
    (net (code "369") (name "unconnected-(U1-PadVIN)") (class "Default")
      (node (ref "U1") (pin "VIN") (pinfunction "VIN_VIN") (pintype "bidirectional"))
    )
  )
)
